# PX4FMUv2_3.net
KiCad netlist of a schematic drawn in EAGLE
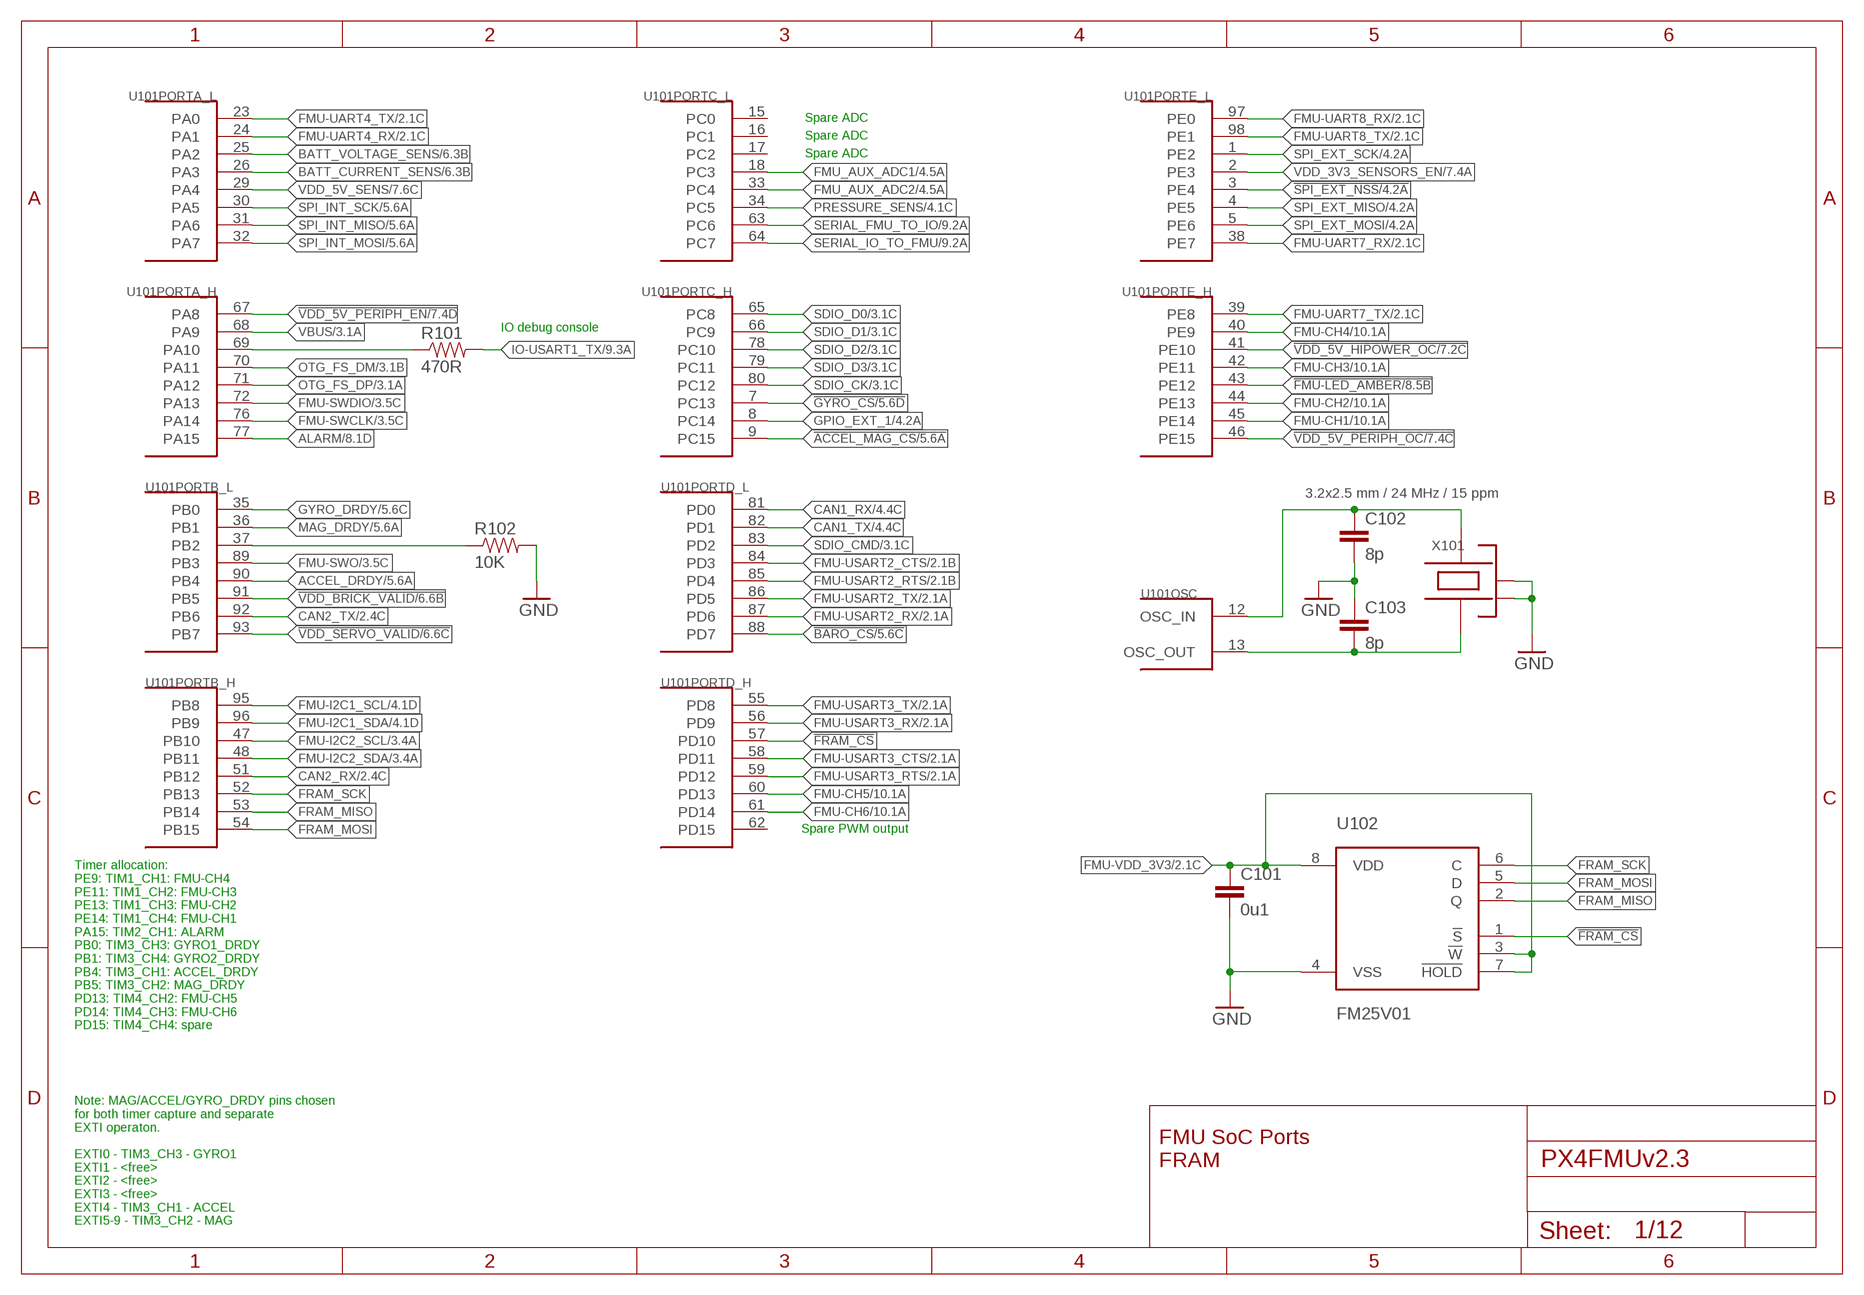
[diagram p0: schematic, sheet 1]
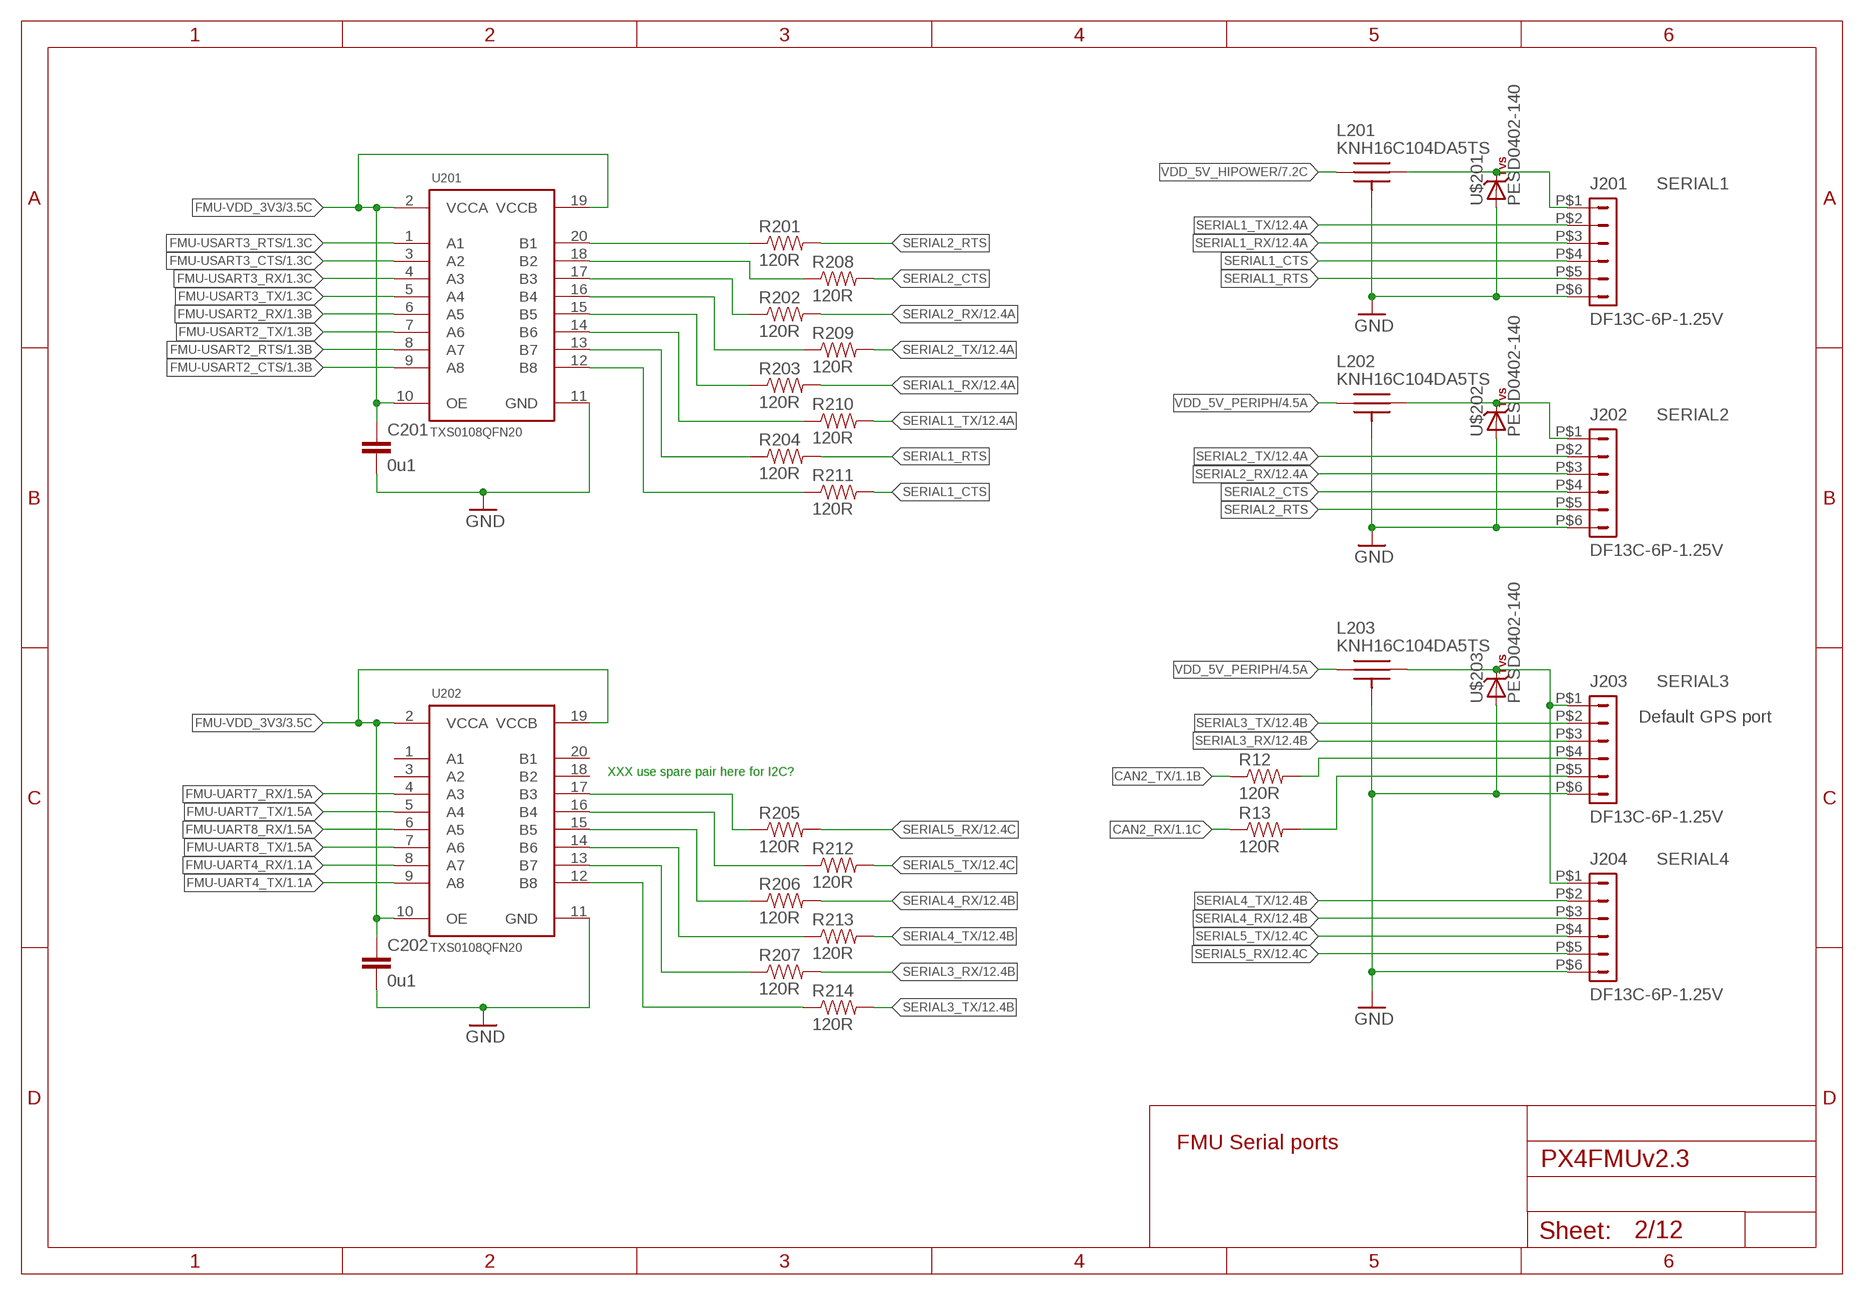
[diagram p1: schematic, sheet 2]
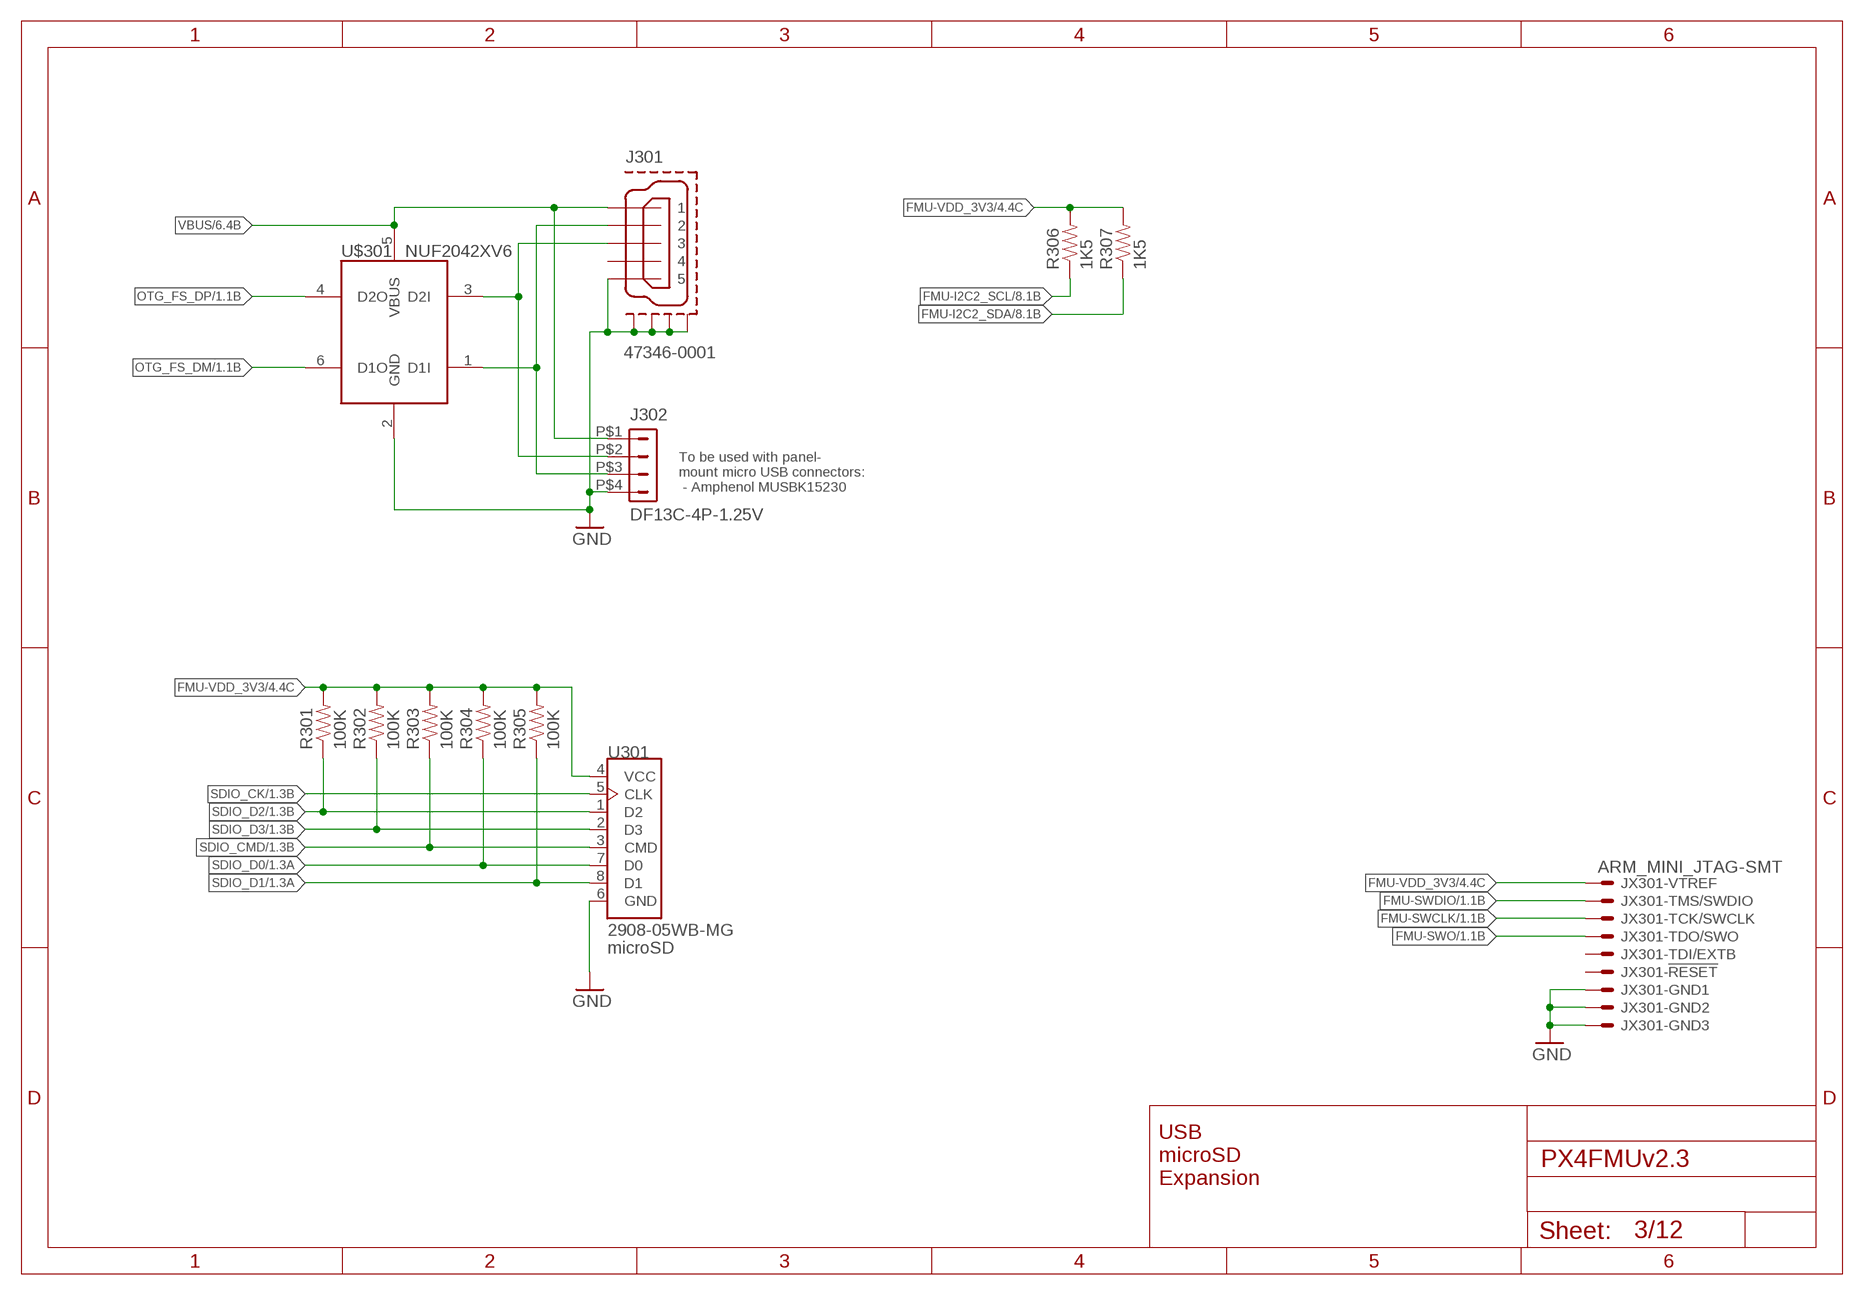
[diagram p2: schematic, sheet 3]
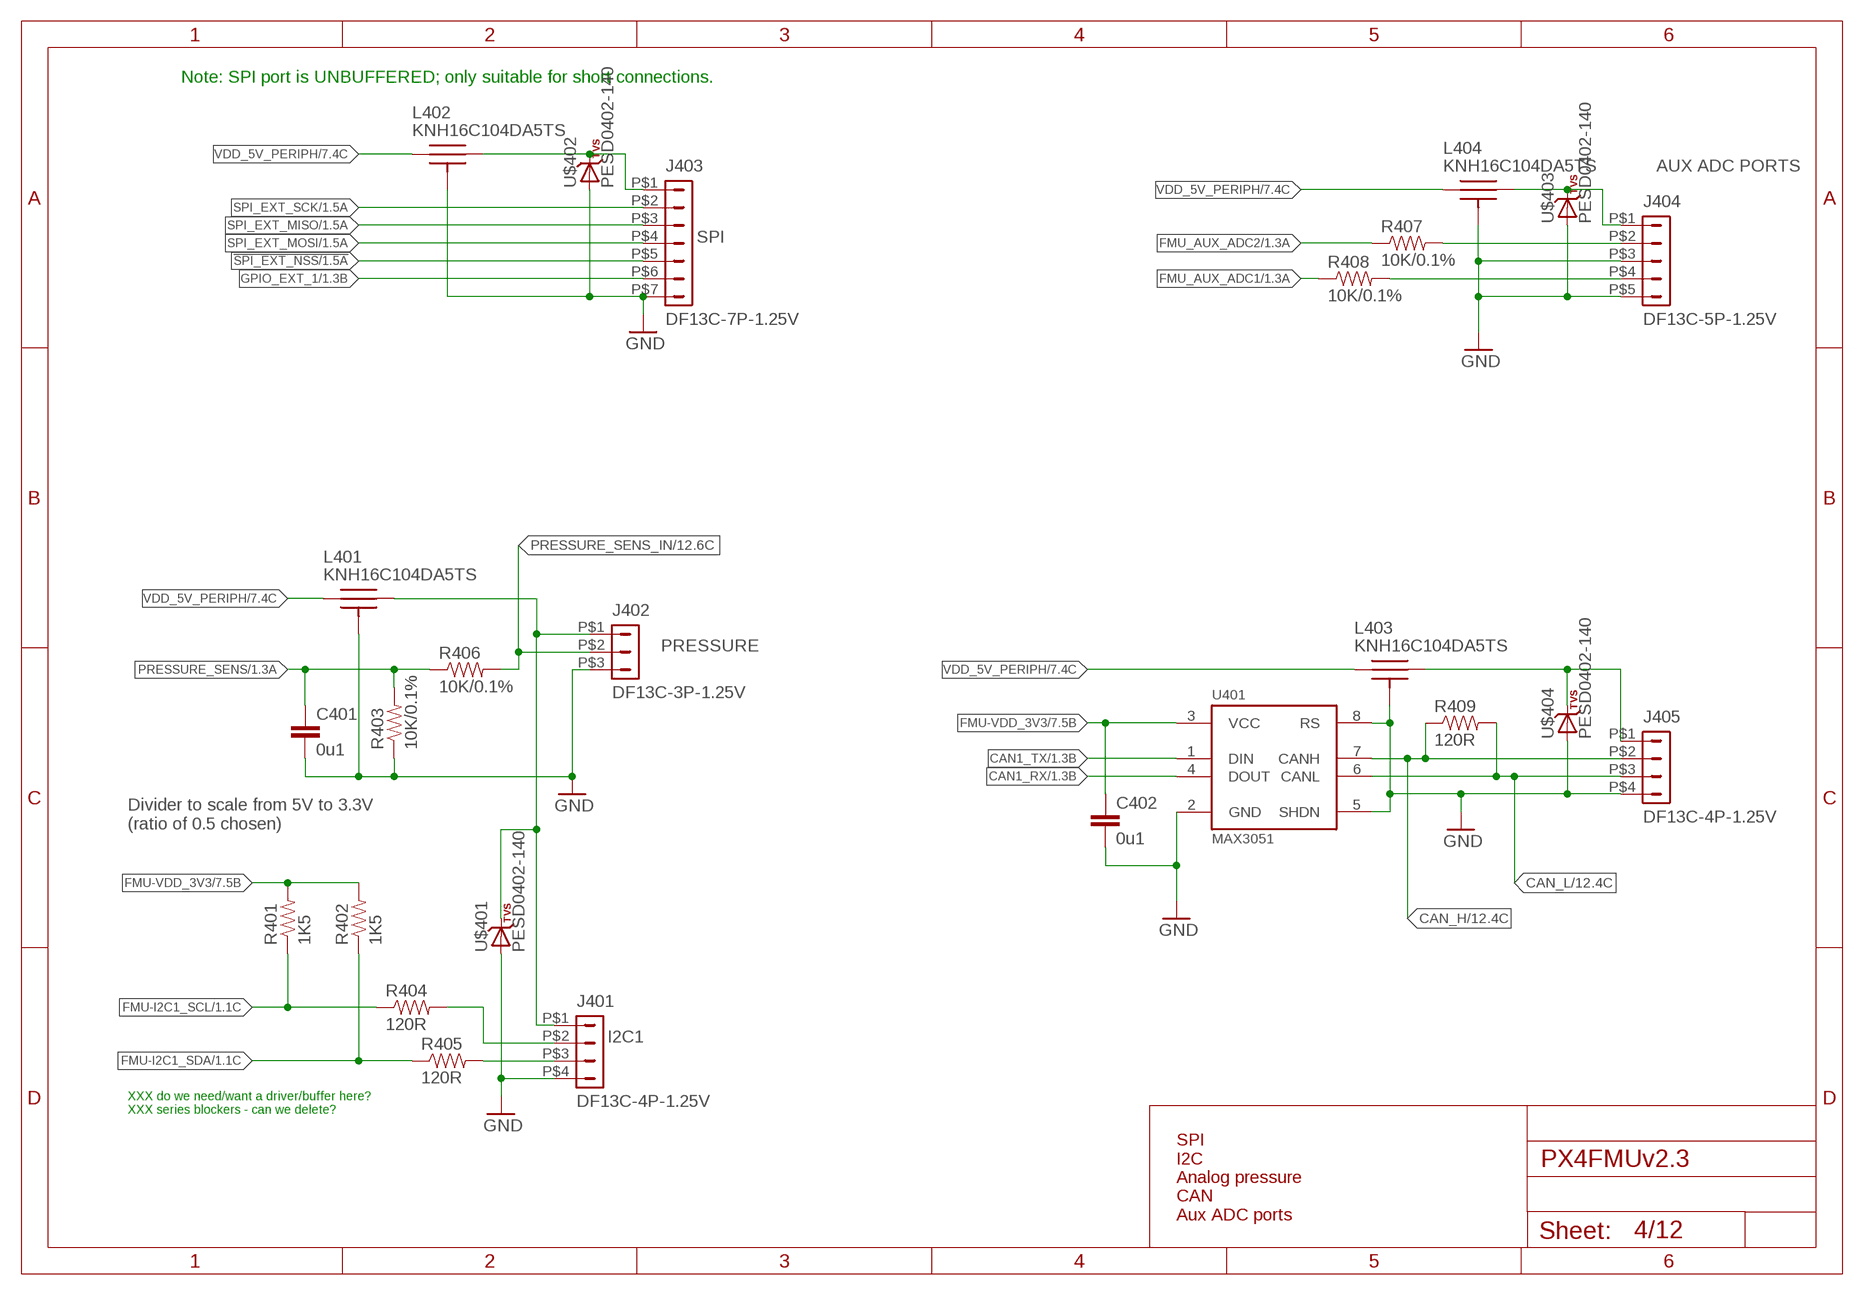
[diagram p3: schematic, sheet 4]
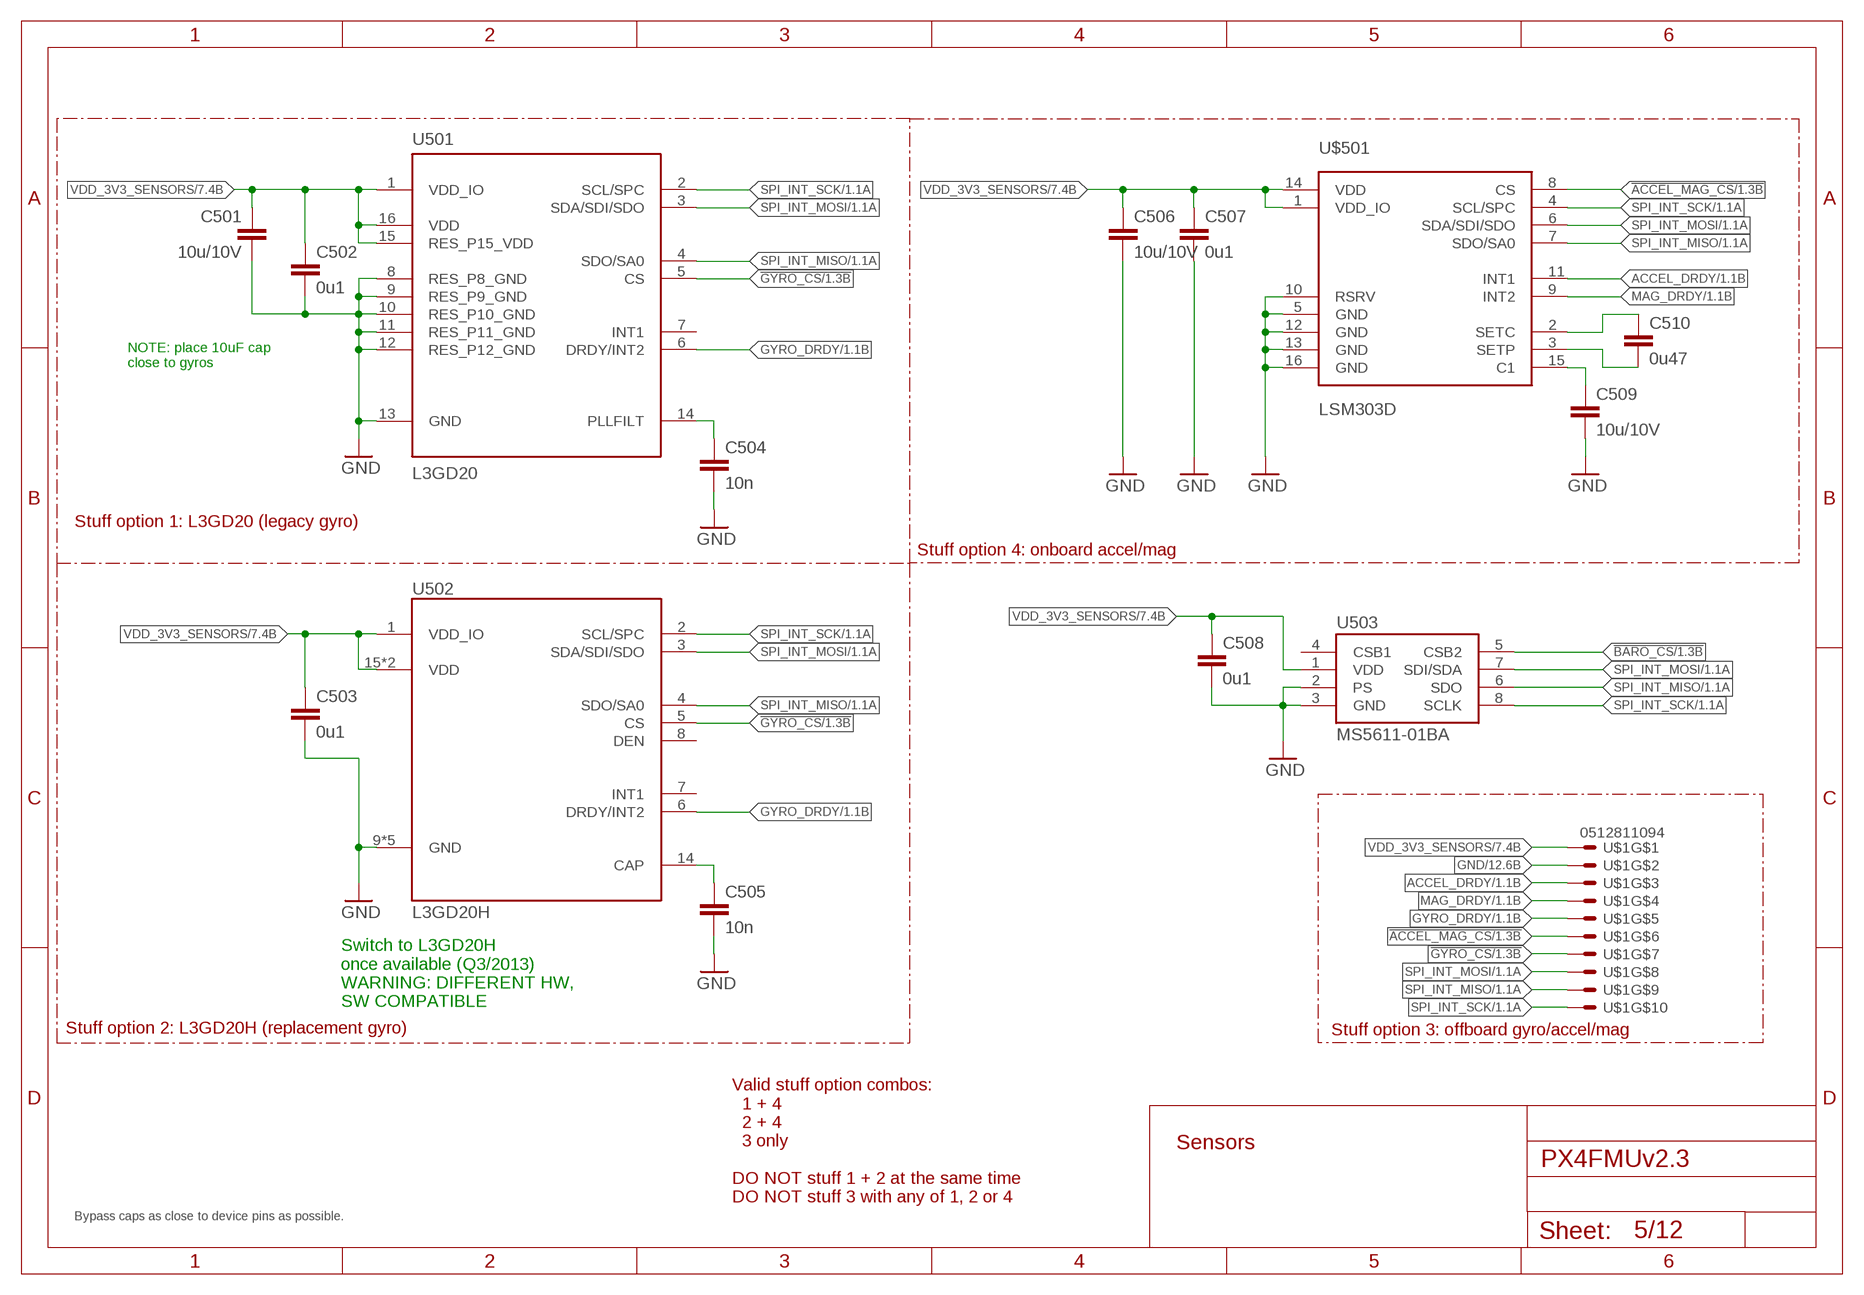
[diagram p4: schematic, sheet 5]
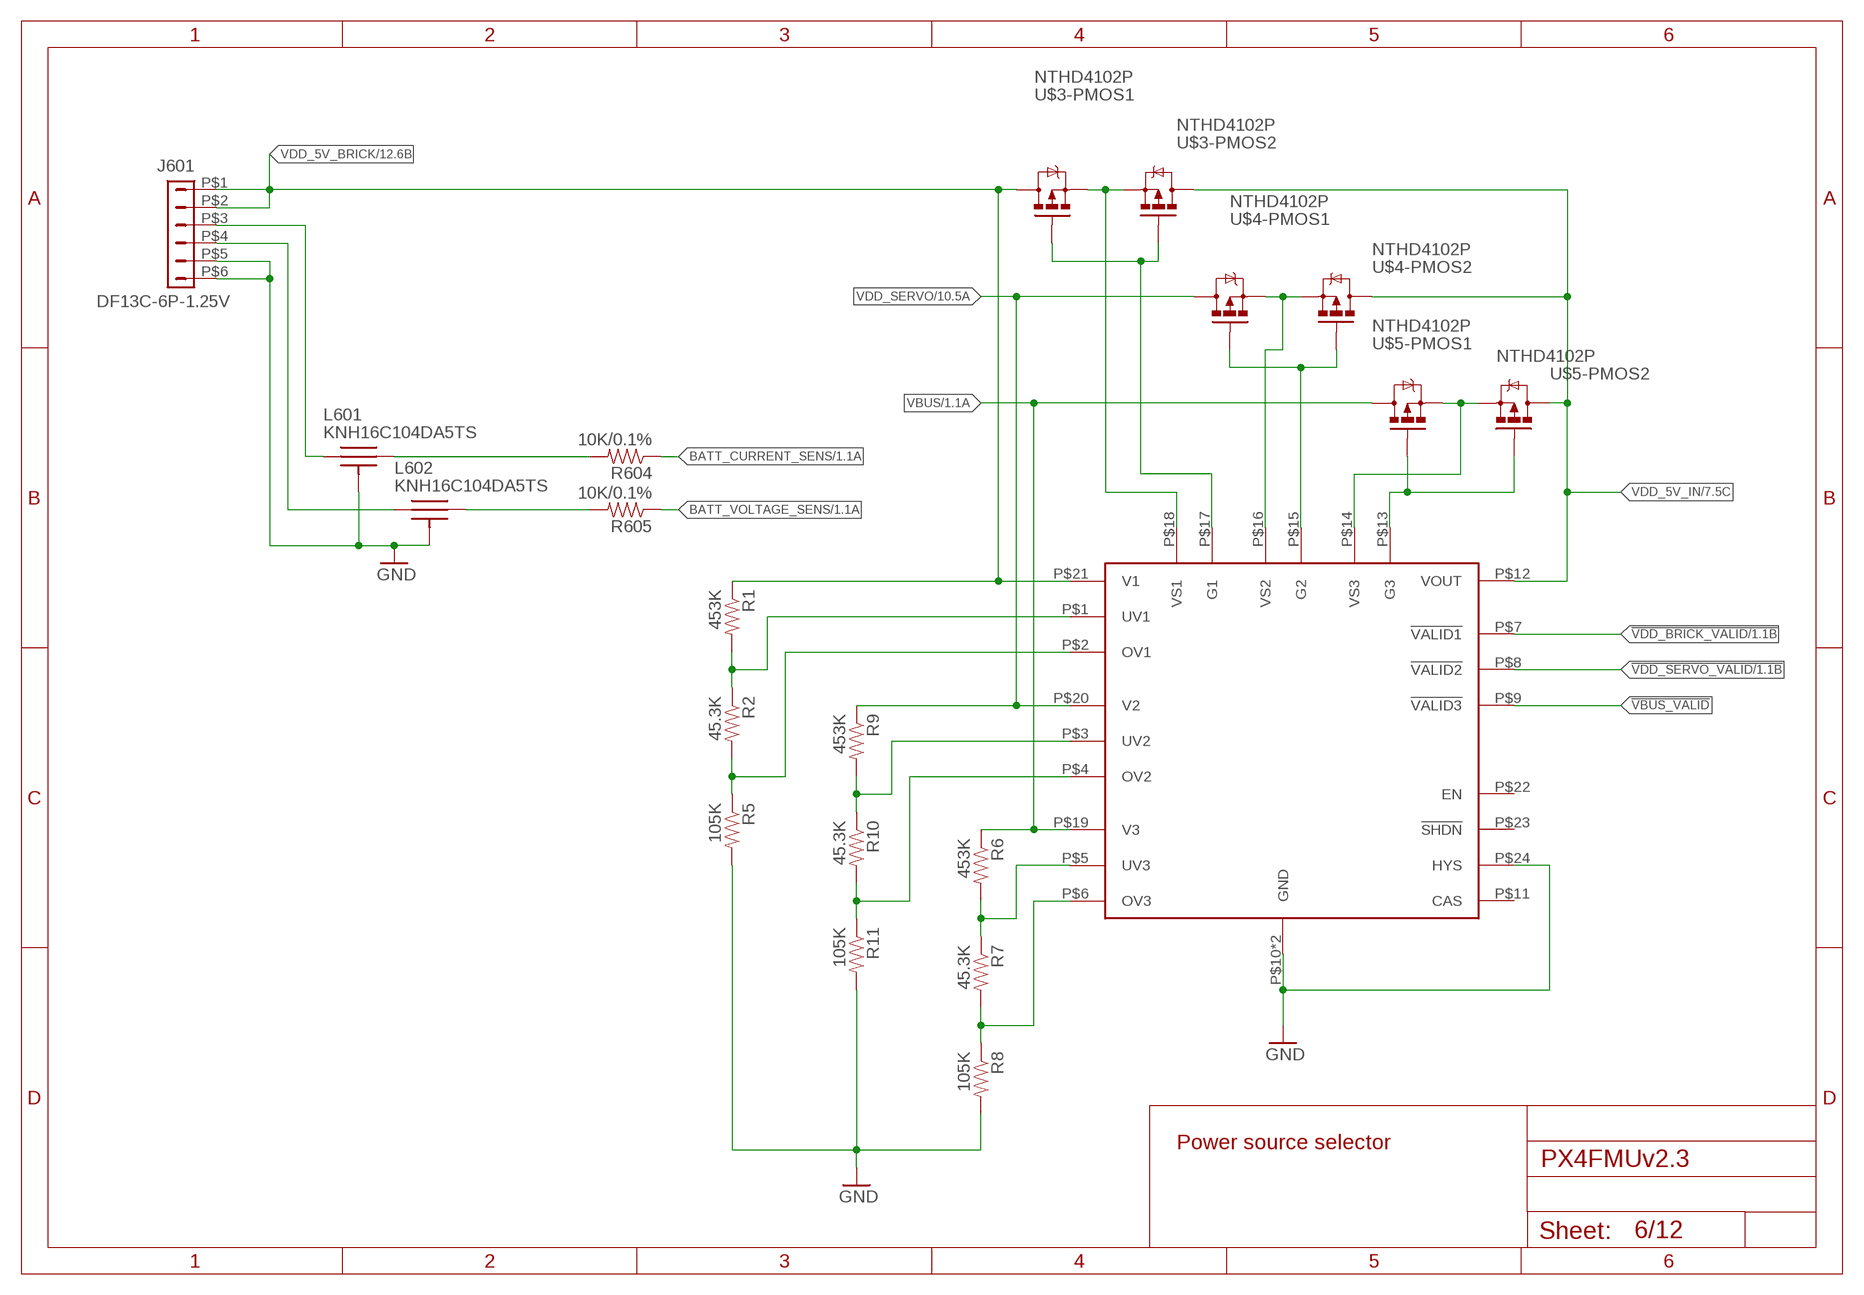
[diagram p5: schematic, sheet 6]
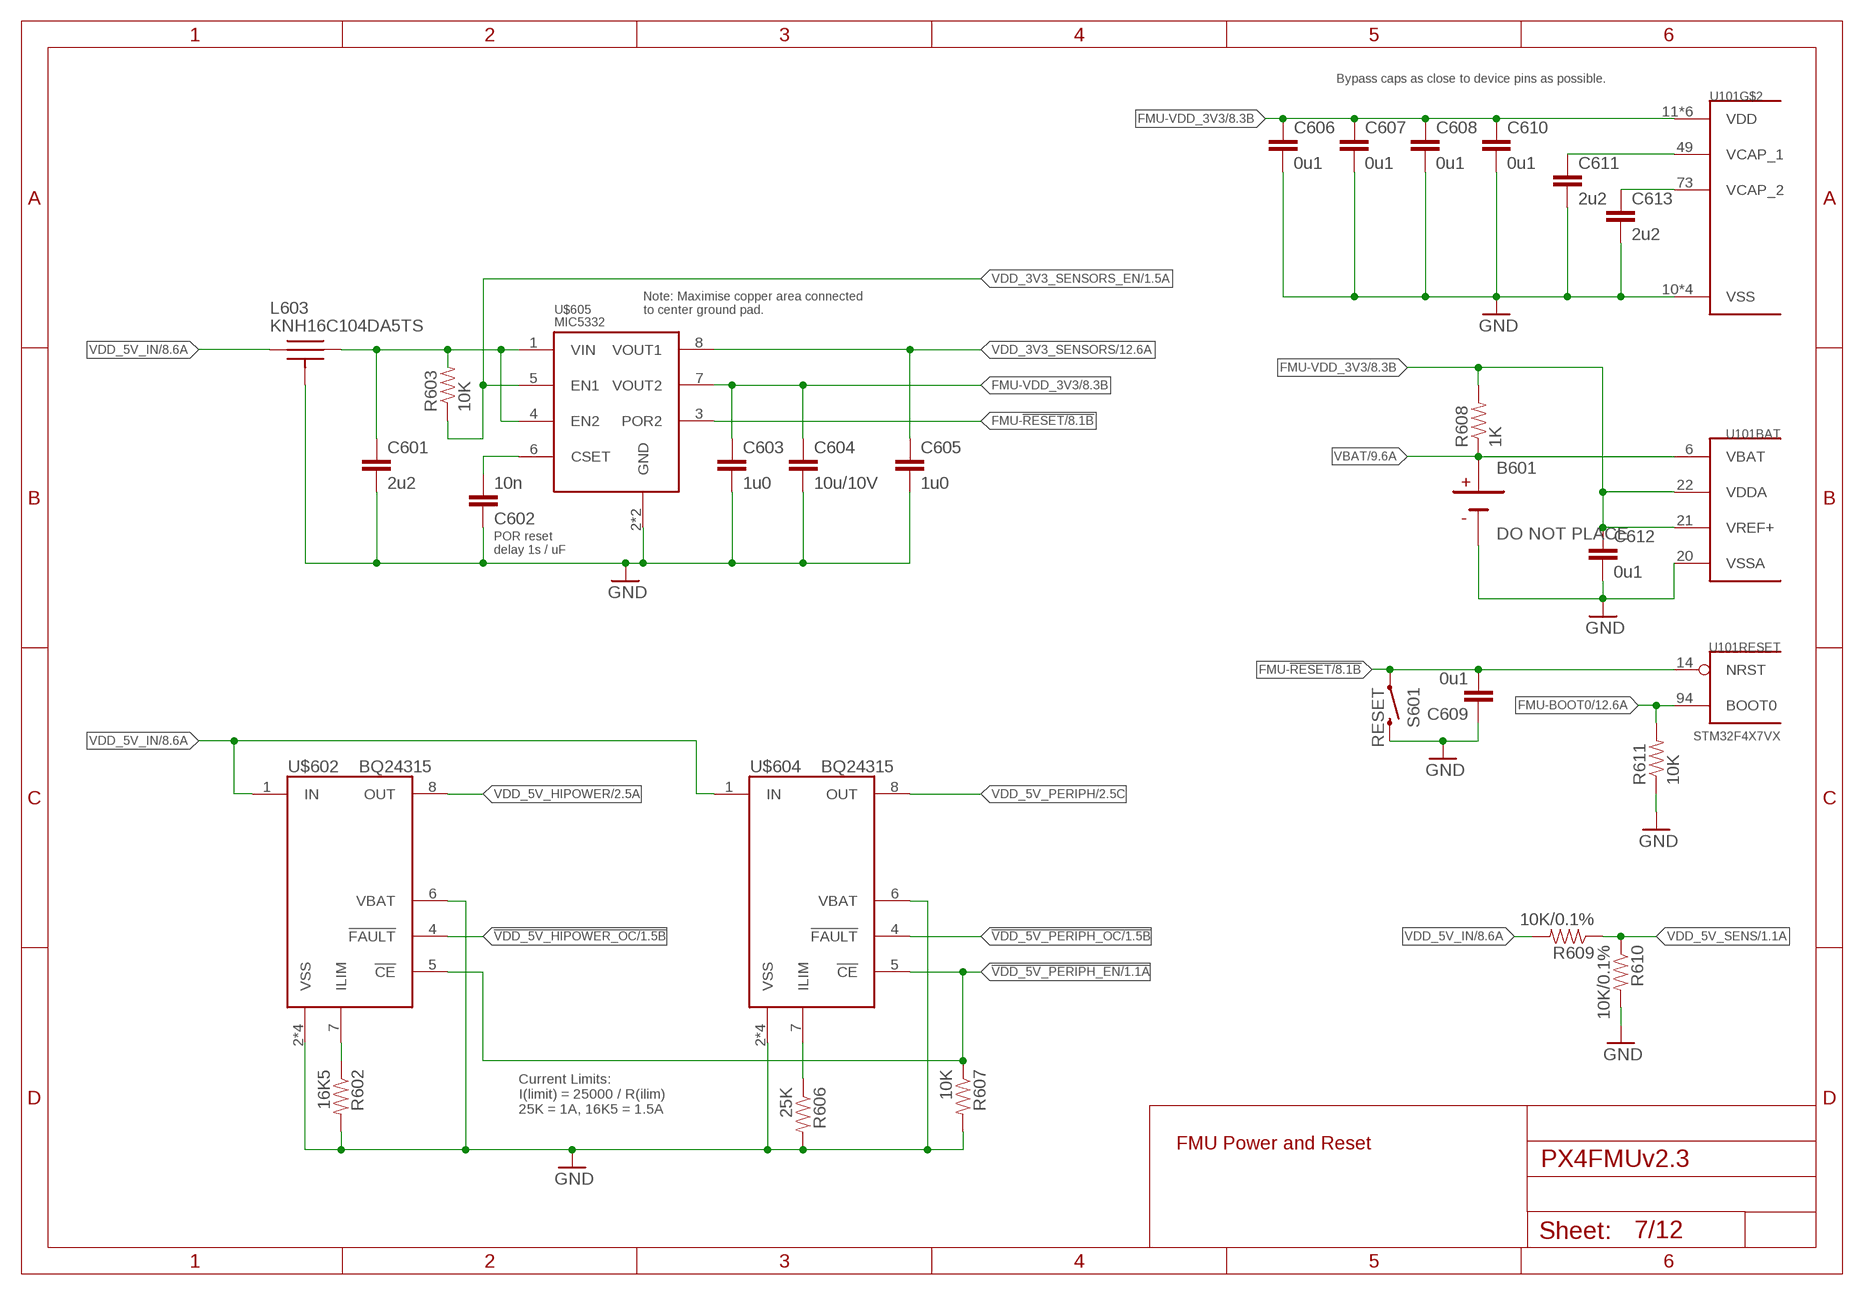
[diagram p6: schematic, sheet 7]
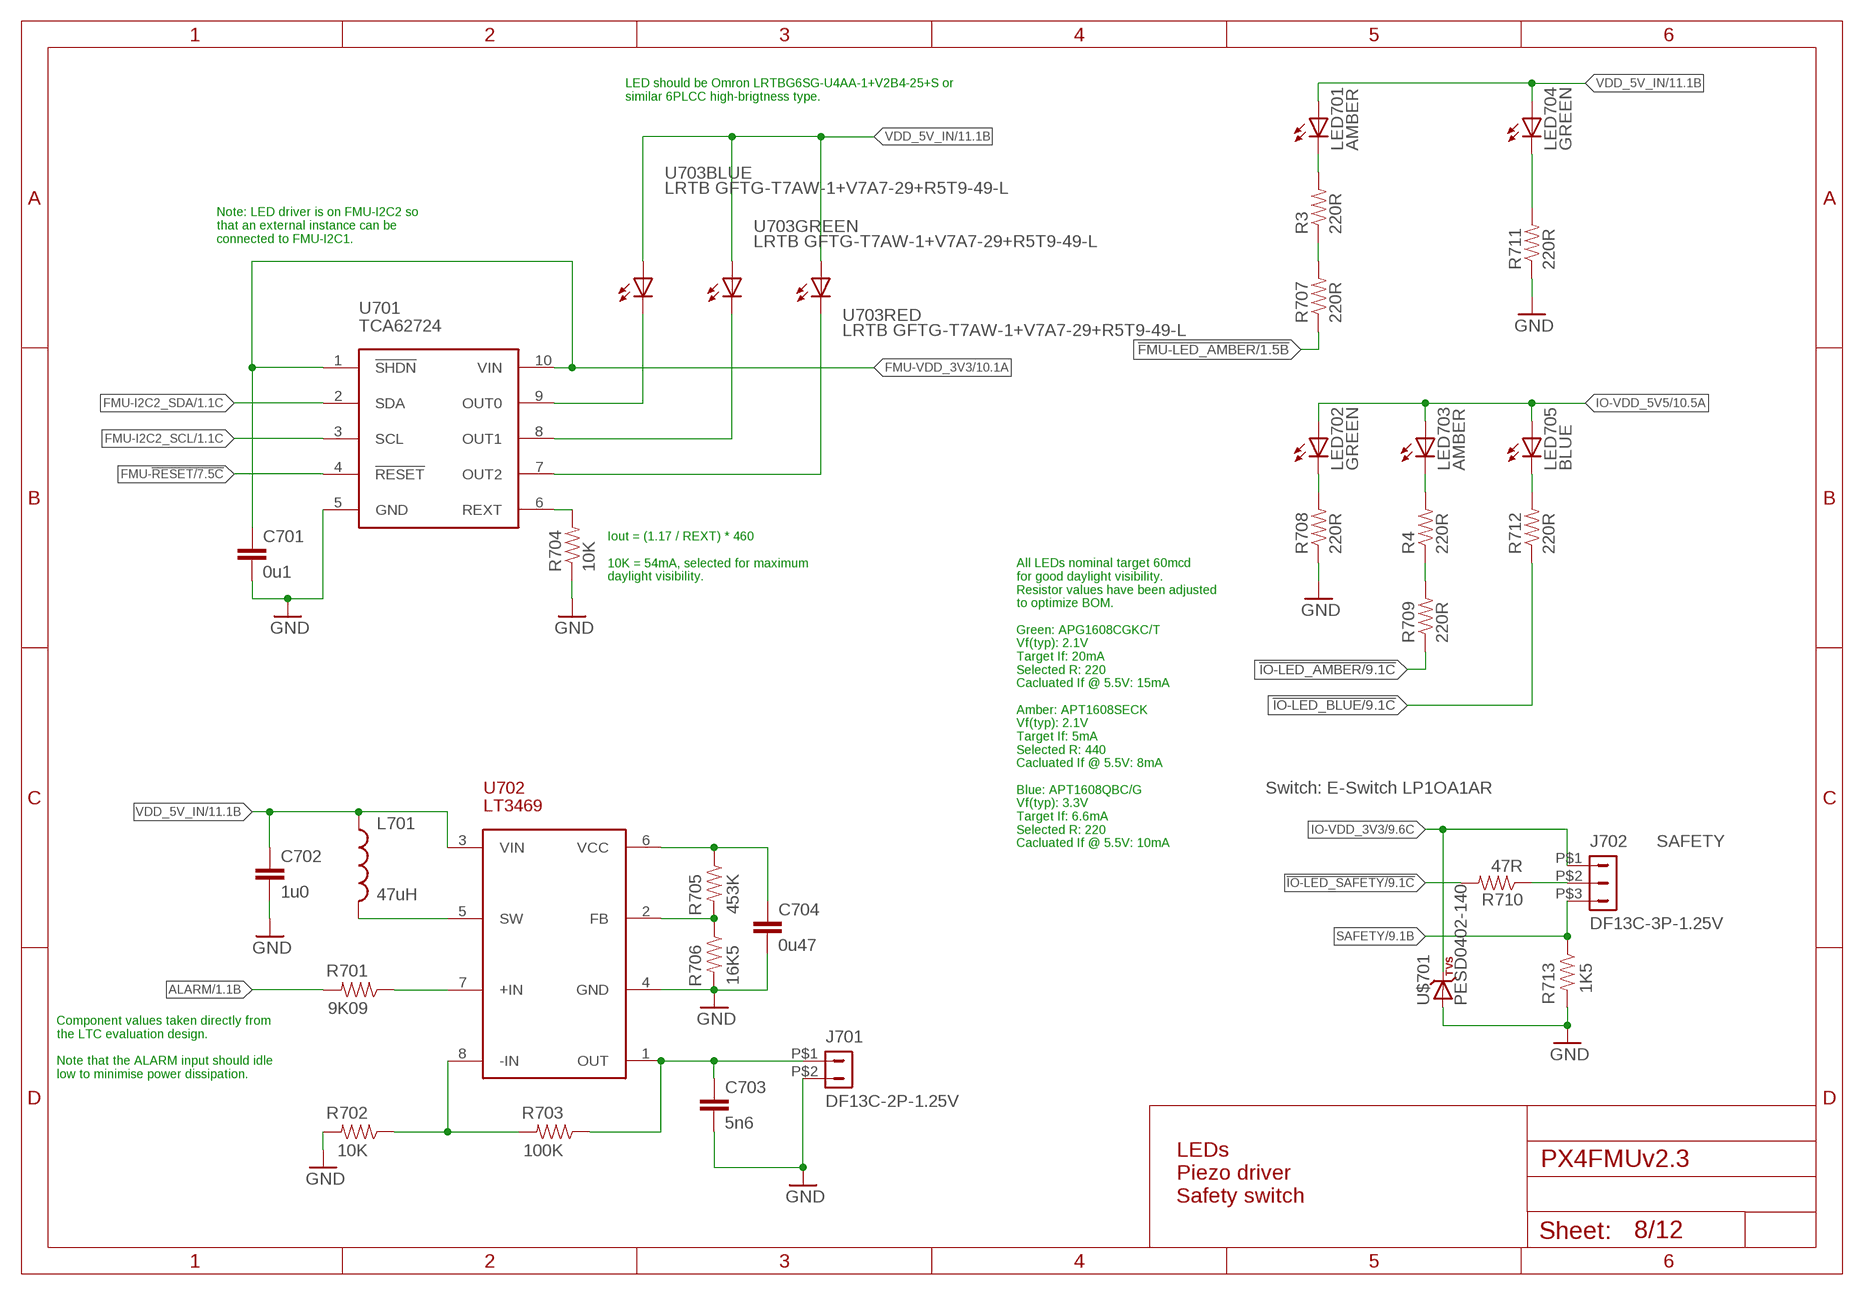
[diagram p7: schematic, sheet 8]
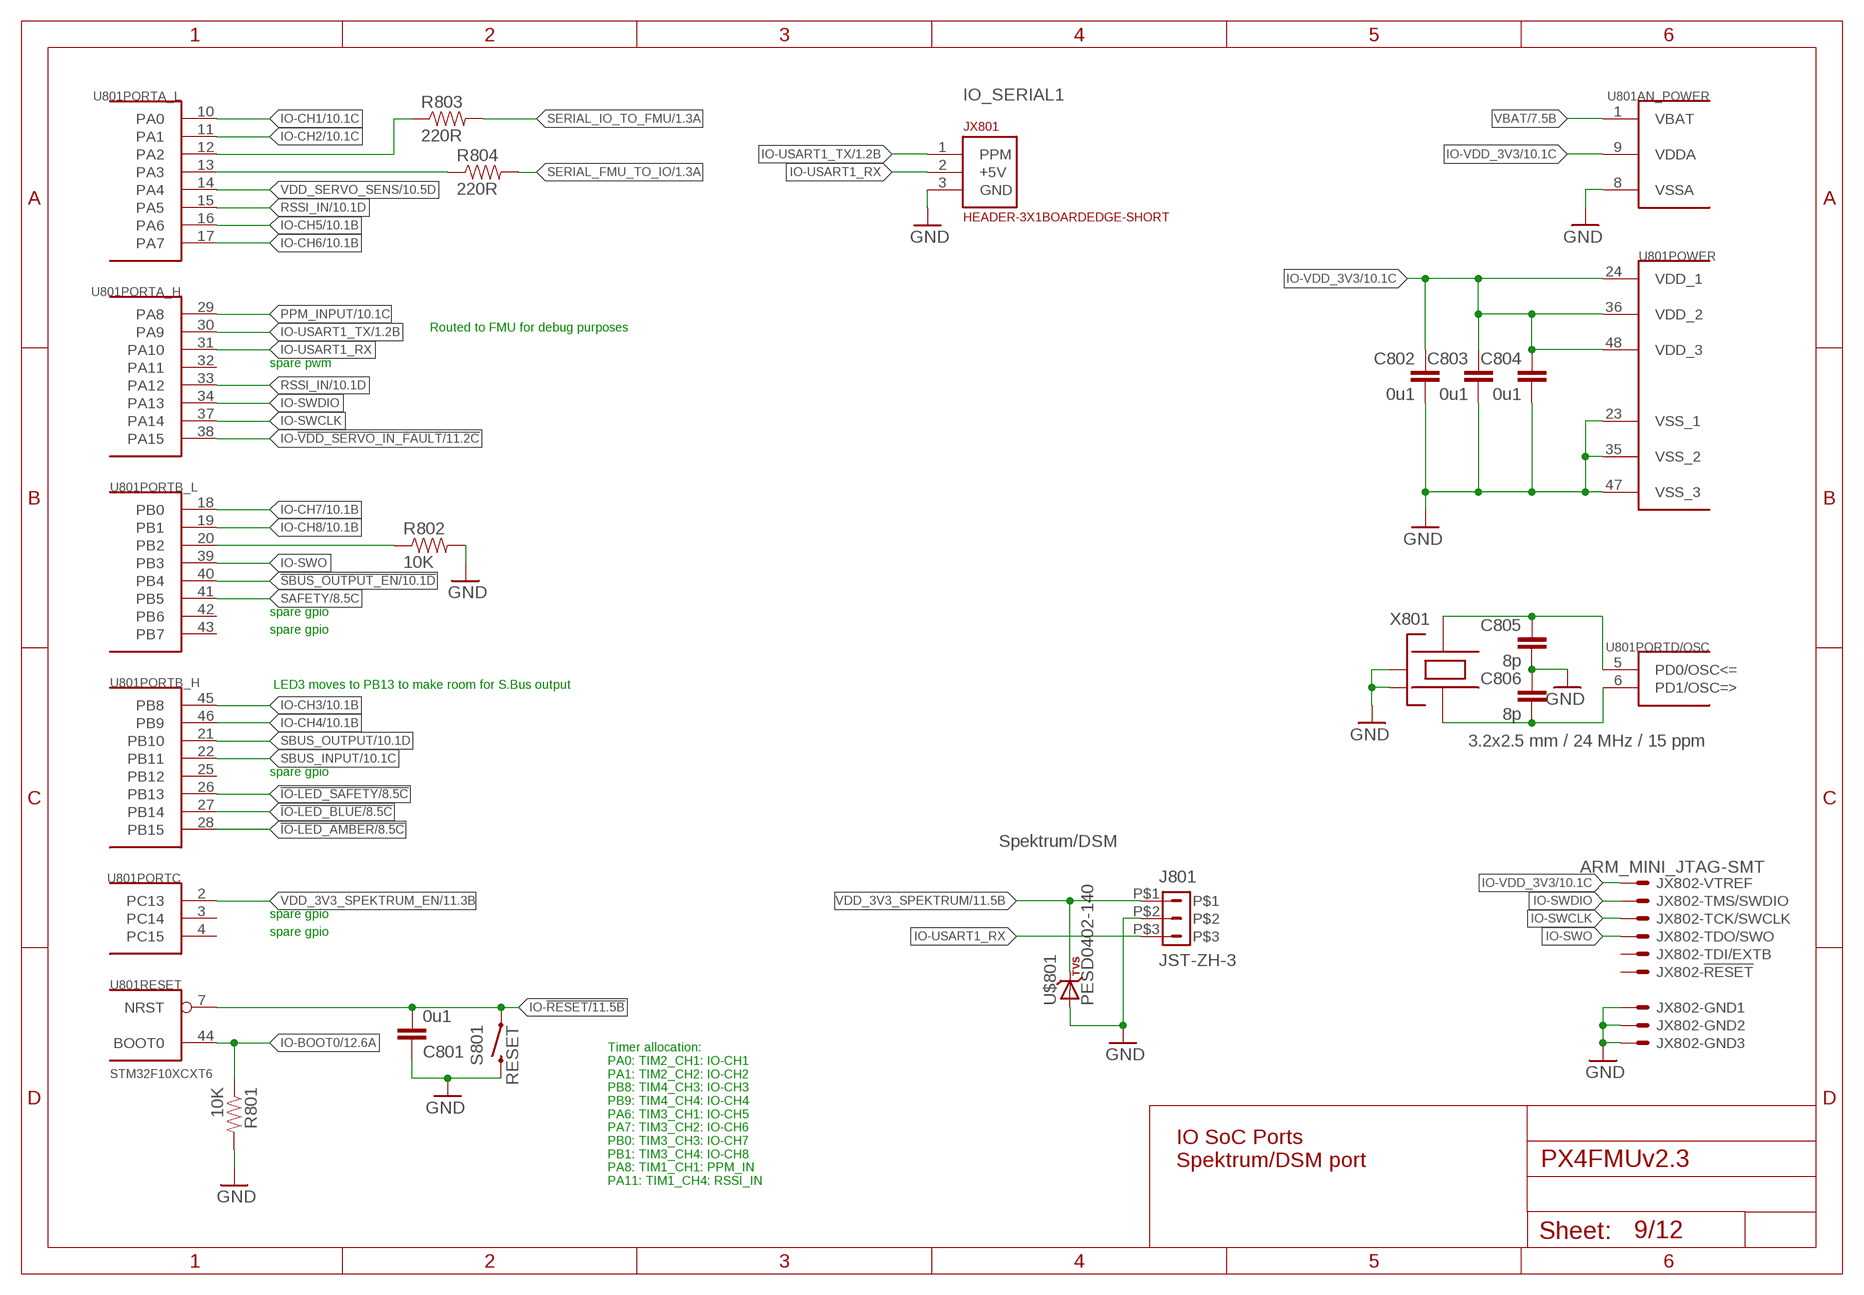
[diagram p8: schematic, sheet 9]
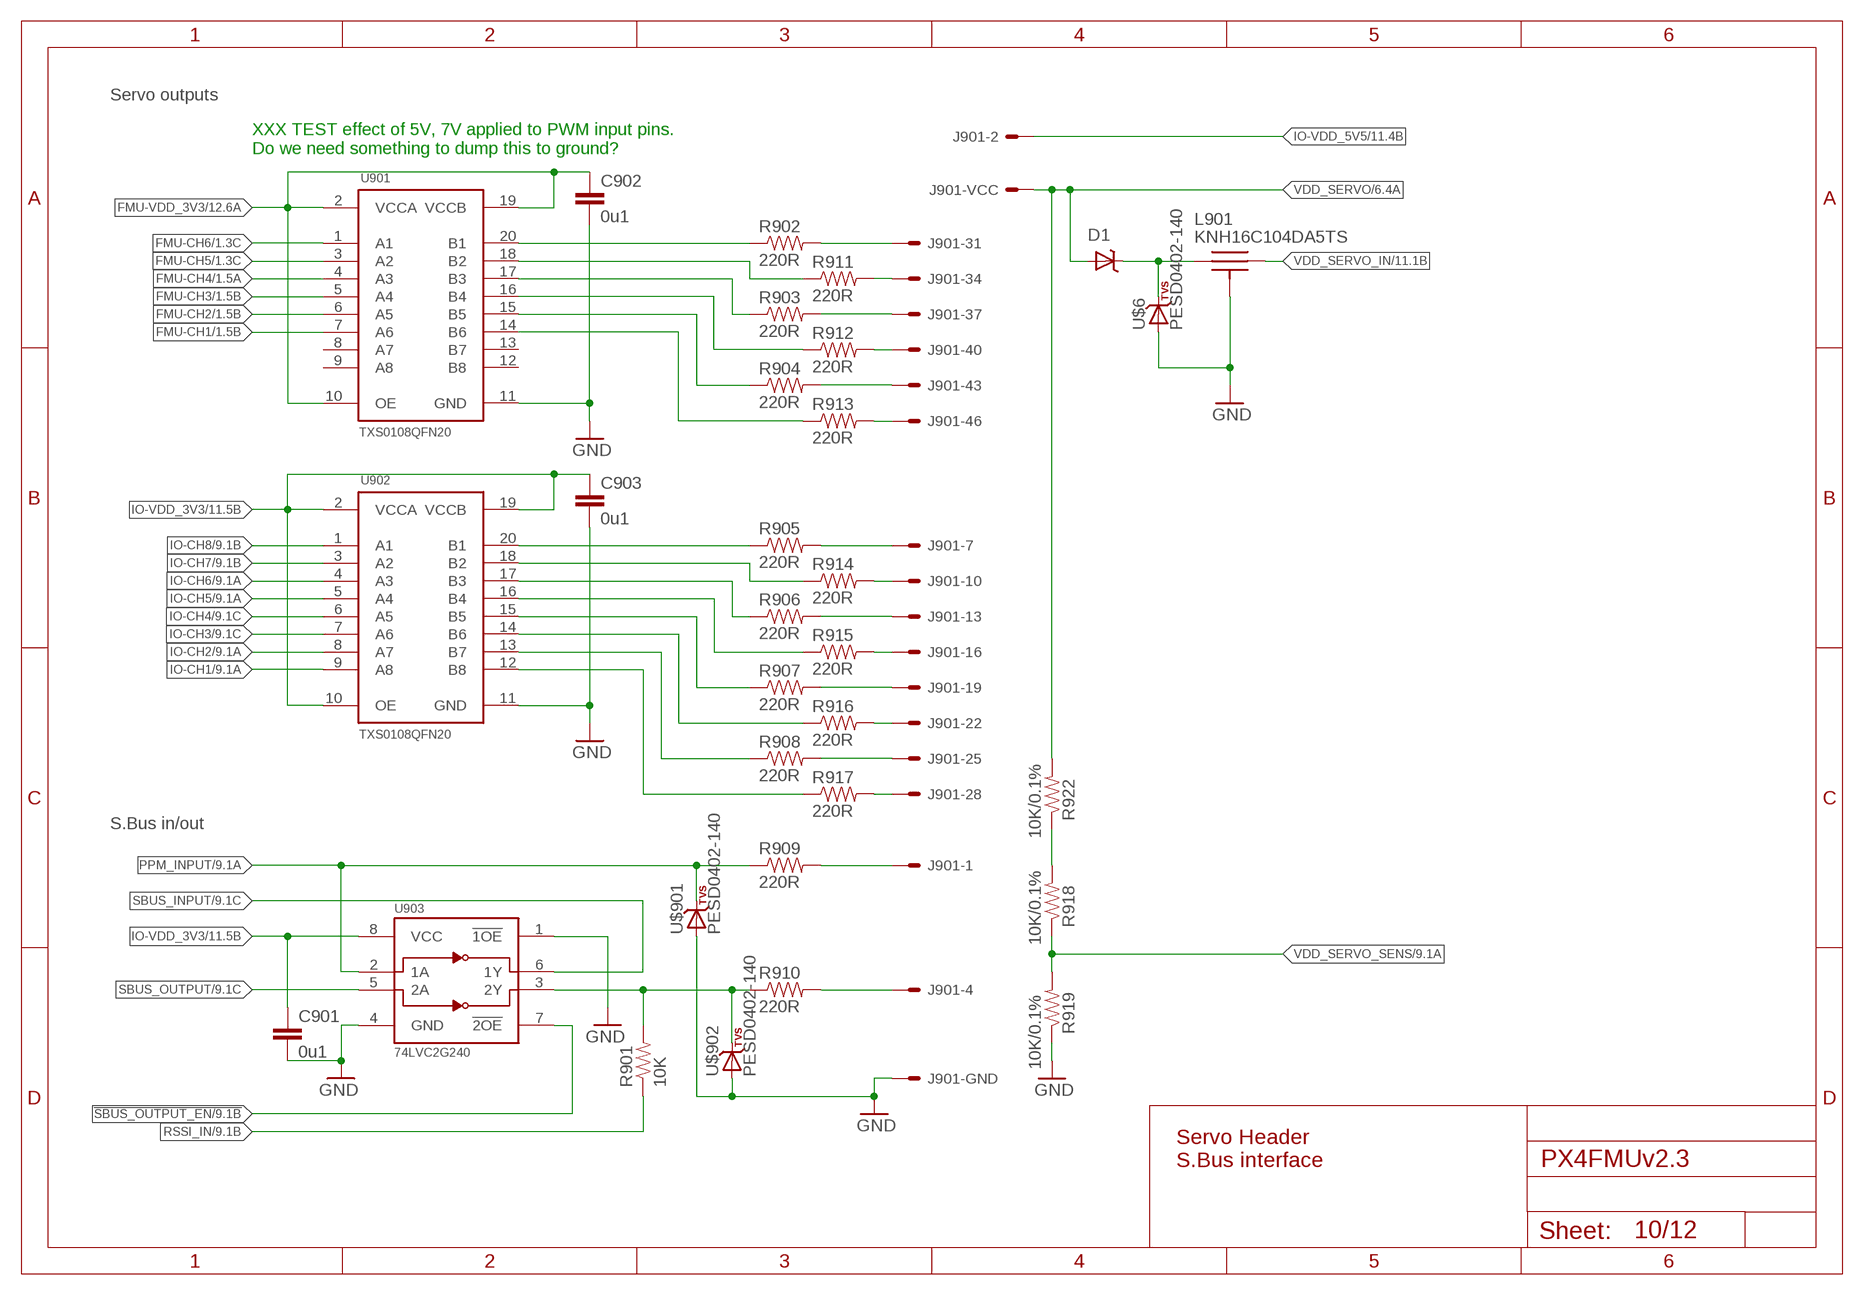
[diagram p9: schematic, sheet 10]
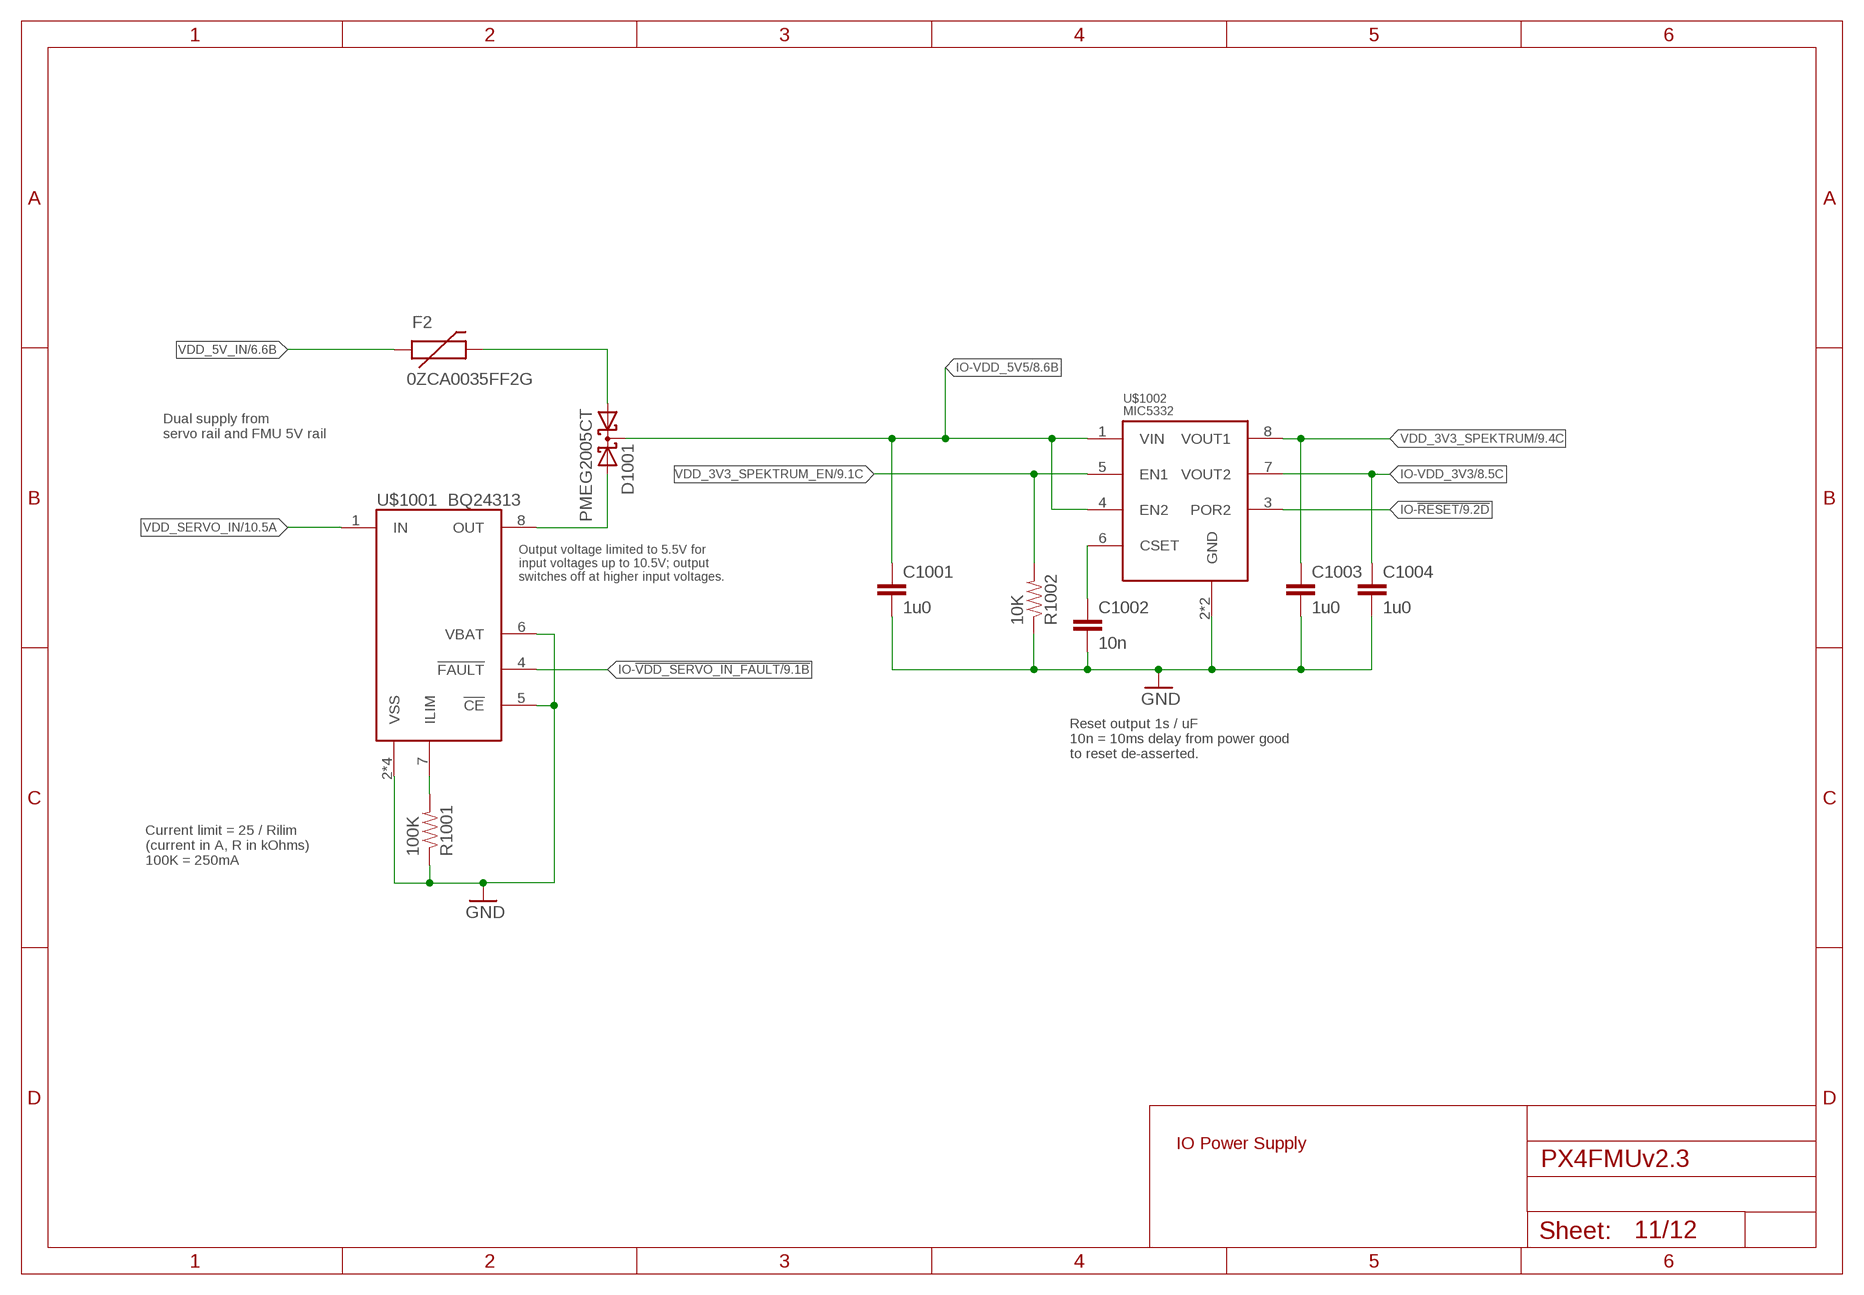
[diagram p10: schematic, sheet 11]
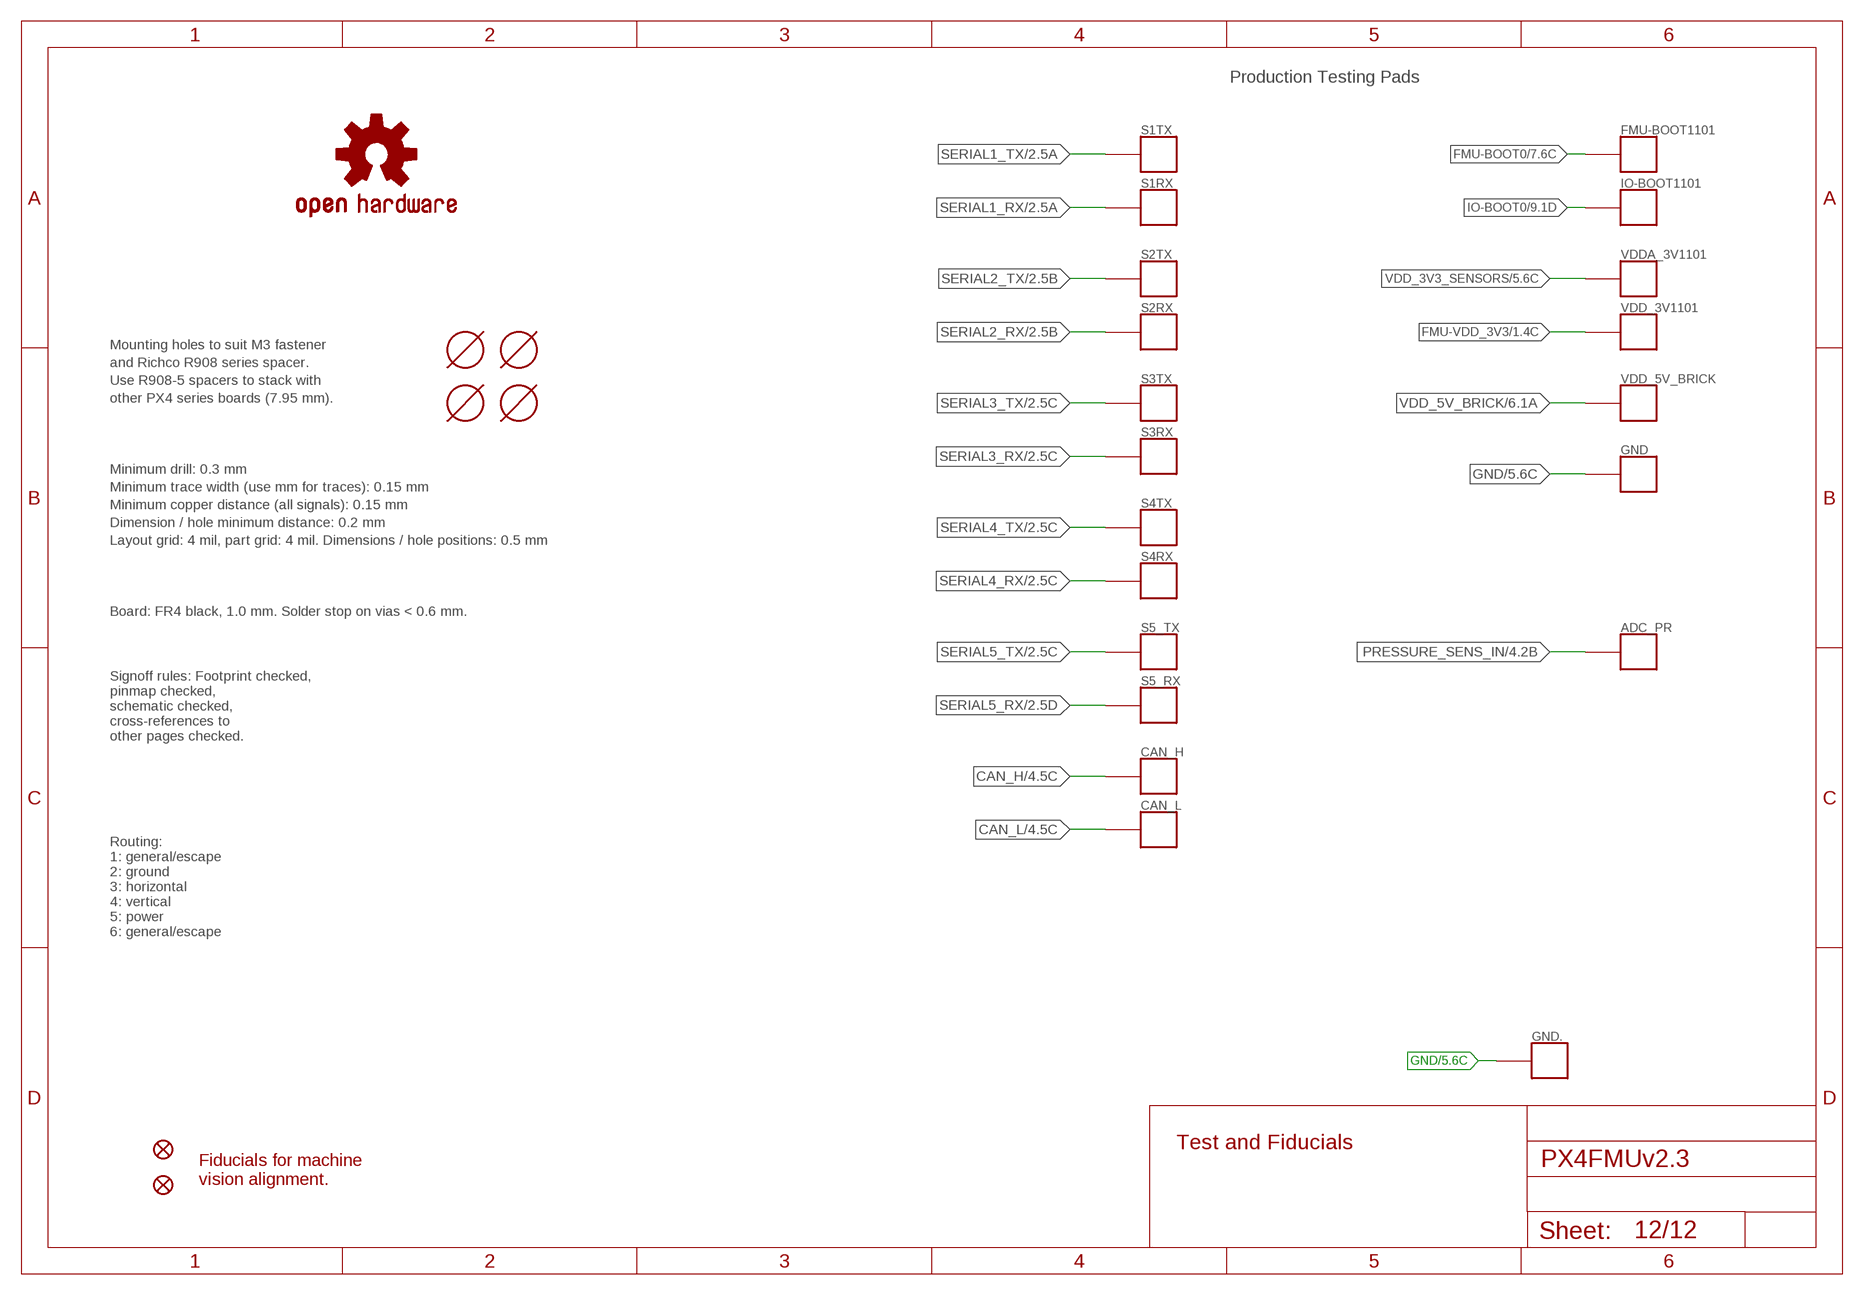
[diagram p11: schematic, sheet 12]

(export (version "E")
  (design (tool "Eeschema 10.0.6"))
  (components
    (comp (ref "C1001")
      (value "1u0")
      (footprint "eagle-import:0603-CAP")
      (fields (field (name "PARTNO") "CC0603ZRY5V7BB105"))
      (libsource (lib "eagle-import") (part "CAP0603"))
    )
    (comp (ref "C1002")
      (value "10n")
      (footprint "eagle-import:0402-CAP")
      (fields (field (name "PARTNO") "CC0402KRX7R7BB103"))
      (libsource (lib "eagle-import") (part "CAP0402"))
    )
    (comp (ref "C1003")
      (value "1u0")
      (footprint "eagle-import:0603-CAP")
      (fields (field (name "PARTNO") "CC0603ZRY5V7BB105"))
      (libsource (lib "eagle-import") (part "CAP0603"))
    )
    (comp (ref "C1004")
      (value "1u0")
      (footprint "eagle-import:0603-CAP")
      (fields (field (name "PARTNO") "CC0603ZRY5V7BB105"))
      (libsource (lib "eagle-import") (part "CAP0603"))
    )
    (comp (ref "D1001")
      (value "PMEG2005CT")
      (footprint "eagle-import:SOT23-3")
      (libsource (lib "eagle-import") (part "PMEG2005CT"))
    )
    (comp (ref "F2")
      (value "0ZCA0035FF2G")
      (footprint "eagle-import:PTC-1206")
      (libsource (lib "eagle-import") (part "PTCSMD"))
    )
    (comp (ref "R1001")
      (value "100K")
      (footprint "eagle-import:0402-RES")
      (fields (field (name "PARTNO") "RC0402FR-07100KL"))
      (libsource (lib "eagle-import") (part "RESISTOR0402-RES"))
    )
    (comp (ref "R1002")
      (value "10K")
      (footprint "eagle-import:0402-RES")
      (fields (field (name "PARTNO") "RC0402FR-0710KL"))
      (libsource (lib "eagle-import") (part "RESISTOR0402-RES"))
    )
    (comp (ref "U$1001")
      (value "BQ24313")
      (footprint "eagle-import:QFN8-DSG")
      (fields (field (name "PARTNO") "BQ24313DSGT"))
      (libsource (lib "eagle-import") (part "BQ24313"))
    )
    (comp (ref "U$1002")
      (value "MIC5332")
      (footprint "eagle-import:MLF-8-EPAD")
      (fields (field (name "PARTNO") "MIC5332-SSYMT"))
      (libsource (lib "eagle-import") (part "MIC5332"))
    )
    (comp (ref "C401")
      (value "0u1")
      (footprint "eagle-import:0402-CAP")
      (fields (field (name "PARTNO") "CC0402ZRY5V7BB104"))
      (libsource (lib "eagle-import") (part "CAP0402"))
    )
    (comp (ref "C402")
      (value "0u1")
      (footprint "eagle-import:0402-CAP")
      (fields (field (name "PARTNO") "CC0402ZRY5V7BB104"))
      (libsource (lib "eagle-import") (part "CAP0402"))
    )
    (comp (ref "J401")
      (value "DF13C-4P-1.25V")
      (footprint "eagle-import:DF13C-4P-1.25V")
      (fields (field (name "PARTNO") "DF13C-4P-1.25V(20)"))
      (libsource (lib "eagle-import") (part "DF13-4P-1.25V"))
    )
    (comp (ref "J402")
      (value "DF13C-3P-1.25V")
      (footprint "eagle-import:DF13C-3P-1.25V")
      (fields (field (name "PARTNO") "DF13C-3P-1.25V(20)"))
      (libsource (lib "eagle-import") (part "DF13-3P-1.25V"))
    )
    (comp (ref "J403")
      (value "DF13C-7P-1.25V")
      (footprint "eagle-import:DF13C-7P-1.25V")
      (fields (field (name "PARTNO") "DF13C-7P-1.25V(20)"))
      (libsource (lib "eagle-import") (part "DF13-7P-1.25V"))
    )
    (comp (ref "J404")
      (value "DF13C-5P-1.25V")
      (footprint "eagle-import:DF13C-5P-1.25V")
      (fields (field (name "PARTNO") "DF13C-5P-1.25V(20)"))
      (libsource (lib "eagle-import") (part "DF13-5P-1.25V"))
    )
    (comp (ref "J405")
      (value "DF13C-4P-1.25V")
      (footprint "eagle-import:DF13C-4P-1.25V")
      (fields (field (name "PARTNO") "DF13C-4P-1.25V(20)"))
      (libsource (lib "eagle-import") (part "DF13-4P-1.25V"))
    )
    (comp (ref "L401")
      (value "KNH16C104DA5TS")
      (footprint "eagle-import:KYOCERA-KNH16-DA")
      (libsource (lib "eagle-import") (part "KNH16C104DA5TS"))
    )
    (comp (ref "L402")
      (value "KNH16C104DA5TS")
      (footprint "eagle-import:KYOCERA-KNH16-DA")
      (libsource (lib "eagle-import") (part "KNH16C104DA5TS"))
    )
    (comp (ref "L403")
      (value "KNH16C104DA5TS")
      (footprint "eagle-import:KYOCERA-KNH16-DA")
      (libsource (lib "eagle-import") (part "KNH16C104DA5TS"))
    )
    (comp (ref "L404")
      (value "KNH16C104DA5TS")
      (footprint "eagle-import:KYOCERA-KNH16-DA")
      (libsource (lib "eagle-import") (part "KNH16C104DA5TS"))
    )
    (comp (ref "R401")
      (value "1K5")
      (footprint "eagle-import:0402-RES")
      (fields (field (name "PARTNO") "RC0402FR-071K5L"))
      (libsource (lib "eagle-import") (part "RESISTOR0402-RES"))
    )
    (comp (ref "R402")
      (value "1K5")
      (footprint "eagle-import:0402-RES")
      (fields (field (name "PARTNO") "RC0402FR-071K5L"))
      (libsource (lib "eagle-import") (part "RESISTOR0402-RES"))
    )
    (comp (ref "R403")
      (value "10K/0.1%")
      (footprint "eagle-import:0402-RES")
      (fields (field (name "PARTNO") "ERA-2AEB103X"))
      (libsource (lib "eagle-import") (part "RESISTOR0402-RES"))
    )
    (comp (ref "R404")
      (value "120R")
      (footprint "eagle-import:0402-RES")
      (fields (field (name "PARTNO") "RC0402FR-07120RL"))
      (libsource (lib "eagle-import") (part "RESISTOR0402-RES"))
    )
    (comp (ref "R405")
      (value "120R")
      (footprint "eagle-import:0402-RES")
      (fields (field (name "PARTNO") "RC0402FR-07120RL"))
      (libsource (lib "eagle-import") (part "RESISTOR0402-RES"))
    )
    (comp (ref "R406")
      (value "10K/0.1%")
      (footprint "eagle-import:0402-RES")
      (fields (field (name "PARTNO") "ERA-2AEB103X"))
      (libsource (lib "eagle-import") (part "RESISTOR0402-RES"))
    )
    (comp (ref "R407")
      (value "10K/0.1%")
      (footprint "eagle-import:0402-RES")
      (fields (field (name "PARTNO") "ERA-2AEB103X"))
      (libsource (lib "eagle-import") (part "RESISTOR0402-RES"))
    )
    (comp (ref "R408")
      (value "10K/0.1%")
      (footprint "eagle-import:0402-RES")
      (fields (field (name "PARTNO") "ERA-2AEB103X"))
      (libsource (lib "eagle-import") (part "RESISTOR0402-RES"))
    )
    (comp (ref "R409")
      (value "120R")
      (footprint "eagle-import:0402-RES")
      (fields (field (name "PARTNO") "RC0402FR-07120RL"))
      (libsource (lib "eagle-import") (part "RESISTOR0402-RES"))
    )
    (comp (ref "U$401")
      (value "PESD0402-140")
      (footprint "eagle-import:0402-TVS")
      (libsource (lib "eagle-import") (part "DIODE-TVS"))
    )
    (comp (ref "U$402")
      (value "PESD0402-140")
      (footprint "eagle-import:0402-TVS")
      (libsource (lib "eagle-import") (part "DIODE-TVS"))
    )
    (comp (ref "U$403")
      (value "PESD0402-140")
      (footprint "eagle-import:0402-TVS")
      (libsource (lib "eagle-import") (part "DIODE-TVS"))
    )
    (comp (ref "U$404")
      (value "PESD0402-140")
      (footprint "eagle-import:0402-TVS")
      (libsource (lib "eagle-import") (part "DIODE-TVS"))
    )
    (comp (ref "U401")
      (value "MAX3051")
      (footprint "eagle-import:SOT23-8")
      (fields (field (name "PARTNO") "MAX3051EKA"))
      (libsource (lib "eagle-import") (part "MAX3051MAX3051EKA"))
    )
    (comp (ref "C501")
      (value "10u/10V")
      (footprint "eagle-import:0805-CAP")
      (fields (field (name "PARTNO") "CC0805ZKY5V6BB106"))
      (libsource (lib "eagle-import") (part "CAP0805"))
    )
    (comp (ref "C502")
      (value "0u1")
      (footprint "eagle-import:0402-CAP")
      (fields (field (name "PARTNO") "CC0402ZRY5V7BB104"))
      (libsource (lib "eagle-import") (part "CAP0402"))
    )
    (comp (ref "C503")
      (value "0u1")
      (footprint "eagle-import:0402-CAP")
      (fields (field (name "PARTNO") "CC0402ZRY5V7BB104"))
      (libsource (lib "eagle-import") (part "CAP0402"))
    )
    (comp (ref "C504")
      (value "10n")
      (footprint "eagle-import:0402-CAP")
      (fields (field (name "PARTNO") "CC0402KRX7R7BB103"))
      (libsource (lib "eagle-import") (part "CAP0402"))
    )
    (comp (ref "C505")
      (value "10n")
      (footprint "eagle-import:0402-CAP")
      (fields (field (name "PARTNO") "CC0402KRX7R7BB103"))
      (libsource (lib "eagle-import") (part "CAP0402"))
    )
    (comp (ref "C506")
      (value "10u/10V")
      (footprint "eagle-import:0805-CAP")
      (fields (field (name "PARTNO") "CC0805ZKY5V6BB106"))
      (libsource (lib "eagle-import") (part "CAP0805"))
    )
    (comp (ref "C507")
      (value "0u1")
      (footprint "eagle-import:0402-CAP")
      (fields (field (name "PARTNO") "CC0402ZRY5V7BB104"))
      (libsource (lib "eagle-import") (part "CAP0402"))
    )
    (comp (ref "C508")
      (value "0u1")
      (footprint "eagle-import:0402-CAP")
      (fields (field (name "PARTNO") "CC0402ZRY5V7BB104"))
      (libsource (lib "eagle-import") (part "CAP0402"))
    )
    (comp (ref "C509")
      (value "10u/10V")
      (footprint "eagle-import:0805-CAP")
      (fields (field (name "PARTNO") "CC0805ZKY5V6BB106"))
      (libsource (lib "eagle-import") (part "CAP0805"))
    )
    (comp (ref "C510")
      (value "0u47")
      (footprint "eagle-import:0402-CAP")
      (fields (field (name "PARTNO") "C1005X5R1C474K050BC"))
      (libsource (lib "eagle-import") (part "CAP0402"))
    )
    (comp (ref "U$1")
      (value "0512811094")
      (footprint "eagle-import:51281-1094")
      (fields (field (name "PARTNO") "0781191109"))
      (libsource (lib "eagle-import") (part "CONN_FPC_10RA"))
    )
    (comp (ref "U$501")
      (value "LSM303D")
      (footprint "eagle-import:LGA-16L")
      (libsource (lib "eagle-import") (part "LSM303D"))
    )
    (comp (ref "U501")
      (value "L3GD20")
      (footprint "eagle-import:L3G4200DH-MAN")
      (libsource (lib "eagle-import") (part "L3G4200DH-LL"))
    )
    (comp (ref "U502")
      (value "L3GD20H")
      (footprint "eagle-import:LGA-16L")
      (libsource (lib "eagle-import") (part "L3GD20H"))
    )
    (comp (ref "U503")
      (value "MS5611-01BA")
      (footprint "eagle-import:MS5611-01BA")
      (libsource (lib "eagle-import") (part "MS5611-01BA"))
    )
    (comp (ref "ADC_PR")
      (value "PAD.04")
      (footprint "eagle-import:PAD.04X.04")
      (libsource (lib "eagle-import") (part "PAD.04"))
    )
    (comp (ref "CAN_H")
      (value "PAD.04")
      (footprint "eagle-import:PAD.04X.04")
      (libsource (lib "eagle-import") (part "PAD.04"))
    )
    (comp (ref "CAN_L")
      (value "PAD.04")
      (footprint "eagle-import:PAD.04X.04")
      (libsource (lib "eagle-import") (part "PAD.04"))
    )
    (comp (ref "FMU-BOOT1101")
      (value "PAD.04")
      (footprint "eagle-import:PAD.04X.04")
      (libsource (lib "eagle-import") (part "PAD.04"))
    )
    (comp (ref "GND")
      (value "PAD.04")
      (footprint "eagle-import:PAD.04X.04")
      (libsource (lib "eagle-import") (part "PAD.04"))
    )
    (comp (ref "GND.")
      (value "PAD.04")
      (footprint "eagle-import:PAD.04X.04")
      (libsource (lib "eagle-import") (part "PAD.04"))
    )
    (comp (ref "IO-BOOT1101")
      (value "PAD.04")
      (footprint "eagle-import:PAD.04X.04")
      (libsource (lib "eagle-import") (part "PAD.04"))
    )
    (comp (ref "JP1")
      (value "FIDUCIAL1.5X3")
      (footprint "eagle-import:FIDUCIAL-1.5X3")
      (libsource (lib "eagle-import") (part "FIDUCIAL1.5X3"))
    )
    (comp (ref "JP2")
      (value "FIDUCIAL1.5X3")
      (footprint "eagle-import:FIDUCIAL-1.5X3")
      (libsource (lib "eagle-import") (part "FIDUCIAL1.5X3"))
    )
    (comp (ref "M3_MOUNT1101")
      (value "MOUNT-HOLE3.1MM")
      (footprint "eagle-import:MOUNT-HOLE3.1")
      (libsource (lib "eagle-import") (part "MOUNT-HOLE3.1MM"))
    )
    (comp (ref "M3_MOUNT1102")
      (value "MOUNT-HOLE3.1MM")
      (footprint "eagle-import:MOUNT-HOLE3.1")
      (libsource (lib "eagle-import") (part "MOUNT-HOLE3.1MM"))
    )
    (comp (ref "M3_MOUNT1103")
      (value "MOUNT-HOLE3.1MM")
      (footprint "eagle-import:MOUNT-HOLE3.1")
      (libsource (lib "eagle-import") (part "MOUNT-HOLE3.1MM"))
    )
    (comp (ref "M3_MOUNT1104")
      (value "MOUNT-HOLE3.1MM")
      (footprint "eagle-import:MOUNT-HOLE3.1")
      (libsource (lib "eagle-import") (part "MOUNT-HOLE3.1MM"))
    )
    (comp (ref "OSHW_LOGO")
      (value "OSHW-LOGOS")
      (footprint "eagle-import:OSHW-LOGO-S")
      (libsource (lib "eagle-import") (part "OSHW-LOGOS"))
    )
    (comp (ref "S1RX")
      (value "PAD.04")
      (footprint "eagle-import:PAD.04X.04")
      (libsource (lib "eagle-import") (part "PAD.04"))
    )
    (comp (ref "S1TX")
      (value "PAD.04")
      (footprint "eagle-import:PAD.04X.04")
      (libsource (lib "eagle-import") (part "PAD.04"))
    )
    (comp (ref "S2RX")
      (value "PAD.04")
      (footprint "eagle-import:PAD.04X.04")
      (libsource (lib "eagle-import") (part "PAD.04"))
    )
    (comp (ref "S2TX")
      (value "PAD.04")
      (footprint "eagle-import:PAD.04X.04")
      (libsource (lib "eagle-import") (part "PAD.04"))
    )
    (comp (ref "S3RX")
      (value "PAD.04")
      (footprint "eagle-import:PAD.04X.04")
      (libsource (lib "eagle-import") (part "PAD.04"))
    )
    (comp (ref "S3TX")
      (value "PAD.04")
      (footprint "eagle-import:PAD.04X.04")
      (libsource (lib "eagle-import") (part "PAD.04"))
    )
    (comp (ref "S4RX")
      (value "PAD.04")
      (footprint "eagle-import:PAD.04X.04")
      (libsource (lib "eagle-import") (part "PAD.04"))
    )
    (comp (ref "S4TX")
      (value "PAD.04")
      (footprint "eagle-import:PAD.04X.04")
      (libsource (lib "eagle-import") (part "PAD.04"))
    )
    (comp (ref "S5_RX")
      (value "PAD.04")
      (footprint "eagle-import:PAD.04X.04")
      (libsource (lib "eagle-import") (part "PAD.04"))
    )
    (comp (ref "S5_TX")
      (value "PAD.04")
      (footprint "eagle-import:PAD.04X.04")
      (libsource (lib "eagle-import") (part "PAD.04"))
    )
    (comp (ref "VDDA_3V1101")
      (value "PAD.04")
      (footprint "eagle-import:PAD.04X.04")
      (libsource (lib "eagle-import") (part "PAD.04"))
    )
    (comp (ref "VDD_3V1101")
      (value "PAD.04")
      (footprint "eagle-import:PAD.04X.04")
      (libsource (lib "eagle-import") (part "PAD.04"))
    )
    (comp (ref "VDD_5V_BRICK")
      (value "PAD.04")
      (footprint "eagle-import:PAD.04X.04")
      (libsource (lib "eagle-import") (part "PAD.04"))
    )
    (comp (ref "C201")
      (value "0u1")
      (footprint "eagle-import:0402-CAP")
      (fields (field (name "PARTNO") "CC0402ZRY5V7BB104"))
      (libsource (lib "eagle-import") (part "CAP0402"))
    )
    (comp (ref "C202")
      (value "0u1")
      (footprint "eagle-import:0402-CAP")
      (fields (field (name "PARTNO") "CC0402ZRY5V7BB104"))
      (libsource (lib "eagle-import") (part "CAP0402"))
    )
    (comp (ref "J201")
      (value "DF13C-6P-1.25V")
      (footprint "eagle-import:DF13C-6P-1.25V")
      (fields (field (name "PARTNO") "DF13C-6P-1.25V(20)"))
      (libsource (lib "eagle-import") (part "DF13-6P-1.25V"))
    )
    (comp (ref "J202")
      (value "DF13C-6P-1.25V")
      (footprint "eagle-import:DF13C-6P-1.25V")
      (fields (field (name "PARTNO") "DF13C-6P-1.25V(20)"))
      (libsource (lib "eagle-import") (part "DF13-6P-1.25V"))
    )
    (comp (ref "J203")
      (value "DF13C-6P-1.25V")
      (footprint "eagle-import:DF13C-6P-1.25V")
      (fields (field (name "PARTNO") "DF13C-6P-1.25V(20)"))
      (libsource (lib "eagle-import") (part "DF13-6P-1.25V"))
    )
    (comp (ref "J204")
      (value "DF13C-6P-1.25V")
      (footprint "eagle-import:DF13C-6P-1.25V")
      (fields (field (name "PARTNO") "DF13C-6P-1.25V(20)"))
      (libsource (lib "eagle-import") (part "DF13-6P-1.25V"))
    )
    (comp (ref "L201")
      (value "KNH16C104DA5TS")
      (footprint "eagle-import:KYOCERA-KNH16-DA")
      (libsource (lib "eagle-import") (part "KNH16C104DA5TS"))
    )
    (comp (ref "L202")
      (value "KNH16C104DA5TS")
      (footprint "eagle-import:KYOCERA-KNH16-DA")
      (libsource (lib "eagle-import") (part "KNH16C104DA5TS"))
    )
    (comp (ref "L203")
      (value "KNH16C104DA5TS")
      (footprint "eagle-import:KYOCERA-KNH16-DA")
      (libsource (lib "eagle-import") (part "KNH16C104DA5TS"))
    )
    (comp (ref "R12")
      (value "120R")
      (footprint "eagle-import:0402-RES")
      (fields (field (name "PARTNO") "RC0402FR-07120RL"))
      (libsource (lib "eagle-import") (part "RESISTOR0402-RES"))
    )
    (comp (ref "R13")
      (value "120R")
      (footprint "eagle-import:0402-RES")
      (fields (field (name "PARTNO") "RC0402FR-07120RL"))
      (libsource (lib "eagle-import") (part "RESISTOR0402-RES"))
    )
    (comp (ref "R201")
      (value "120R")
      (footprint "eagle-import:0402-RES")
      (fields (field (name "PARTNO") "RC0402FR-07120RL"))
      (libsource (lib "eagle-import") (part "RESISTOR0402-RES"))
    )
    (comp (ref "R202")
      (value "120R")
      (footprint "eagle-import:0402-RES")
      (fields (field (name "PARTNO") "RC0402FR-07120RL"))
      (libsource (lib "eagle-import") (part "RESISTOR0402-RES"))
    )
    (comp (ref "R203")
      (value "120R")
      (footprint "eagle-import:0402-RES")
      (fields (field (name "PARTNO") "RC0402FR-07120RL"))
      (libsource (lib "eagle-import") (part "RESISTOR0402-RES"))
    )
    (comp (ref "R204")
      (value "120R")
      (footprint "eagle-import:0402-RES")
      (fields (field (name "PARTNO") "RC0402FR-07120RL"))
      (libsource (lib "eagle-import") (part "RESISTOR0402-RES"))
    )
    (comp (ref "R205")
      (value "120R")
      (footprint "eagle-import:0402-RES")
      (fields (field (name "PARTNO") "RC0402FR-07120RL"))
      (libsource (lib "eagle-import") (part "RESISTOR0402-RES"))
    )
    (comp (ref "R206")
      (value "120R")
      (footprint "eagle-import:0402-RES")
      (fields (field (name "PARTNO") "RC0402FR-07120RL"))
      (libsource (lib "eagle-import") (part "RESISTOR0402-RES"))
    )
    (comp (ref "R207")
      (value "120R")
      (footprint "eagle-import:0402-RES")
      (fields (field (name "PARTNO") "RC0402FR-07120RL"))
      (libsource (lib "eagle-import") (part "RESISTOR0402-RES"))
    )
    (comp (ref "R208")
      (value "120R")
      (footprint "eagle-import:0402-RES")
      (fields (field (name "PARTNO") "RC0402FR-07120RL"))
      (libsource (lib "eagle-import") (part "RESISTOR0402-RES"))
    )
    (comp (ref "R209")
      (value "120R")
      (footprint "eagle-import:0402-RES")
      (fields (field (name "PARTNO") "RC0402FR-07120RL"))
      (libsource (lib "eagle-import") (part "RESISTOR0402-RES"))
    )
    (comp (ref "R210")
      (value "120R")
      (footprint "eagle-import:0402-RES")
      (fields (field (name "PARTNO") "RC0402FR-07120RL"))
      (libsource (lib "eagle-import") (part "RESISTOR0402-RES"))
    )
    (comp (ref "R211")
      (value "120R")
      (footprint "eagle-import:0402-RES")
      (fields (field (name "PARTNO") "RC0402FR-07120RL"))
      (libsource (lib "eagle-import") (part "RESISTOR0402-RES"))
    )
    (comp (ref "R212")
      (value "120R")
      (footprint "eagle-import:0402-RES")
      (fields (field (name "PARTNO") "RC0402FR-07120RL"))
      (libsource (lib "eagle-import") (part "RESISTOR0402-RES"))
    )
    (comp (ref "R213")
      (value "120R")
      (footprint "eagle-import:0402-RES")
      (fields (field (name "PARTNO") "RC0402FR-07120RL"))
      (libsource (lib "eagle-import") (part "RESISTOR0402-RES"))
    )
    (comp (ref "R214")
      (value "120R")
      (footprint "eagle-import:0402-RES")
      (fields (field (name "PARTNO") "RC0402FR-07120RL"))
      (libsource (lib "eagle-import") (part "RESISTOR0402-RES"))
    )
    (comp (ref "U$201")
      (value "PESD0402-140")
      (footprint "eagle-import:0402-TVS")
      (libsource (lib "eagle-import") (part "DIODE-TVS"))
    )
    (comp (ref "U$202")
      (value "PESD0402-140")
      (footprint "eagle-import:0402-TVS")
      (libsource (lib "eagle-import") (part "DIODE-TVS"))
    )
    (comp (ref "U$203")
      (value "PESD0402-140")
      (footprint "eagle-import:0402-TVS")
      (libsource (lib "eagle-import") (part "DIODE-TVS"))
    )
    (comp (ref "U201")
      (value "TXS0108QFN20")
      (footprint "eagle-import:QFN20-RGY")
      (fields (field (name "PARTNO") "TXS0108ERGYR"))
      (libsource (lib "eagle-import") (part "TXS0108QFN20"))
    )
    (comp (ref "U202")
      (value "TXS0108QFN20")
      (footprint "eagle-import:QFN20-RGY")
      (fields (field (name "PARTNO") "TXS0108ERGYR"))
      (libsource (lib "eagle-import") (part "TXS0108QFN20"))
    )
    (comp (ref "J601")
      (value "DF13C-6P-1.25V")
      (footprint "eagle-import:DF13C-6P-1.25V")
      (fields (field (name "PARTNO") "DF13C-6P-1.25V(20)"))
      (libsource (lib "eagle-import") (part "DF13-6P-1.25V"))
    )
    (comp (ref "L601")
      (value "KNH16C104DA5TS")
      (footprint "eagle-import:KYOCERA-KNH16-DA")
      (libsource (lib "eagle-import") (part "KNH16C104DA5TS"))
    )
    (comp (ref "L602")
      (value "KNH16C104DA5TS")
      (footprint "eagle-import:KYOCERA-KNH16-DA")
      (libsource (lib "eagle-import") (part "KNH16C104DA5TS"))
    )
    (comp (ref "R1")
      (value "453K")
      (footprint "eagle-import:0402-RES")
      (fields (field (name "PARTNO") "RMCF0402FT453K"))
      (libsource (lib "eagle-import") (part "RESISTOR0402-RES"))
    )
    (comp (ref "R2")
      (value "45.3K")
      (footprint "eagle-import:0402-RES")
      (libsource (lib "eagle-import") (part "RESISTOR0402-RES"))
    )
    (comp (ref "R5")
      (value "105K")
      (footprint "eagle-import:0402-RES")
      (libsource (lib "eagle-import") (part "RESISTOR0402-RES"))
    )
    (comp (ref "R6")
      (value "453K")
      (footprint "eagle-import:0402-RES")
      (fields (field (name "PARTNO") "RMCF0402FT453K"))
      (libsource (lib "eagle-import") (part "RESISTOR0402-RES"))
    )
    (comp (ref "R7")
      (value "45.3K")
      (footprint "eagle-import:0402-RES")
      (libsource (lib "eagle-import") (part "RESISTOR0402-RES"))
    )
    (comp (ref "R8")
      (value "105K")
      (footprint "eagle-import:0402-RES")
      (libsource (lib "eagle-import") (part "RESISTOR0402-RES"))
    )
    (comp (ref "R9")
      (value "453K")
      (footprint "eagle-import:0402-RES")
      (fields (field (name "PARTNO") "RMCF0402FT453K"))
      (libsource (lib "eagle-import") (part "RESISTOR0402-RES"))
    )
    (comp (ref "R10")
      (value "45.3K")
      (footprint "eagle-import:0402-RES")
      (libsource (lib "eagle-import") (part "RESISTOR0402-RES"))
    )
    (comp (ref "R11")
      (value "105K")
      (footprint "eagle-import:0402-RES")
      (libsource (lib "eagle-import") (part "RESISTOR0402-RES"))
    )
    (comp (ref "R604")
      (value "10K/0.1%")
      (footprint "eagle-import:0402-RES")
      (fields (field (name "PARTNO") "ERA-2AEB103X"))
      (libsource (lib "eagle-import") (part "RESISTOR0402-RES"))
    )
    (comp (ref "R605")
      (value "10K/0.1%")
      (footprint "eagle-import:0402-RES")
      (fields (field (name "PARTNO") "ERA-2AEB103X"))
      (libsource (lib "eagle-import") (part "RESISTOR0402-RES"))
    )
    (comp (ref "U$2")
      (value "LTC4417")
      (footprint "eagle-import:MO-220")
      (libsource (lib "eagle-import") (part "LTC4117"))
    )
    (comp (ref "U$3")
      (value "NTHD4102P")
      (footprint "eagle-import:1206-8")
      (fields (field (name "PARTNO") "*"))
      (libsource (lib "eagle-import") (part "MOSFET-DUAL-PCHANNEL-CHIPFET"))
    )
    (comp (ref "U$4")
      (value "NTHD4102P")
      (footprint "eagle-import:1206-8")
      (fields (field (name "PARTNO") "*"))
      (libsource (lib "eagle-import") (part "MOSFET-DUAL-PCHANNEL-CHIPFET"))
    )
    (comp (ref "U$5")
      (value "NTHD4102P")
      (footprint "eagle-import:1206-8")
      (fields (field (name "PARTNO") "*"))
      (libsource (lib "eagle-import") (part "MOSFET-DUAL-PCHANNEL-CHIPFET"))
    )
    (comp (ref "B601")
      (value "DO NOT PLACE")
      (footprint "eagle-import:MS621FE")
      (fields (field (name "PARTNO") "MS621FE-FL11E"))
      (libsource (lib "eagle-import") (part "MS621FE"))
    )
    (comp (ref "C601")
      (value "2u2")
      (footprint "eagle-import:0603-CAP")
      (fields (field (name "PARTNO") "C1608Y5V1C225Z"))
      (libsource (lib "eagle-import") (part "CAP0603"))
    )
    (comp (ref "C602")
      (value "10n")
      (footprint "eagle-import:0402-CAP")
      (fields (field (name "PARTNO") "CC0402KRX7R7BB103"))
      (libsource (lib "eagle-import") (part "CAP0402"))
    )
    (comp (ref "C603")
      (value "1u0")
      (footprint "eagle-import:0603-CAP")
      (fields (field (name "PARTNO") "CC0603ZRY5V7BB105"))
      (libsource (lib "eagle-import") (part "CAP0603"))
    )
    (comp (ref "C604")
      (value "10u/10V")
      (footprint "eagle-import:0805-CAP")
      (fields (field (name "PARTNO") "CC0805ZKY5V6BB106"))
      (libsource (lib "eagle-import") (part "CAP0805"))
    )
    (comp (ref "C605")
      (value "1u0")
      (footprint "eagle-import:0603-CAP")
      (fields (field (name "PARTNO") "CC0603ZRY5V7BB105"))
      (libsource (lib "eagle-import") (part "CAP0603"))
    )
    (comp (ref "C606")
      (value "0u1")
      (footprint "eagle-import:0402-CAP")
      (fields (field (name "PARTNO") "CC0402ZRY5V7BB104"))
      (libsource (lib "eagle-import") (part "CAP0402"))
    )
    (comp (ref "C607")
      (value "0u1")
      (footprint "eagle-import:0402-CAP")
      (fields (field (name "PARTNO") "CC0402ZRY5V7BB104"))
      (libsource (lib "eagle-import") (part "CAP0402"))
    )
    (comp (ref "C608")
      (value "0u1")
      (footprint "eagle-import:0402-CAP")
      (fields (field (name "PARTNO") "CC0402ZRY5V7BB104"))
      (libsource (lib "eagle-import") (part "CAP0402"))
    )
    (comp (ref "C609")
      (value "0u1")
      (footprint "eagle-import:0402-CAP")
      (fields (field (name "PARTNO") "CC0402ZRY5V7BB104"))
      (libsource (lib "eagle-import") (part "CAP0402"))
    )
    (comp (ref "C610")
      (value "0u1")
      (footprint "eagle-import:0402-CAP")
      (fields (field (name "PARTNO") "CC0402ZRY5V7BB104"))
      (libsource (lib "eagle-import") (part "CAP0402"))
    )
    (comp (ref "C611")
      (value "2u2")
      (footprint "eagle-import:0603-CAP")
      (fields (field (name "PARTNO") "C1608Y5V1C225Z"))
      (libsource (lib "eagle-import") (part "CAP0603"))
    )
    (comp (ref "C612")
      (value "0u1")
      (footprint "eagle-import:0402-CAP")
      (fields (field (name "PARTNO") "CC0402ZRY5V7BB104"))
      (libsource (lib "eagle-import") (part "CAP0402"))
    )
    (comp (ref "C613")
      (value "2u2")
      (footprint "eagle-import:0603-CAP")
      (fields (field (name "PARTNO") "C1608Y5V1C225Z"))
      (libsource (lib "eagle-import") (part "CAP0603"))
    )
    (comp (ref "L603")
      (value "KNH16C104DA5TS")
      (footprint "eagle-import:KYOCERA-KNH16-DA")
      (libsource (lib "eagle-import") (part "KNH16C104DA5TS"))
    )
    (comp (ref "R602")
      (value "16K5")
      (footprint "eagle-import:0402-RES")
      (fields (field (name "PARTNO") "RMCF0402FT16K5"))
      (libsource (lib "eagle-import") (part "RESISTOR0402-RES"))
    )
    (comp (ref "R603")
      (value "10K")
      (footprint "eagle-import:0402-RES")
      (fields (field (name "PARTNO") "RC0402FR-0710KL"))
      (libsource (lib "eagle-import") (part "RESISTOR0402-RES"))
    )
    (comp (ref "R606")
      (value "25K")
      (footprint "eagle-import:0402-RES")
      (fields (field (name "PARTNO") "RMCF0402FT25K5"))
      (libsource (lib "eagle-import") (part "RESISTOR0402-RES"))
    )
    (comp (ref "R607")
      (value "10K")
      (footprint "eagle-import:0402-RES")
      (fields (field (name "PARTNO") "RC0402FR-0710KL"))
      (libsource (lib "eagle-import") (part "RESISTOR0402-RES"))
    )
    (comp (ref "R608")
      (value "1K")
      (footprint "eagle-import:0402-RES")
      (fields (field (name "PARTNO") "RC0402FR-071KL"))
      (libsource (lib "eagle-import") (part "RESISTOR0402-RES"))
    )
    (comp (ref "R609")
      (value "10K/0.1%")
      (footprint "eagle-import:0402-RES")
      (fields (field (name "PARTNO") "ERA-2AEB103X"))
      (libsource (lib "eagle-import") (part "RESISTOR0402-RES"))
    )
    (comp (ref "R610")
      (value "10K/0.1%")
      (footprint "eagle-import:0402-RES")
      (fields (field (name "PARTNO") "ERA-2AEB103X"))
      (libsource (lib "eagle-import") (part "RESISTOR0402-RES"))
    )
    (comp (ref "R611")
      (value "10K")
      (footprint "eagle-import:0402-RES")
      (fields (field (name "PARTNO") "RC0402FR-0710KL"))
      (libsource (lib "eagle-import") (part "RESISTOR0402-RES"))
    )
    (comp (ref "S601")
      (value "RESET")
      (footprint "eagle-import:EVQP7J01K")
      (fields (field (name "PARTNO") "EVQP7J01K"))
      (libsource (lib "eagle-import") (part "SWITCH-MOMENTARY-2"))
    )
    (comp (ref "U$602")
      (value "BQ24315")
      (footprint "eagle-import:QFN8-DSG")
      (fields (field (name "PARTNO") "BQ24315DSGR"))
      (libsource (lib "eagle-import") (part "BQ24315"))
    )
    (comp (ref "U$604")
      (value "BQ24315")
      (footprint "eagle-import:QFN8-DSG")
      (fields (field (name "PARTNO") "BQ24315DSGR"))
      (libsource (lib "eagle-import") (part "BQ24315"))
    )
    (comp (ref "U$605")
      (value "MIC5332")
      (footprint "eagle-import:MLF-8-EPAD")
      (fields (field (name "PARTNO") "MIC5332-SSYMT"))
      (libsource (lib "eagle-import") (part "MIC5332"))
    )
    (comp (ref "U101")
      (value "STM32F4X7VX")
      (footprint "eagle-import:TQFP100")
      (fields (field (name "PARTNO") "STM32F427VI"))
      (libsource (lib "eagle-import") (part "STM32F4X7VX"))
    )
    (comp (ref "C801")
      (value "0u1")
      (footprint "eagle-import:0402-CAP")
      (fields (field (name "PARTNO") "CC0402ZRY5V7BB104"))
      (libsource (lib "eagle-import") (part "CAP0402"))
    )
    (comp (ref "C802")
      (value "0u1")
      (footprint "eagle-import:0402-CAP")
      (fields (field (name "PARTNO") "CC0402ZRY5V7BB104"))
      (libsource (lib "eagle-import") (part "CAP0402"))
    )
    (comp (ref "C803")
      (value "0u1")
      (footprint "eagle-import:0402-CAP")
      (fields (field (name "PARTNO") "CC0402ZRY5V7BB104"))
      (libsource (lib "eagle-import") (part "CAP0402"))
    )
    (comp (ref "C804")
      (value "0u1")
      (footprint "eagle-import:0402-CAP")
      (fields (field (name "PARTNO") "CC0402ZRY5V7BB104"))
      (libsource (lib "eagle-import") (part "CAP0402"))
    )
    (comp (ref "C805")
      (value "8p")
      (footprint "eagle-import:0402-CAP")
      (fields (field (name "PARTNO") "C1005C0G1H080C"))
      (libsource (lib "eagle-import") (part "CAP0402"))
    )
    (comp (ref "C806")
      (value "8p")
      (footprint "eagle-import:0402-CAP")
      (fields (field (name "PARTNO") "C1005C0G1H080C"))
      (libsource (lib "eagle-import") (part "CAP0402"))
    )
    (comp (ref "J801")
      (value "JST-ZH-3")
      (footprint "eagle-import:JST-ZH-SMT-VERTICAL")
      (fields (field (name "PARTNO") "B3B-ZR-SM4-TF (LF)(SN)(P)"))
      (libsource (lib "eagle-import") (part "JST-ZH-3"))
    )
    (comp (ref "JX801")
      (value "HEADER-3X1BOARDEDGE-SHORT")
      (footprint "eagle-import:HEADER_3X01_SMD_H_BOARD_EDGE_SHORT")
      (libsource (lib "eagle-import") (part "HEADER-3X1BOARDEDGE-SHORT"))
    )
    (comp (ref "JX802")
      (value "ARM_MINI_JTAG-SMT")
      (footprint "eagle-import:FTSH-105-01-XXX-DV-K")
      (fields (field (name "BOM") "EXCLUDE") (field (name "PARTNO") "M50-3900542"))
      (libsource (lib "eagle-import") (part "ARM_MINI_JTAG-SMT"))
    )
    (comp (ref "R801")
      (value "10K")
      (footprint "eagle-import:0402-RES")
      (fields (field (name "PARTNO") "RC0402FR-0710KL"))
      (libsource (lib "eagle-import") (part "RESISTOR0402-RES"))
    )
    (comp (ref "R802")
      (value "10K")
      (footprint "eagle-import:0402-RES")
      (fields (field (name "PARTNO") "RC0402FR-0710KL"))
      (libsource (lib "eagle-import") (part "RESISTOR0402-RES"))
    )
    (comp (ref "R803")
      (value "220R")
      (footprint "eagle-import:0402-RES")
      (fields (field (name "PARTNO") "RC0402FR-07220RL"))
      (libsource (lib "eagle-import") (part "RESISTOR0402-RES"))
    )
    (comp (ref "R804")
      (value "220R")
      (footprint "eagle-import:0402-RES")
      (fields (field (name "PARTNO") "RC0402FR-07220RL"))
      (libsource (lib "eagle-import") (part "RESISTOR0402-RES"))
    )
    (comp (ref "S801")
      (value "RESET")
      (footprint "eagle-import:EVQP7J01K")
      (fields (field (name "PARTNO") "EVQP7J01K"))
      (libsource (lib "eagle-import") (part "SWITCH-MOMENTARY-2"))
    )
    (comp (ref "U$801")
      (value "PESD0402-140")
      (footprint "eagle-import:0402-TVS")
      (libsource (lib "eagle-import") (part "DIODE-TVS"))
    )
    (comp (ref "U801")
      (value "STM32F10XCXT6")
      (footprint "eagle-import:TQFP48")
      (fields (field (name "PARTNO") "STM32F100C8T6B"))
      (libsource (lib "eagle-import") (part "STM32F10XCXT6"))
    )
    (comp (ref "X801")
      (value "3.2x2.5 mm / 24 MHz / 15 ppm")
      (footprint "eagle-import:OSCILLATOR-3.2X2.5")
      (fields (field (name "PARTNO") "NX3225SA-24.000000MHZ"))
      (libsource (lib "eagle-import") (part "OSCILLATOR-3.2X2.5"))
    )
    (comp (ref "C101")
      (value "0u1")
      (footprint "eagle-import:0402-CAP")
      (fields (field (name "PARTNO") "CC0402ZRY5V7BB104"))
      (libsource (lib "eagle-import") (part "CAP0402"))
    )
    (comp (ref "C102")
      (value "8p")
      (footprint "eagle-import:0402-CAP")
      (fields (field (name "PARTNO") "C1005C0G1H080C"))
      (libsource (lib "eagle-import") (part "CAP0402"))
    )
    (comp (ref "C103")
      (value "8p")
      (footprint "eagle-import:0402-CAP")
      (fields (field (name "PARTNO") "C1005C0G1H080C"))
      (libsource (lib "eagle-import") (part "CAP0402"))
    )
    (comp (ref "R101")
      (value "470R")
      (footprint "eagle-import:0402-RES")
      (fields (field (name "PARTNO") "RC0402FR-07470RL"))
      (libsource (lib "eagle-import") (part "RESISTOR0402-RES"))
    )
    (comp (ref "R102")
      (value "10K")
      (footprint "eagle-import:0402-RES")
      (fields (field (name "PARTNO") "RC0402FR-0710KL"))
      (libsource (lib "eagle-import") (part "RESISTOR0402-RES"))
    )
    (comp (ref "U102")
      (value "FM25V01")
      (footprint "eagle-import:SO08")
      (fields (field (name "PARTNO") "FM25V01-G"))
      (libsource (lib "eagle-import") (part "FM25V01"))
    )
    (comp (ref "X101")
      (value "3.2x2.5 mm / 24 MHz / 15 ppm")
      (footprint "eagle-import:OSCILLATOR-3.2X2.5")
      (fields (field (name "PARTNO") "NX3225SA-24.000000MHZ"))
      (libsource (lib "eagle-import") (part "OSCILLATOR-3.2X2.5"))
    )
    (comp (ref "C901")
      (value "0u1")
      (footprint "eagle-import:0402-CAP")
      (fields (field (name "PARTNO") "CC0402ZRY5V7BB104"))
      (libsource (lib "eagle-import") (part "CAP0402"))
    )
    (comp (ref "C902")
      (value "0u1")
      (footprint "eagle-import:0402-CAP")
      (fields (field (name "PARTNO") "CC0402ZRY5V7BB104"))
      (libsource (lib "eagle-import") (part "CAP0402"))
    )
    (comp (ref "C903")
      (value "0u1")
      (footprint "eagle-import:0402-CAP")
      (fields (field (name "PARTNO") "CC0402ZRY5V7BB104"))
      (libsource (lib "eagle-import") (part "CAP0402"))
    )
    (comp (ref "D1")
      (value "MSS1P4-M3")
      (footprint "eagle-import:MICROSMP")
      (fields (field (name "PARTNO") "MSS1P4-M3/89A"))
      (libsource (lib "eagle-import") (part "DIODE-SCHOTTKY_MSMP"))
    )
    (comp (ref "J901")
      (value "HEADER-3X163X16RA")
      (footprint "eagle-import:3X16RA")
      (fields (field (name "BOM") "EXCLUDE"))
      (libsource (lib "eagle-import") (part "HEADER-3X163X16RA"))
    )
    (comp (ref "L901")
      (value "KNH16C104DA5TS")
      (footprint "eagle-import:KYOCERA-KNH16-DA")
      (libsource (lib "eagle-import") (part "KNH16C104DA5TS"))
    )
    (comp (ref "R901")
      (value "10K")
      (footprint "eagle-import:0402-RES")
      (fields (field (name "PARTNO") "RC0402FR-0710KL"))
      (libsource (lib "eagle-import") (part "RESISTOR0402-RES"))
    )
    (comp (ref "R902")
      (value "220R")
      (footprint "eagle-import:0402-RES")
      (fields (field (name "PARTNO") "RC0402FR-07220RL"))
      (libsource (lib "eagle-import") (part "RESISTOR0402-RES"))
    )
    (comp (ref "R903")
      (value "220R")
      (footprint "eagle-import:0402-RES")
      (fields (field (name "PARTNO") "RC0402FR-07220RL"))
      (libsource (lib "eagle-import") (part "RESISTOR0402-RES"))
    )
    (comp (ref "R904")
      (value "220R")
      (footprint "eagle-import:0402-RES")
      (fields (field (name "PARTNO") "RC0402FR-07220RL"))
      (libsource (lib "eagle-import") (part "RESISTOR0402-RES"))
    )
    (comp (ref "R905")
      (value "220R")
      (footprint "eagle-import:0402-RES")
      (fields (field (name "PARTNO") "RC0402FR-07220RL"))
      (libsource (lib "eagle-import") (part "RESISTOR0402-RES"))
    )
    (comp (ref "R906")
      (value "220R")
      (footprint "eagle-import:0402-RES")
      (fields (field (name "PARTNO") "RC0402FR-07220RL"))
      (libsource (lib "eagle-import") (part "RESISTOR0402-RES"))
    )
    (comp (ref "R907")
      (value "220R")
      (footprint "eagle-import:0402-RES")
      (fields (field (name "PARTNO") "RC0402FR-07220RL"))
      (libsource (lib "eagle-import") (part "RESISTOR0402-RES"))
    )
    (comp (ref "R908")
      (value "220R")
      (footprint "eagle-import:0402-RES")
      (fields (field (name "PARTNO") "RC0402FR-07220RL"))
      (libsource (lib "eagle-import") (part "RESISTOR0402-RES"))
    )
    (comp (ref "R909")
      (value "220R")
      (footprint "eagle-import:0402-RES")
      (fields (field (name "PARTNO") "RC0402FR-07220RL"))
      (libsource (lib "eagle-import") (part "RESISTOR0402-RES"))
    )
    (comp (ref "R910")
      (value "220R")
      (footprint "eagle-import:0402-RES")
      (fields (field (name "PARTNO") "RC0402FR-07220RL"))
      (libsource (lib "eagle-import") (part "RESISTOR0402-RES"))
    )
    (comp (ref "R911")
      (value "220R")
      (footprint "eagle-import:0402-RES")
      (fields (field (name "PARTNO") "RC0402FR-07220RL"))
      (libsource (lib "eagle-import") (part "RESISTOR0402-RES"))
    )
    (comp (ref "R912")
      (value "220R")
      (footprint "eagle-import:0402-RES")
      (fields (field (name "PARTNO") "RC0402FR-07220RL"))
      (libsource (lib "eagle-import") (part "RESISTOR0402-RES"))
    )
    (comp (ref "R913")
      (value "220R")
      (footprint "eagle-import:0402-RES")
      (fields (field (name "PARTNO") "RC0402FR-07220RL"))
      (libsource (lib "eagle-import") (part "RESISTOR0402-RES"))
    )
    (comp (ref "R914")
      (value "220R")
      (footprint "eagle-import:0402-RES")
      (fields (field (name "PARTNO") "RC0402FR-07220RL"))
      (libsource (lib "eagle-import") (part "RESISTOR0402-RES"))
    )
    (comp (ref "R915")
      (value "220R")
      (footprint "eagle-import:0402-RES")
      (fields (field (name "PARTNO") "RC0402FR-07220RL"))
      (libsource (lib "eagle-import") (part "RESISTOR0402-RES"))
    )
    (comp (ref "R916")
      (value "220R")
      (footprint "eagle-import:0402-RES")
      (fields (field (name "PARTNO") "RC0402FR-07220RL"))
      (libsource (lib "eagle-import") (part "RESISTOR0402-RES"))
    )
    (comp (ref "R917")
      (value "220R")
      (footprint "eagle-import:0402-RES")
      (fields (field (name "PARTNO") "RC0402FR-07220RL"))
      (libsource (lib "eagle-import") (part "RESISTOR0402-RES"))
    )
    (comp (ref "R918")
      (value "10K/0.1%")
      (footprint "eagle-import:0402-RES")
      (fields (field (name "PARTNO") "ERA-2AEB103X"))
      (libsource (lib "eagle-import") (part "RESISTOR0402-RES"))
    )
    (comp (ref "R919")
      (value "10K/0.1%")
      (footprint "eagle-import:0402-RES")
      (fields (field (name "PARTNO") "ERA-2AEB103X"))
      (libsource (lib "eagle-import") (part "RESISTOR0402-RES"))
    )
    (comp (ref "R922")
      (value "10K/0.1%")
      (footprint "eagle-import:0402-RES")
      (fields (field (name "PARTNO") "ERA-2AEB103X"))
      (libsource (lib "eagle-import") (part "RESISTOR0402-RES"))
    )
    (comp (ref "U$6")
      (value "PESD0402-140")
      (footprint "eagle-import:0402-TVS")
      (libsource (lib "eagle-import") (part "DIODE-TVS"))
    )
    (comp (ref "U$901")
      (value "PESD0402-140")
      (footprint "eagle-import:0402-TVS")
      (libsource (lib "eagle-import") (part "DIODE-TVS"))
    )
    (comp (ref "U$902")
      (value "PESD0402-140")
      (footprint "eagle-import:0402-TVS")
      (libsource (lib "eagle-import") (part "DIODE-TVS"))
    )
    (comp (ref "U901")
      (value "TXS0108QFN20")
      (footprint "eagle-import:QFN20-RGY")
      (fields (field (name "PARTNO") "TXS0108ERGYR"))
      (libsource (lib "eagle-import") (part "TXS0108QFN20"))
    )
    (comp (ref "U902")
      (value "TXS0108QFN20")
      (footprint "eagle-import:QFN20-RGY")
      (fields (field (name "PARTNO") "TXS0108ERGYR"))
      (libsource (lib "eagle-import") (part "TXS0108QFN20"))
    )
    (comp (ref "U903")
      (value "74LVC2G240")
      (footprint "eagle-import:TSSOP8_SOT505-2")
      (fields (field (name "PARTNO") "74LVC2G240DP,125"))
      (libsource (lib "eagle-import") (part "74LVC2G240-TSSOP-8"))
    )
    (comp (ref "J301")
      (value "47346-0001")
      (footprint "eagle-import:MOLEX-47346-0001")
      (libsource (lib "eagle-import") (part "MOLEX-47346-0001"))
    )
    (comp (ref "J302")
      (value "DF13C-4P-1.25V")
      (footprint "eagle-import:DF13C-4P-1.25V")
      (fields (field (name "PARTNO") "DF13C-4P-1.25V(20)"))
      (libsource (lib "eagle-import") (part "DF13-4P-1.25V"))
    )
    (comp (ref "JX301")
      (value "ARM_MINI_JTAG-SMT")
      (footprint "eagle-import:FTSH-105-01-XXX-DV-K")
      (fields (field (name "BOM") "EXCLUDE") (field (name "PARTNO") "M50-3900542"))
      (libsource (lib "eagle-import") (part "ARM_MINI_JTAG-SMT"))
    )
    (comp (ref "R301")
      (value "100K")
      (footprint "eagle-import:0402-RES")
      (fields (field (name "PARTNO") "RC0402FR-07100KL"))
      (libsource (lib "eagle-import") (part "RESISTOR0402-RES"))
    )
    (comp (ref "R302")
      (value "100K")
      (footprint "eagle-import:0402-RES")
      (fields (field (name "PARTNO") "RC0402FR-07100KL"))
      (libsource (lib "eagle-import") (part "RESISTOR0402-RES"))
    )
    (comp (ref "R303")
      (value "100K")
      (footprint "eagle-import:0402-RES")
      (fields (field (name "PARTNO") "RC0402FR-07100KL"))
      (libsource (lib "eagle-import") (part "RESISTOR0402-RES"))
    )
    (comp (ref "R304")
      (value "100K")
      (footprint "eagle-import:0402-RES")
      (fields (field (name "PARTNO") "RC0402FR-07100KL"))
      (libsource (lib "eagle-import") (part "RESISTOR0402-RES"))
    )
    (comp (ref "R305")
      (value "100K")
      (footprint "eagle-import:0402-RES")
      (fields (field (name "PARTNO") "RC0402FR-07100KL"))
      (libsource (lib "eagle-import") (part "RESISTOR0402-RES"))
    )
    (comp (ref "R306")
      (value "1K5")
      (footprint "eagle-import:0402-RES")
      (fields (field (name "PARTNO") "RC0402FR-071K5L"))
      (libsource (lib "eagle-import") (part "RESISTOR0402-RES"))
    )
    (comp (ref "R307")
      (value "1K5")
      (footprint "eagle-import:0402-RES")
      (fields (field (name "PARTNO") "RC0402FR-071K5L"))
      (libsource (lib "eagle-import") (part "RESISTOR0402-RES"))
    )
    (comp (ref "U$301")
      (value "NUF2042XV6")
      (footprint "eagle-import:SOT563-6")
      (fields (field (name "PARTNO") "NUF2042XV6T1G"))
      (libsource (lib "eagle-import") (part "NUF2042XV6"))
    )
    (comp (ref "U301")
      (value "2908-05WB-MG")
      (footprint "eagle-import:MICROSD")
      (libsource (lib "eagle-import") (part "MICROSDSDI"))
    )
    (comp (ref "C701")
      (value "0u1")
      (footprint "eagle-import:0402-CAP")
      (fields (field (name "PARTNO") "CC0402ZRY5V7BB104"))
      (libsource (lib "eagle-import") (part "CAP0402"))
    )
    (comp (ref "C702")
      (value "1u0")
      (footprint "eagle-import:0603-CAP")
      (fields (field (name "PARTNO") "CC0603ZRY5V7BB105"))
      (libsource (lib "eagle-import") (part "CAP0603"))
    )
    (comp (ref "C703")
      (value "5n6")
      (footprint "eagle-import:0402-CAP")
      (fields (field (name "PARTNO") "CC0402KRX7R7BB562"))
      (libsource (lib "eagle-import") (part "CAP0402"))
    )
    (comp (ref "C704")
      (value "0u47")
      (footprint "eagle-import:0402-CAP")
      (fields (field (name "PARTNO") "C1005X5R1C474K050BC"))
      (libsource (lib "eagle-import") (part "CAP0402"))
    )
    (comp (ref "J701")
      (value "DF13C-2P-1.25V")
      (footprint "eagle-import:DF13C-2P-1.25V")
      (fields (field (name "PARTNO") "DF13C-2P-1.25V(20)"))
      (libsource (lib "eagle-import") (part "DF13-2P-1.25V"))
    )
    (comp (ref "J702")
      (value "DF13C-3P-1.25V")
      (footprint "eagle-import:DF13C-3P-1.25V")
      (fields (field (name "PARTNO") "DF13C-3P-1.25V(20)"))
      (libsource (lib "eagle-import") (part "DF13-3P-1.25V"))
    )
    (comp (ref "L701")
      (value "47uH")
      (footprint "eagle-import:0805-IND")
      (fields (field (name "PARTNO") "MLZ2012M470W"))
      (libsource (lib "eagle-import") (part "INDUCTOR0805"))
    )
    (comp (ref "LED701")
      (value "AMBER")
      (footprint "eagle-import:0603-LED")
      (fields (field (name "PARTNO") "APTD1608SECK"))
      (libsource (lib "eagle-import") (part "LED0603"))
    )
    (comp (ref "LED702")
      (value "GREEN")
      (footprint "eagle-import:0603-LED")
      (fields (field (name "PARTNO") "APTD1608CGCK"))
      (libsource (lib "eagle-import") (part "LED0603"))
    )
    (comp (ref "LED703")
      (value "AMBER")
      (footprint "eagle-import:0603-LED")
      (fields (field (name "PARTNO") "APTD1608SECK"))
      (libsource (lib "eagle-import") (part "LED0603"))
    )
    (comp (ref "LED704")
      (value "GREEN")
      (footprint "eagle-import:0603-LED")
      (fields (field (name "PARTNO") "APTD1608CGCK"))
      (libsource (lib "eagle-import") (part "LED0603"))
    )
    (comp (ref "LED705")
      (value "BLUE")
      (footprint "eagle-import:0603-LED")
      (fields (field (name "PARTNO") "APTD1608QBC/D"))
      (libsource (lib "eagle-import") (part "LED0603"))
    )
    (comp (ref "R3")
      (value "220R")
      (footprint "eagle-import:0402-RES")
      (fields (field (name "PARTNO") "RC0402FR-07220RL"))
      (libsource (lib "eagle-import") (part "RESISTOR0402-RES"))
    )
    (comp (ref "R4")
      (value "220R")
      (footprint "eagle-import:0402-RES")
      (fields (field (name "PARTNO") "RC0402FR-07220RL"))
      (libsource (lib "eagle-import") (part "RESISTOR0402-RES"))
    )
    (comp (ref "R701")
      (value "9K09")
      (footprint "eagle-import:0402-RES")
      (fields (field (name "PARTNO") "RMCF0402FT9K09"))
      (libsource (lib "eagle-import") (part "RESISTOR0402-RES"))
    )
    (comp (ref "R702")
      (value "10K")
      (footprint "eagle-import:0402-RES")
      (fields (field (name "PARTNO") "RC0402FR-0710KL"))
      (libsource (lib "eagle-import") (part "RESISTOR0402-RES"))
    )
    (comp (ref "R703")
      (value "100K")
      (footprint "eagle-import:0402-RES")
      (fields (field (name "PARTNO") "RC0402FR-07100KL"))
      (libsource (lib "eagle-import") (part "RESISTOR0402-RES"))
    )
    (comp (ref "R704")
      (value "10K")
      (footprint "eagle-import:0402-RES")
      (fields (field (name "PARTNO") "RC0402FR-0710KL"))
      (libsource (lib "eagle-import") (part "RESISTOR0402-RES"))
    )
    (comp (ref "R705")
      (value "453K")
      (footprint "eagle-import:0402-RES")
      (fields (field (name "PARTNO") "RMCF0402FT453K"))
      (libsource (lib "eagle-import") (part "RESISTOR0402-RES"))
    )
    (comp (ref "R706")
      (value "16K5")
      (footprint "eagle-import:0402-RES")
      (fields (field (name "PARTNO") "RMCF0402FT16K5"))
      (libsource (lib "eagle-import") (part "RESISTOR0402-RES"))
    )
    (comp (ref "R707")
      (value "220R")
      (footprint "eagle-import:0402-RES")
      (fields (field (name "PARTNO") "RC0402FR-07220RL"))
      (libsource (lib "eagle-import") (part "RESISTOR0402-RES"))
    )
    (comp (ref "R708")
      (value "220R")
      (footprint "eagle-import:0402-RES")
      (fields (field (name "PARTNO") "RC0402FR-07220RL"))
      (libsource (lib "eagle-import") (part "RESISTOR0402-RES"))
    )
    (comp (ref "R709")
      (value "220R")
      (footprint "eagle-import:0402-RES")
      (fields (field (name "PARTNO") "RC0402FR-07220RL"))
      (libsource (lib "eagle-import") (part "RESISTOR0402-RES"))
    )
    (comp (ref "R710")
      (value "47R")
      (footprint "eagle-import:0402-RES")
      (fields (field (name "PARTNO") "RC0402JR-0747RL"))
      (libsource (lib "eagle-import") (part "RESISTOR0402-RES"))
    )
    (comp (ref "R711")
      (value "220R")
      (footprint "eagle-import:0402-RES")
      (fields (field (name "PARTNO") "RC0402FR-07220RL"))
      (libsource (lib "eagle-import") (part "RESISTOR0402-RES"))
    )
    (comp (ref "R712")
      (value "220R")
      (footprint "eagle-import:0402-RES")
      (fields (field (name "PARTNO") "RC0402FR-07220RL"))
      (libsource (lib "eagle-import") (part "RESISTOR0402-RES"))
    )
    (comp (ref "R713")
      (value "1K5")
      (footprint "eagle-import:0402-RES")
      (fields (field (name "PARTNO") "RC0402FR-071K5L"))
      (libsource (lib "eagle-import") (part "RESISTOR0402-RES"))
    )
    (comp (ref "U$701")
      (value "PESD0402-140")
      (footprint "eagle-import:0402-TVS")
      (libsource (lib "eagle-import") (part "DIODE-TVS"))
    )
    (comp (ref "U701")
      (value "TCA62724FMG")
      (footprint "eagle-import:SON10")
      (libsource (lib "eagle-import") (part "TCA62724FMG"))
    )
    (comp (ref "U702")
      (value "LT3469")
      (footprint "eagle-import:SOT23-8")
      (fields (field (name "PARTNO") "LT3469ETS8"))
      (libsource (lib "eagle-import") (part "LT3469"))
    )
    (comp (ref "U703")
      (value "LRTB GFTG-T7AW-1+V7A7-29+R5T9-49-L")
      (footprint "eagle-import:6-PLCC")
      (fields (field (name "PARTNO") "LRTB GFTG-T7AW-1+V7A7-29+R5T9-49-L"))
      (libsource (lib "eagle-import") (part "RGB-LED6-PLCC"))
    )
  )
  (nets
    (net (code "1") (name "ACCEL_DRDY") (class "Default")
      (node (ref "U$1") (pin "3") (pinfunction "S_3") (pintype "passive"))
      (node (ref "U$501") (pin "11") (pinfunction "INT1_11") (pintype "bidirectional"))
      (node (ref "U101") (pin "90") (pinfunction "PB4_90") (pintype "bidirectional"))
    )
    (net (code "2") (name "ALARM") (class "Default")
      (node (ref "R701") (pin "P$2") (pinfunction "2_P$2") (pintype "passive"))
      (node (ref "U101") (pin "77") (pinfunction "PA15_77") (pintype "bidirectional"))
    )
    (net (code "3") (name "BATT_CURRENT_SENS") (class "Default")
      (node (ref "R604") (pin "P$1") (pinfunction "1_P$1") (pintype "passive"))
      (node (ref "U101") (pin "26") (pinfunction "PA3_26") (pintype "bidirectional"))
    )
    (net (code "4") (name "BATT_VOLTAGE_SENS") (class "Default")
      (node (ref "R605") (pin "P$1") (pinfunction "1_P$1") (pintype "passive"))
      (node (ref "U101") (pin "25") (pinfunction "PA2_25") (pintype "bidirectional"))
    )
    (net (code "5") (name "CAN1_RX") (class "Default")
      (node (ref "U101") (pin "81") (pinfunction "PD0_81") (pintype "bidirectional"))
      (node (ref "U401") (pin "4") (pinfunction "DOUT_4") (pintype "output"))
    )
    (net (code "6") (name "CAN1_TX") (class "Default")
      (node (ref "U101") (pin "82") (pinfunction "PD1_82") (pintype "bidirectional"))
      (node (ref "U401") (pin "1") (pinfunction "DIN_1") (pintype "input"))
    )
    (net (code "7") (name "CAN2_RX") (class "Default")
      (node (ref "R13") (pin "P$1") (pinfunction "1_P$1") (pintype "passive"))
      (node (ref "U101") (pin "51") (pinfunction "PB12_51") (pintype "bidirectional"))
    )
    (net (code "8") (name "CAN2_TX") (class "Default")
      (node (ref "R12") (pin "P$1") (pinfunction "1_P$1") (pintype "passive"))
      (node (ref "U101") (pin "92") (pinfunction "PB6_92") (pintype "bidirectional"))
    )
    (net (code "9") (name "CAN_H") (class "Default")
      (node (ref "CAN_H") (pin "P$1") (pinfunction "P$1_P$1") (pintype "passive"))
      (node (ref "J405") (pin "P$2") (pinfunction "2_P$2") (pintype "passive"))
      (node (ref "R409") (pin "P$1") (pinfunction "1_P$1") (pintype "passive"))
      (node (ref "U401") (pin "7") (pinfunction "CANH_7") (pintype "bidirectional"))
    )
    (net (code "10") (name "CAN_L") (class "Default")
      (node (ref "CAN_L") (pin "P$1") (pinfunction "P$1_P$1") (pintype "passive"))
      (node (ref "J405") (pin "P$3") (pinfunction "3_P$3") (pintype "passive"))
      (node (ref "R409") (pin "P$2") (pinfunction "2_P$2") (pintype "passive"))
      (node (ref "U401") (pin "6") (pinfunction "CANL_6") (pintype "bidirectional"))
    )
    (net (code "11") (name "FMU-BOOT0") (class "Default")
      (node (ref "FMU-BOOT1101") (pin "P$1") (pinfunction "P$1_P$1") (pintype "passive"))
      (node (ref "R611") (pin "P$2") (pinfunction "2_P$2") (pintype "passive"))
      (node (ref "U101") (pin "94") (pinfunction "BOOT0_94") (pintype "input"))
    )
    (net (code "12") (name "FMU-CH1") (class "Default")
      (node (ref "U101") (pin "45") (pinfunction "PE14_45") (pintype "bidirectional"))
      (node (ref "U901") (pin "7") (pinfunction "A6_7") (pintype "bidirectional"))
    )
    (net (code "13") (name "FMU-CH2") (class "Default")
      (node (ref "U101") (pin "44") (pinfunction "PE13_44") (pintype "bidirectional"))
      (node (ref "U901") (pin "6") (pinfunction "A5_6") (pintype "bidirectional"))
    )
    (net (code "14") (name "FMU-CH3") (class "Default")
      (node (ref "U101") (pin "42") (pinfunction "PE11_42") (pintype "bidirectional"))
      (node (ref "U901") (pin "5") (pinfunction "A4_5") (pintype "bidirectional"))
    )
    (net (code "15") (name "FMU-CH4") (class "Default")
      (node (ref "U101") (pin "40") (pinfunction "PE9_40") (pintype "bidirectional"))
      (node (ref "U901") (pin "4") (pinfunction "A3_4") (pintype "bidirectional"))
    )
    (net (code "16") (name "FMU-CH5") (class "Default")
      (node (ref "U101") (pin "60") (pinfunction "PD13_60") (pintype "bidirectional"))
      (node (ref "U901") (pin "3") (pinfunction "A2_3") (pintype "bidirectional"))
    )
    (net (code "17") (name "FMU-CH6") (class "Default")
      (node (ref "U101") (pin "61") (pinfunction "PD14_61") (pintype "bidirectional"))
      (node (ref "U901") (pin "1") (pinfunction "A1_1") (pintype "bidirectional"))
    )
    (net (code "18") (name "FMU-I2C1_SCL") (class "Default")
      (node (ref "R401") (pin "P$1") (pinfunction "1_P$1") (pintype "passive"))
      (node (ref "R404") (pin "P$1") (pinfunction "1_P$1") (pintype "passive"))
      (node (ref "U101") (pin "95") (pinfunction "PB8_95") (pintype "bidirectional"))
    )
    (net (code "19") (name "FMU-I2C1_SDA") (class "Default")
      (node (ref "R402") (pin "P$1") (pinfunction "1_P$1") (pintype "passive"))
      (node (ref "R405") (pin "P$1") (pinfunction "1_P$1") (pintype "passive"))
      (node (ref "U101") (pin "96") (pinfunction "PB9_96") (pintype "bidirectional"))
    )
    (net (code "20") (name "FMU-I2C2_SCL") (class "Default")
      (node (ref "R306") (pin "P$1") (pinfunction "1_P$1") (pintype "passive"))
      (node (ref "U101") (pin "47") (pinfunction "PB10_47") (pintype "bidirectional"))
      (node (ref "U701") (pin "3") (pinfunction "SCL_3") (pintype "bidirectional"))
    )
    (net (code "21") (name "FMU-I2C2_SDA") (class "Default")
      (node (ref "R307") (pin "P$1") (pinfunction "1_P$1") (pintype "passive"))
      (node (ref "U101") (pin "48") (pinfunction "PB11_48") (pintype "bidirectional"))
      (node (ref "U701") (pin "2") (pinfunction "SDA_2") (pintype "bidirectional"))
    )
    (net (code "22") (name "FMU-SWCLK") (class "Default")
      (node (ref "JX301") (pin "4") (pinfunction "S_4") (pintype "passive"))
      (node (ref "U101") (pin "76") (pinfunction "PA14_76") (pintype "bidirectional"))
    )
    (net (code "23") (name "FMU-SWDIO") (class "Default")
      (node (ref "JX301") (pin "2") (pinfunction "S_2") (pintype "passive"))
      (node (ref "U101") (pin "72") (pinfunction "PA13_72") (pintype "bidirectional"))
    )
    (net (code "24") (name "FMU-SWO") (class "Default")
      (node (ref "JX301") (pin "6") (pinfunction "S_6") (pintype "passive"))
      (node (ref "U101") (pin "89") (pinfunction "PB3_89") (pintype "bidirectional"))
    )
    (net (code "25") (name "FMU-UART4_RX") (class "Default")
      (node (ref "U101") (pin "24") (pinfunction "PA1_24") (pintype "bidirectional"))
      (node (ref "U202") (pin "8") (pinfunction "A7_8") (pintype "bidirectional"))
    )
    (net (code "26") (name "FMU-UART4_TX") (class "Default")
      (node (ref "U101") (pin "23") (pinfunction "PA0_23") (pintype "bidirectional"))
      (node (ref "U202") (pin "9") (pinfunction "A8_9") (pintype "bidirectional"))
    )
    (net (code "27") (name "FMU-UART7_RX") (class "Default")
      (node (ref "U101") (pin "38") (pinfunction "PE7_38") (pintype "bidirectional"))
      (node (ref "U202") (pin "4") (pinfunction "A3_4") (pintype "bidirectional"))
    )
    (net (code "28") (name "FMU-UART7_TX") (class "Default")
      (node (ref "U101") (pin "39") (pinfunction "PE8_39") (pintype "bidirectional"))
      (node (ref "U202") (pin "5") (pinfunction "A4_5") (pintype "bidirectional"))
    )
    (net (code "29") (name "FMU-UART8_RX") (class "Default")
      (node (ref "U101") (pin "97") (pinfunction "PE0_97") (pintype "bidirectional"))
      (node (ref "U202") (pin "6") (pinfunction "A5_6") (pintype "bidirectional"))
    )
    (net (code "30") (name "FMU-UART8_TX") (class "Default")
      (node (ref "U101") (pin "98") (pinfunction "PE1_98") (pintype "bidirectional"))
      (node (ref "U202") (pin "7") (pinfunction "A6_7") (pintype "bidirectional"))
    )
    (net (code "31") (name "FMU-USART2_CTS") (class "Default")
      (node (ref "U101") (pin "84") (pinfunction "PD3_84") (pintype "bidirectional"))
      (node (ref "U201") (pin "9") (pinfunction "A8_9") (pintype "bidirectional"))
    )
    (net (code "32") (name "FMU-USART2_RTS") (class "Default")
      (node (ref "U101") (pin "85") (pinfunction "PD4_85") (pintype "bidirectional"))
      (node (ref "U201") (pin "8") (pinfunction "A7_8") (pintype "bidirectional"))
    )
    (net (code "33") (name "FMU-USART2_RX") (class "Default")
      (node (ref "U101") (pin "87") (pinfunction "PD6_87") (pintype "bidirectional"))
      (node (ref "U201") (pin "6") (pinfunction "A5_6") (pintype "bidirectional"))
    )
    (net (code "34") (name "FMU-USART2_TX") (class "Default")
      (node (ref "U101") (pin "86") (pinfunction "PD5_86") (pintype "bidirectional"))
      (node (ref "U201") (pin "7") (pinfunction "A6_7") (pintype "bidirectional"))
    )
    (net (code "35") (name "FMU-USART3_CTS") (class "Default")
      (node (ref "U101") (pin "58") (pinfunction "PD11_58") (pintype "bidirectional"))
      (node (ref "U201") (pin "3") (pinfunction "A2_3") (pintype "bidirectional"))
    )
    (net (code "36") (name "FMU-USART3_RTS") (class "Default")
      (node (ref "U101") (pin "59") (pinfunction "PD12_59") (pintype "bidirectional"))
      (node (ref "U201") (pin "1") (pinfunction "A1_1") (pintype "bidirectional"))
    )
    (net (code "37") (name "FMU-USART3_RX") (class "Default")
      (node (ref "U101") (pin "56") (pinfunction "PD9_56") (pintype "bidirectional"))
      (node (ref "U201") (pin "4") (pinfunction "A3_4") (pintype "bidirectional"))
    )
    (net (code "38") (name "FMU-USART3_TX") (class "Default")
      (node (ref "U101") (pin "55") (pinfunction "PD8_55") (pintype "bidirectional"))
      (node (ref "U201") (pin "5") (pinfunction "A4_5") (pintype "bidirectional"))
    )
    (net (code "39") (name "FMU-VDD_3V3") (class "Default")
      (node (ref "C101") (pin "P$1") (pinfunction "1_P$1") (pintype "passive"))
      (node (ref "C201") (pin "P$1") (pinfunction "1_P$1") (pintype "passive"))
      (node (ref "C202") (pin "P$1") (pinfunction "1_P$1") (pintype "passive"))
      (node (ref "C402") (pin "P$1") (pinfunction "1_P$1") (pintype "passive"))
      (node (ref "C603") (pin "P$1") (pinfunction "1_P$1") (pintype "passive"))
      (node (ref "C604") (pin "P$1") (pinfunction "1_P$1") (pintype "passive"))
      (node (ref "C606") (pin "P$1") (pinfunction "1_P$1") (pintype "passive"))
      (node (ref "C607") (pin "P$1") (pinfunction "1_P$1") (pintype "passive"))
      (node (ref "C608") (pin "P$1") (pinfunction "1_P$1") (pintype "passive"))
      (node (ref "C610") (pin "P$1") (pinfunction "1_P$1") (pintype "passive"))
      (node (ref "C612") (pin "P$1") (pinfunction "1_P$1") (pintype "passive"))
      (node (ref "C701") (pin "P$1") (pinfunction "1_P$1") (pintype "passive"))
      (node (ref "C902") (pin "P$1") (pinfunction "1_P$1") (pintype "passive"))
      (node (ref "JX301") (pin "1") (pinfunction "S_1") (pintype "passive"))
      (node (ref "R301") (pin "P$2") (pinfunction "2_P$2") (pintype "passive"))
      (node (ref "R302") (pin "P$2") (pinfunction "2_P$2") (pintype "passive"))
      (node (ref "R303") (pin "P$2") (pinfunction "2_P$2") (pintype "passive"))
      (node (ref "R304") (pin "P$2") (pinfunction "2_P$2") (pintype "passive"))
      (node (ref "R305") (pin "P$2") (pinfunction "2_P$2") (pintype "passive"))
      (node (ref "R306") (pin "P$2") (pinfunction "2_P$2") (pintype "passive"))
      (node (ref "R307") (pin "P$2") (pinfunction "2_P$2") (pintype "passive"))
      (node (ref "R401") (pin "P$2") (pinfunction "2_P$2") (pintype "passive"))
      (node (ref "R402") (pin "P$2") (pinfunction "2_P$2") (pintype "passive"))
      (node (ref "R608") (pin "P$2") (pinfunction "2_P$2") (pintype "passive"))
      (node (ref "U$605") (pin "7") (pinfunction "VOUT2_7") (pintype "bidirectional"))
      (node (ref "U101") (pin "100") (pinfunction "VDD_100") (pintype "power_in"))
      (node (ref "U101") (pin "11") (pinfunction "VDD_11") (pintype "power_in"))
      (node (ref "U101") (pin "19") (pinfunction "VDD_19") (pintype "power_in"))
      (node (ref "U101") (pin "21") (pinfunction "VREF+_21") (pintype "input"))
      (node (ref "U101") (pin "22") (pinfunction "VDDA_22") (pintype "power_in"))
      (node (ref "U101") (pin "28") (pinfunction "VDD_28") (pintype "power_in"))
      (node (ref "U101") (pin "50") (pinfunction "VDD_50") (pintype "power_in"))
      (node (ref "U101") (pin "75") (pinfunction "VDD_75") (pintype "power_in"))
      (node (ref "U102") (pin "3") (pinfunction "~{W}_3") (pintype "bidirectional"))
      (node (ref "U102") (pin "7") (pinfunction "~{HOLD}_7") (pintype "bidirectional"))
      (node (ref "U102") (pin "8") (pinfunction "VDD_8") (pintype "bidirectional"))
      (node (ref "U201") (pin "10") (pinfunction "OE_10") (pintype "input"))
      (node (ref "U201") (pin "19") (pinfunction "VCCB_19") (pintype "input"))
      (node (ref "U201") (pin "2") (pinfunction "VCCA_2") (pintype "input"))
      (node (ref "U202") (pin "10") (pinfunction "OE_10") (pintype "input"))
      (node (ref "U202") (pin "19") (pinfunction "VCCB_19") (pintype "input"))
      (node (ref "U202") (pin "2") (pinfunction "VCCA_2") (pintype "input"))
      (node (ref "U301") (pin "4") (pinfunction "VCC_4") (pintype "passive"))
      (node (ref "U401") (pin "3") (pinfunction "VCC_3") (pintype "input"))
      (node (ref "U701") (pin "1") (pinfunction "~{SHDN}_1") (pintype "input"))
      (node (ref "U701") (pin "10") (pinfunction "VIN_10") (pintype "power_in"))
      (node (ref "U901") (pin "10") (pinfunction "OE_10") (pintype "input"))
      (node (ref "U901") (pin "19") (pinfunction "VCCB_19") (pintype "input"))
      (node (ref "U901") (pin "2") (pinfunction "VCCA_2") (pintype "input"))
      (node (ref "VDD_3V1101") (pin "P$1") (pinfunction "P$1_P$1") (pintype "passive"))
    )
    (net (code "40") (name "FMU-~{RESET}") (class "Default")
      (node (ref "C609") (pin "P$2") (pinfunction "2_P$2") (pintype "passive"))
      (node (ref "S601") (pin "A1") (pinfunction "1_A1") (pintype "passive"))
      (node (ref "U$605") (pin "3") (pinfunction "POR2_3") (pintype "bidirectional"))
      (node (ref "U101") (pin "14") (pinfunction "NRST_14") (pintype "input"))
      (node (ref "U701") (pin "4") (pinfunction "~{RESET}_4") (pintype "input"))
    )
    (net (code "41") (name "FMU_AUX_ADC1") (class "Default")
      (node (ref "R408") (pin "P$1") (pinfunction "1_P$1") (pintype "passive"))
      (node (ref "U101") (pin "18") (pinfunction "PC3_18") (pintype "bidirectional"))
    )
    (net (code "42") (name "FMU_AUX_ADC2") (class "Default")
      (node (ref "R407") (pin "P$1") (pinfunction "1_P$1") (pintype "passive"))
      (node (ref "U101") (pin "33") (pinfunction "PC4_33") (pintype "bidirectional"))
    )
    (net (code "43") (name "FRAM_MISO") (class "Default")
      (node (ref "U101") (pin "53") (pinfunction "PB14_53") (pintype "bidirectional"))
      (node (ref "U102") (pin "2") (pinfunction "Q_2") (pintype "bidirectional"))
    )
    (net (code "44") (name "FRAM_MOSI") (class "Default")
      (node (ref "U101") (pin "54") (pinfunction "PB15_54") (pintype "bidirectional"))
      (node (ref "U102") (pin "5") (pinfunction "D_5") (pintype "bidirectional"))
    )
    (net (code "45") (name "FRAM_SCK") (class "Default")
      (node (ref "U101") (pin "52") (pinfunction "PB13_52") (pintype "bidirectional"))
      (node (ref "U102") (pin "6") (pinfunction "C_6") (pintype "bidirectional"))
    )
    (net (code "46") (name "GND") (class "Default")
      (node (ref "B601") (pin "2") (pinfunction "NEG_2") (pintype "bidirectional"))
      (node (ref "C1001") (pin "P$2") (pinfunction "2_P$2") (pintype "passive"))
      (node (ref "C1002") (pin "P$2") (pinfunction "2_P$2") (pintype "passive"))
      (node (ref "C1003") (pin "P$2") (pinfunction "2_P$2") (pintype "passive"))
      (node (ref "C1004") (pin "P$2") (pinfunction "2_P$2") (pintype "passive"))
      (node (ref "C101") (pin "P$2") (pinfunction "2_P$2") (pintype "passive"))
      (node (ref "C102") (pin "P$2") (pinfunction "2_P$2") (pintype "passive"))
      (node (ref "C103") (pin "P$1") (pinfunction "1_P$1") (pintype "passive"))
      (node (ref "C201") (pin "P$2") (pinfunction "2_P$2") (pintype "passive"))
      (node (ref "C202") (pin "P$2") (pinfunction "2_P$2") (pintype "passive"))
      (node (ref "C401") (pin "P$2") (pinfunction "2_P$2") (pintype "passive"))
      (node (ref "C402") (pin "P$2") (pinfunction "2_P$2") (pintype "passive"))
      (node (ref "C501") (pin "P$2") (pinfunction "2_P$2") (pintype "passive"))
      (node (ref "C502") (pin "P$2") (pinfunction "2_P$2") (pintype "passive"))
      (node (ref "C503") (pin "P$2") (pinfunction "2_P$2") (pintype "passive"))
      (node (ref "C504") (pin "P$2") (pinfunction "2_P$2") (pintype "passive"))
      (node (ref "C505") (pin "P$2") (pinfunction "2_P$2") (pintype "passive"))
      (node (ref "C506") (pin "P$2") (pinfunction "2_P$2") (pintype "passive"))
      (node (ref "C507") (pin "P$2") (pinfunction "2_P$2") (pintype "passive"))
      (node (ref "C508") (pin "P$2") (pinfunction "2_P$2") (pintype "passive"))
      (node (ref "C509") (pin "P$2") (pinfunction "2_P$2") (pintype "passive"))
      (node (ref "C601") (pin "P$2") (pinfunction "2_P$2") (pintype "passive"))
      (node (ref "C602") (pin "P$1") (pinfunction "1_P$1") (pintype "passive"))
      (node (ref "C603") (pin "P$2") (pinfunction "2_P$2") (pintype "passive"))
      (node (ref "C604") (pin "P$2") (pinfunction "2_P$2") (pintype "passive"))
      (node (ref "C605") (pin "P$2") (pinfunction "2_P$2") (pintype "passive"))
      (node (ref "C606") (pin "P$2") (pinfunction "2_P$2") (pintype "passive"))
      (node (ref "C607") (pin "P$2") (pinfunction "2_P$2") (pintype "passive"))
      (node (ref "C608") (pin "P$2") (pinfunction "2_P$2") (pintype "passive"))
      (node (ref "C609") (pin "P$1") (pinfunction "1_P$1") (pintype "passive"))
      (node (ref "C610") (pin "P$2") (pinfunction "2_P$2") (pintype "passive"))
      (node (ref "C611") (pin "P$2") (pinfunction "2_P$2") (pintype "passive"))
      (node (ref "C612") (pin "P$2") (pinfunction "2_P$2") (pintype "passive"))
      (node (ref "C613") (pin "P$2") (pinfunction "2_P$2") (pintype "passive"))
      (node (ref "C701") (pin "P$2") (pinfunction "2_P$2") (pintype "passive"))
      (node (ref "C702") (pin "P$2") (pinfunction "2_P$2") (pintype "passive"))
      (node (ref "C703") (pin "P$2") (pinfunction "2_P$2") (pintype "passive"))
      (node (ref "C704") (pin "P$2") (pinfunction "2_P$2") (pintype "passive"))
      (node (ref "C801") (pin "P$1") (pinfunction "1_P$1") (pintype "passive"))
      (node (ref "C802") (pin "P$2") (pinfunction "2_P$2") (pintype "passive"))
      (node (ref "C803") (pin "P$2") (pinfunction "2_P$2") (pintype "passive"))
      (node (ref "C804") (pin "P$2") (pinfunction "2_P$2") (pintype "passive"))
      (node (ref "C805") (pin "P$2") (pinfunction "2_P$2") (pintype "passive"))
      (node (ref "C806") (pin "P$1") (pinfunction "1_P$1") (pintype "passive"))
      (node (ref "C901") (pin "P$2") (pinfunction "2_P$2") (pintype "passive"))
      (node (ref "C902") (pin "P$2") (pinfunction "2_P$2") (pintype "passive"))
      (node (ref "C903") (pin "P$2") (pinfunction "2_P$2") (pintype "passive"))
      (node (ref "GND") (pin "P$1") (pinfunction "P$1_P$1") (pintype "passive"))
      (node (ref "GND.") (pin "P$1") (pinfunction "P$1_P$1") (pintype "passive"))
      (node (ref "J201") (pin "P$6") (pinfunction "6_P$6") (pintype "passive"))
      (node (ref "J202") (pin "P$6") (pinfunction "6_P$6") (pintype "passive"))
      (node (ref "J203") (pin "P$6") (pinfunction "6_P$6") (pintype "passive"))
      (node (ref "J204") (pin "P$6") (pinfunction "6_P$6") (pintype "passive"))
      (node (ref "J301") (pin "GND") (pinfunction "5_GND") (pintype "power_in"))
      (node (ref "J301") (pin "GND1") (pinfunction "GND1_GND1") (pintype "bidirectional"))
      (node (ref "J301") (pin "GND2") (pinfunction "GND2_GND2") (pintype "bidirectional"))
      (node (ref "J301") (pin "GND3") (pinfunction "GND3_GND3") (pintype "bidirectional"))
      (node (ref "J301") (pin "GND4") (pinfunction "GND4_GND4") (pintype "bidirectional"))
      (node (ref "J302") (pin "P$4") (pinfunction "4_P$4") (pintype "passive"))
      (node (ref "J401") (pin "P$4") (pinfunction "4_P$4") (pintype "passive"))
      (node (ref "J402") (pin "P$3") (pinfunction "3_P$3") (pintype "passive"))
      (node (ref "J403") (pin "P$7") (pinfunction "7_P$7") (pintype "passive"))
      (node (ref "J404") (pin "P$3") (pinfunction "3_P$3") (pintype "passive"))
      (node (ref "J404") (pin "P$5") (pinfunction "5_P$5") (pintype "passive"))
      (node (ref "J405") (pin "P$4") (pinfunction "4_P$4") (pintype "passive"))
      (node (ref "J601") (pin "P$5") (pinfunction "5_P$5") (pintype "passive"))
      (node (ref "J601") (pin "P$6") (pinfunction "6_P$6") (pintype "passive"))
      (node (ref "J701") (pin "P$2") (pinfunction "2_P$2") (pintype "passive"))
      (node (ref "J801") (pin "P$2") (pinfunction "P$2_P$2") (pintype "bidirectional"))
      (node (ref "J901") (pin "12") (pinfunction "S_12") (pintype "passive"))
      (node (ref "J901") (pin "15") (pinfunction "S_15") (pintype "passive"))
      (node (ref "J901") (pin "18") (pinfunction "S_18") (pintype "passive"))
      (node (ref "J901") (pin "21") (pinfunction "S_21") (pintype "passive"))
      (node (ref "J901") (pin "24") (pinfunction "S_24") (pintype "passive"))
      (node (ref "J901") (pin "27") (pinfunction "S_27") (pintype "passive"))
      (node (ref "J901") (pin "3") (pinfunction "S_3") (pintype "passive"))
      (node (ref "J901") (pin "30") (pinfunction "S_30") (pintype "passive"))
      (node (ref "J901") (pin "33") (pinfunction "S_33") (pintype "passive"))
      (node (ref "J901") (pin "36") (pinfunction "S_36") (pintype "passive"))
      (node (ref "J901") (pin "39") (pinfunction "S_39") (pintype "passive"))
      (node (ref "J901") (pin "42") (pinfunction "S_42") (pintype "passive"))
      (node (ref "J901") (pin "45") (pinfunction "S_45") (pintype "passive"))
      (node (ref "J901") (pin "48") (pinfunction "S_48") (pintype "passive"))
      (node (ref "J901") (pin "6") (pinfunction "S_6") (pintype "passive"))
      (node (ref "J901") (pin "9") (pinfunction "S_9") (pintype "passive"))
      (node (ref "JX301") (pin "3") (pinfunction "S_3") (pintype "passive"))
      (node (ref "JX301") (pin "5") (pinfunction "S_5") (pintype "passive"))
      (node (ref "JX301") (pin "9") (pinfunction "S_9") (pintype "passive"))
      (node (ref "JX801") (pin "3") (pinfunction "GND_3") (pintype "bidirectional"))
      (node (ref "JX802") (pin "3") (pinfunction "S_3") (pintype "passive"))
      (node (ref "JX802") (pin "5") (pinfunction "S_5") (pintype "passive"))
      (node (ref "JX802") (pin "9") (pinfunction "S_9") (pintype "passive"))
      (node (ref "L201") (pin "P$3") (pinfunction "P$3_P$3") (pintype "bidirectional"))
      (node (ref "L201") (pin "P$4") (pinfunction "P$3_P$4") (pintype "bidirectional"))
      (node (ref "L201") (pin "P$5") (pinfunction "P$3_P$5") (pintype "bidirectional"))
      (node (ref "L202") (pin "P$3") (pinfunction "P$3_P$3") (pintype "bidirectional"))
      (node (ref "L202") (pin "P$4") (pinfunction "P$3_P$4") (pintype "bidirectional"))
      (node (ref "L202") (pin "P$5") (pinfunction "P$3_P$5") (pintype "bidirectional"))
      (node (ref "L203") (pin "P$3") (pinfunction "P$3_P$3") (pintype "bidirectional"))
      (node (ref "L203") (pin "P$4") (pinfunction "P$3_P$4") (pintype "bidirectional"))
      (node (ref "L203") (pin "P$5") (pinfunction "P$3_P$5") (pintype "bidirectional"))
      (node (ref "L401") (pin "P$3") (pinfunction "P$3_P$3") (pintype "bidirectional"))
      (node (ref "L401") (pin "P$4") (pinfunction "P$3_P$4") (pintype "bidirectional"))
      (node (ref "L401") (pin "P$5") (pinfunction "P$3_P$5") (pintype "bidirectional"))
      (node (ref "L402") (pin "P$3") (pinfunction "P$3_P$3") (pintype "bidirectional"))
      (node (ref "L402") (pin "P$4") (pinfunction "P$3_P$4") (pintype "bidirectional"))
      (node (ref "L402") (pin "P$5") (pinfunction "P$3_P$5") (pintype "bidirectional"))
      (node (ref "L403") (pin "P$3") (pinfunction "P$3_P$3") (pintype "bidirectional"))
      (node (ref "L403") (pin "P$4") (pinfunction "P$3_P$4") (pintype "bidirectional"))
      (node (ref "L403") (pin "P$5") (pinfunction "P$3_P$5") (pintype "bidirectional"))
      (node (ref "L404") (pin "P$3") (pinfunction "P$3_P$3") (pintype "bidirectional"))
      (node (ref "L404") (pin "P$4") (pinfunction "P$3_P$4") (pintype "bidirectional"))
      (node (ref "L404") (pin "P$5") (pinfunction "P$3_P$5") (pintype "bidirectional"))
      (node (ref "L601") (pin "P$3") (pinfunction "P$3_P$3") (pintype "bidirectional"))
      (node (ref "L601") (pin "P$4") (pinfunction "P$3_P$4") (pintype "bidirectional"))
      (node (ref "L601") (pin "P$5") (pinfunction "P$3_P$5") (pintype "bidirectional"))
      (node (ref "L602") (pin "P$3") (pinfunction "P$3_P$3") (pintype "bidirectional"))
      (node (ref "L602") (pin "P$4") (pinfunction "P$3_P$4") (pintype "bidirectional"))
      (node (ref "L602") (pin "P$5") (pinfunction "P$3_P$5") (pintype "bidirectional"))
      (node (ref "L603") (pin "P$3") (pinfunction "P$3_P$3") (pintype "bidirectional"))
      (node (ref "L603") (pin "P$4") (pinfunction "P$3_P$4") (pintype "bidirectional"))
      (node (ref "L603") (pin "P$5") (pinfunction "P$3_P$5") (pintype "bidirectional"))
      (node (ref "L901") (pin "P$3") (pinfunction "P$3_P$3") (pintype "bidirectional"))
      (node (ref "L901") (pin "P$4") (pinfunction "P$3_P$4") (pintype "bidirectional"))
      (node (ref "L901") (pin "P$5") (pinfunction "P$3_P$5") (pintype "bidirectional"))
      (node (ref "R1001") (pin "P$1") (pinfunction "1_P$1") (pintype "passive"))
      (node (ref "R1002") (pin "P$1") (pinfunction "1_P$1") (pintype "passive"))
      (node (ref "R102") (pin "P$2") (pinfunction "2_P$2") (pintype "passive"))
      (node (ref "R11") (pin "P$2") (pinfunction "2_P$2") (pintype "passive"))
      (node (ref "R403") (pin "P$1") (pinfunction "1_P$1") (pintype "passive"))
      (node (ref "R5") (pin "P$2") (pinfunction "2_P$2") (pintype "passive"))
      (node (ref "R602") (pin "P$2") (pinfunction "2_P$2") (pintype "passive"))
      (node (ref "R606") (pin "P$2") (pinfunction "2_P$2") (pintype "passive"))
      (node (ref "R607") (pin "P$2") (pinfunction "2_P$2") (pintype "passive"))
      (node (ref "R610") (pin "P$2") (pinfunction "2_P$2") (pintype "passive"))
      (node (ref "R611") (pin "P$1") (pinfunction "1_P$1") (pintype "passive"))
      (node (ref "R702") (pin "P$2") (pinfunction "2_P$2") (pintype "passive"))
      (node (ref "R704") (pin "P$1") (pinfunction "1_P$1") (pintype "passive"))
      (node (ref "R706") (pin "P$2") (pinfunction "2_P$2") (pintype "passive"))
      (node (ref "R708") (pin "P$1") (pinfunction "1_P$1") (pintype "passive"))
      (node (ref "R711") (pin "P$1") (pinfunction "1_P$1") (pintype "passive"))
      (node (ref "R713") (pin "P$2") (pinfunction "2_P$2") (pintype "passive"))
      (node (ref "R8") (pin "P$2") (pinfunction "2_P$2") (pintype "passive"))
      (node (ref "R801") (pin "P$2") (pinfunction "2_P$2") (pintype "passive"))
      (node (ref "R802") (pin "P$2") (pinfunction "2_P$2") (pintype "passive"))
      (node (ref "R919") (pin "P$1") (pinfunction "1_P$1") (pintype "passive"))
      (node (ref "S601") (pin "B3") (pinfunction "2_B3") (pintype "passive"))
      (node (ref "S801") (pin "B3") (pinfunction "2_B3") (pintype "passive"))
      (node (ref "U$1") (pin "2") (pinfunction "S_2") (pintype "passive"))
      (node (ref "U$1001") (pin "2") (pinfunction "VSS_2") (pintype "bidirectional"))
      (node (ref "U$1001") (pin "5") (pinfunction "~{CE}_5") (pintype "bidirectional"))
      (node (ref "U$1001") (pin "6") (pinfunction "VBAT_6") (pintype "bidirectional"))
      (node (ref "U$1001") (pin "GND") (pinfunction "VSS_GND") (pintype "bidirectional"))
      (node (ref "U$1001") (pin "P$2") (pinfunction "VSS_P$2") (pintype "bidirectional"))
      (node (ref "U$1001") (pin "P$3") (pinfunction "VSS_P$3") (pintype "bidirectional"))
      (node (ref "U$1002") (pin "2") (pinfunction "GND_2") (pintype "bidirectional"))
      (node (ref "U$1002") (pin "GND") (pinfunction "GND_GND") (pintype "bidirectional"))
      (node (ref "U$2") (pin "P$10") (pinfunction "GND_P$10") (pintype "bidirectional"))
      (node (ref "U$2") (pin "P$24") (pinfunction "HYS_P$24") (pintype "bidirectional"))
      (node (ref "U$2") (pin "P$25") (pinfunction "GND_P$25") (pintype "bidirectional"))
      (node (ref "U$201") (pin "A") (pinfunction "A_A") (pintype "passive"))
      (node (ref "U$202") (pin "A") (pinfunction "A_A") (pintype "passive"))
      (node (ref "U$203") (pin "A") (pinfunction "A_A") (pintype "passive"))
      (node (ref "U$301") (pin "2") (pinfunction "GND_2") (pintype "bidirectional"))
      (node (ref "U$401") (pin "A") (pinfunction "A_A") (pintype "passive"))
      (node (ref "U$402") (pin "A") (pinfunction "A_A") (pintype "passive"))
      (node (ref "U$403") (pin "A") (pinfunction "A_A") (pintype "passive"))
      (node (ref "U$404") (pin "A") (pinfunction "A_A") (pintype "passive"))
      (node (ref "U$501") (pin "10") (pinfunction "RSRV_10") (pintype "bidirectional"))
      (node (ref "U$501") (pin "12") (pinfunction "GND_12") (pintype "bidirectional"))
      (node (ref "U$501") (pin "13") (pinfunction "GND_13") (pintype "bidirectional"))
      (node (ref "U$501") (pin "16") (pinfunction "GND_16") (pintype "bidirectional"))
      (node (ref "U$501") (pin "5") (pinfunction "GND_5") (pintype "bidirectional"))
      (node (ref "U$6") (pin "A") (pinfunction "A_A") (pintype "passive"))
      (node (ref "U$602") (pin "2") (pinfunction "VSS_2") (pintype "bidirectional"))
      (node (ref "U$602") (pin "6") (pinfunction "VBAT_6") (pintype "bidirectional"))
      (node (ref "U$602") (pin "GND") (pinfunction "VSS_GND") (pintype "bidirectional"))
      (node (ref "U$602") (pin "P$2") (pinfunction "VSS_P$2") (pintype "bidirectional"))
      (node (ref "U$602") (pin "P$3") (pinfunction "VSS_P$3") (pintype "bidirectional"))
      (node (ref "U$604") (pin "2") (pinfunction "VSS_2") (pintype "bidirectional"))
      (node (ref "U$604") (pin "6") (pinfunction "VBAT_6") (pintype "bidirectional"))
      (node (ref "U$604") (pin "GND") (pinfunction "VSS_GND") (pintype "bidirectional"))
      (node (ref "U$604") (pin "P$2") (pinfunction "VSS_P$2") (pintype "bidirectional"))
      (node (ref "U$604") (pin "P$3") (pinfunction "VSS_P$3") (pintype "bidirectional"))
      (node (ref "U$605") (pin "2") (pinfunction "GND_2") (pintype "bidirectional"))
      (node (ref "U$605") (pin "GND") (pinfunction "GND_GND") (pintype "bidirectional"))
      (node (ref "U$701") (pin "A") (pinfunction "A_A") (pintype "passive"))
      (node (ref "U$801") (pin "A") (pinfunction "A_A") (pintype "passive"))
      (node (ref "U$901") (pin "A") (pinfunction "A_A") (pintype "passive"))
      (node (ref "U$902") (pin "A") (pinfunction "A_A") (pintype "passive"))
      (node (ref "U101") (pin "10") (pinfunction "VSS_10") (pintype "power_in"))
      (node (ref "U101") (pin "20") (pinfunction "VSSA_20") (pintype "power_in"))
      (node (ref "U101") (pin "27") (pinfunction "VSS_27") (pintype "power_in"))
      (node (ref "U101") (pin "74") (pinfunction "VSS_74") (pintype "power_in"))
      (node (ref "U101") (pin "99") (pinfunction "VSS_99") (pintype "power_in"))
      (node (ref "U102") (pin "4") (pinfunction "VSS_4") (pintype "bidirectional"))
      (node (ref "U201") (pin "11") (pinfunction "GND_11") (pintype "power_in"))
      (node (ref "U202") (pin "11") (pinfunction "GND_11") (pintype "power_in"))
      (node (ref "U301") (pin "6") (pinfunction "GND_6") (pintype "power_in"))
      (node (ref "U401") (pin "2") (pinfunction "GND_2") (pintype "power_in"))
      (node (ref "U401") (pin "5") (pinfunction "SHDN_5") (pintype "input"))
      (node (ref "U401") (pin "8") (pinfunction "RS_8") (pintype "input"))
      (node (ref "U501") (pin "10") (pinfunction "RES_P10_GND_10") (pintype "bidirectional"))
      (node (ref "U501") (pin "11") (pinfunction "RES_P11_GND_11") (pintype "bidirectional"))
      (node (ref "U501") (pin "12") (pinfunction "RES_P12_GND_12") (pintype "bidirectional"))
      (node (ref "U501") (pin "13") (pinfunction "GND_13") (pintype "bidirectional"))
      (node (ref "U501") (pin "8") (pinfunction "RES_P8_GND_8") (pintype "bidirectional"))
      (node (ref "U501") (pin "9") (pinfunction "RES_P9_GND_9") (pintype "bidirectional"))
      (node (ref "U502") (pin "10") (pinfunction "GND_10") (pintype "bidirectional"))
      (node (ref "U502") (pin "11") (pinfunction "GND_11") (pintype "bidirectional"))
      (node (ref "U502") (pin "12") (pinfunction "GND_12") (pintype "bidirectional"))
      (node (ref "U502") (pin "13") (pinfunction "GND_13") (pintype "bidirectional"))
      (node (ref "U502") (pin "9") (pinfunction "GND_9") (pintype "bidirectional"))
      (node (ref "U503") (pin "2") (pinfunction "PS_2") (pintype "bidirectional"))
      (node (ref "U503") (pin "3") (pinfunction "GND_3") (pintype "bidirectional"))
      (node (ref "U701") (pin "5") (pinfunction "GND_5") (pintype "power_in"))
      (node (ref "U702") (pin "4") (pinfunction "GND_4") (pintype "power_in"))
      (node (ref "U801") (pin "23") (pinfunction "VSS_1_23") (pintype "power_in"))
      (node (ref "U801") (pin "35") (pinfunction "VSS_2_35") (pintype "power_in"))
      (node (ref "U801") (pin "47") (pinfunction "VSS_3_47") (pintype "power_in"))
      (node (ref "U801") (pin "8") (pinfunction "VSSA_8") (pintype "power_in"))
      (node (ref "U901") (pin "11") (pinfunction "GND_11") (pintype "power_in"))
      (node (ref "U902") (pin "11") (pinfunction "GND_11") (pintype "power_in"))
      (node (ref "U903") (pin "1") (pinfunction "~{1OE}_1") (pintype "input"))
      (node (ref "U903") (pin "4") (pinfunction "GND_4") (pintype "power_in"))
      (node (ref "X101") (pin "2") (pinfunction "NC_2_2") (pintype "power_in"))
      (node (ref "X101") (pin "4") (pinfunction "NC_4_4") (pintype "power_in"))
      (node (ref "X801") (pin "2") (pinfunction "NC_2_2") (pintype "power_in"))
      (node (ref "X801") (pin "4") (pinfunction "NC_4_4") (pintype "power_in"))
    )
    (net (code "47") (name "GPIO_EXT_1") (class "Default")
      (node (ref "J403") (pin "P$6") (pinfunction "6_P$6") (pintype "passive"))
      (node (ref "U101") (pin "8") (pinfunction "PC14_8") (pintype "bidirectional"))
    )
    (net (code "48") (name "GYRO_DRDY") (class "Default")
      (node (ref "U$1") (pin "5") (pinfunction "S_5") (pintype "passive"))
      (node (ref "U101") (pin "35") (pinfunction "PB0_35") (pintype "bidirectional"))
      (node (ref "U501") (pin "6") (pinfunction "DRDY/INT2_6") (pintype "output"))
      (node (ref "U502") (pin "6") (pinfunction "DRDY/INT2_6") (pintype "bidirectional"))
    )
    (net (code "49") (name "IO-BOOT0") (class "Default")
      (node (ref "IO-BOOT1101") (pin "P$1") (pinfunction "P$1_P$1") (pintype "passive"))
      (node (ref "R801") (pin "P$1") (pinfunction "1_P$1") (pintype "passive"))
      (node (ref "U801") (pin "44") (pinfunction "BOOT0_44") (pintype "input"))
    )
    (net (code "50") (name "IO-CH1") (class "Default")
      (node (ref "U801") (pin "10") (pinfunction "PA0_10") (pintype "bidirectional"))
      (node (ref "U902") (pin "9") (pinfunction "A8_9") (pintype "bidirectional"))
    )
    (net (code "51") (name "IO-CH2") (class "Default")
      (node (ref "U801") (pin "11") (pinfunction "PA1_11") (pintype "bidirectional"))
      (node (ref "U902") (pin "8") (pinfunction "A7_8") (pintype "bidirectional"))
    )
    (net (code "52") (name "IO-CH3") (class "Default")
      (node (ref "U801") (pin "45") (pinfunction "PB8_45") (pintype "bidirectional"))
      (node (ref "U902") (pin "7") (pinfunction "A6_7") (pintype "bidirectional"))
    )
    (net (code "53") (name "IO-CH4") (class "Default")
      (node (ref "U801") (pin "46") (pinfunction "PB9_46") (pintype "bidirectional"))
      (node (ref "U902") (pin "6") (pinfunction "A5_6") (pintype "bidirectional"))
    )
    (net (code "54") (name "IO-CH5") (class "Default")
      (node (ref "U801") (pin "16") (pinfunction "PA6_16") (pintype "bidirectional"))
      (node (ref "U902") (pin "5") (pinfunction "A4_5") (pintype "bidirectional"))
    )
    (net (code "55") (name "IO-CH6") (class "Default")
      (node (ref "U801") (pin "17") (pinfunction "PA7_17") (pintype "bidirectional"))
      (node (ref "U902") (pin "4") (pinfunction "A3_4") (pintype "bidirectional"))
    )
    (net (code "56") (name "IO-CH7") (class "Default")
      (node (ref "U801") (pin "18") (pinfunction "PB0_18") (pintype "bidirectional"))
      (node (ref "U902") (pin "3") (pinfunction "A2_3") (pintype "bidirectional"))
    )
    (net (code "57") (name "IO-CH8") (class "Default")
      (node (ref "U801") (pin "19") (pinfunction "PB1_19") (pintype "bidirectional"))
      (node (ref "U902") (pin "1") (pinfunction "A1_1") (pintype "bidirectional"))
    )
    (net (code "58") (name "IO-SWCLK") (class "Default")
      (node (ref "JX802") (pin "4") (pinfunction "S_4") (pintype "passive"))
      (node (ref "U801") (pin "37") (pinfunction "PA14_37") (pintype "bidirectional"))
    )
    (net (code "59") (name "IO-SWDIO") (class "Default")
      (node (ref "JX802") (pin "2") (pinfunction "S_2") (pintype "passive"))
      (node (ref "U801") (pin "34") (pinfunction "PA13_34") (pintype "bidirectional"))
    )
    (net (code "60") (name "IO-SWO") (class "Default")
      (node (ref "JX802") (pin "6") (pinfunction "S_6") (pintype "passive"))
      (node (ref "U801") (pin "39") (pinfunction "PB3_39") (pintype "bidirectional"))
    )
    (net (code "61") (name "IO-USART1_RX") (class "Default")
      (node (ref "J801") (pin "P$3") (pinfunction "P$3_P$3") (pintype "bidirectional"))
      (node (ref "JX801") (pin "2") (pinfunction "+5V_2") (pintype "bidirectional"))
      (node (ref "U801") (pin "31") (pinfunction "PA10_31") (pintype "bidirectional"))
    )
    (net (code "62") (name "IO-USART1_TX") (class "Default")
      (node (ref "JX801") (pin "1") (pinfunction "PPM_1") (pintype "bidirectional"))
      (node (ref "R101") (pin "P$2") (pinfunction "2_P$2") (pintype "passive"))
      (node (ref "U801") (pin "30") (pinfunction "PA9_30") (pintype "bidirectional"))
    )
    (net (code "63") (name "IO-VDD_3V3") (class "Default")
      (node (ref "C1004") (pin "P$1") (pinfunction "1_P$1") (pintype "passive"))
      (node (ref "C802") (pin "P$1") (pinfunction "1_P$1") (pintype "passive"))
      (node (ref "C803") (pin "P$1") (pinfunction "1_P$1") (pintype "passive"))
      (node (ref "C804") (pin "P$1") (pinfunction "1_P$1") (pintype "passive"))
      (node (ref "C901") (pin "P$1") (pinfunction "1_P$1") (pintype "passive"))
      (node (ref "C903") (pin "P$1") (pinfunction "1_P$1") (pintype "passive"))
      (node (ref "J702") (pin "P$1") (pinfunction "1_P$1") (pintype "passive"))
      (node (ref "JX802") (pin "1") (pinfunction "S_1") (pintype "passive"))
      (node (ref "U$1002") (pin "7") (pinfunction "VOUT2_7") (pintype "bidirectional"))
      (node (ref "U$701") (pin "C") (pinfunction "C_C") (pintype "passive"))
      (node (ref "U801") (pin "24") (pinfunction "VDD_1_24") (pintype "power_in"))
      (node (ref "U801") (pin "36") (pinfunction "VDD_2_36") (pintype "power_in"))
      (node (ref "U801") (pin "48") (pinfunction "VDD_3_48") (pintype "power_in"))
      (node (ref "U801") (pin "9") (pinfunction "VDDA_9") (pintype "power_in"))
      (node (ref "U902") (pin "10") (pinfunction "OE_10") (pintype "input"))
      (node (ref "U902") (pin "19") (pinfunction "VCCB_19") (pintype "input"))
      (node (ref "U902") (pin "2") (pinfunction "VCCA_2") (pintype "input"))
      (node (ref "U903") (pin "8") (pinfunction "VCC_8") (pintype "power_in"))
    )
    (net (code "64") (name "IO-VDD_5V5") (class "Default")
      (node (ref "C1001") (pin "P$1") (pinfunction "1_P$1") (pintype "passive"))
      (node (ref "D1001") (pin "3") (pinfunction "CC_3") (pintype "passive"))
      (node (ref "J901") (pin "2") (pinfunction "S_2") (pintype "passive"))
      (node (ref "LED702") (pin "A") (pinfunction "A_A") (pintype "passive"))
      (node (ref "LED703") (pin "A") (pinfunction "A_A") (pintype "passive"))
      (node (ref "LED705") (pin "A") (pinfunction "A_A") (pintype "passive"))
      (node (ref "U$1002") (pin "1") (pinfunction "VIN_1") (pintype "bidirectional"))
      (node (ref "U$1002") (pin "4") (pinfunction "EN2_4") (pintype "bidirectional"))
    )
    (net (code "65") (name "IO-~{RESET}") (class "Default")
      (node (ref "C801") (pin "P$2") (pinfunction "2_P$2") (pintype "passive"))
      (node (ref "S801") (pin "A1") (pinfunction "1_A1") (pintype "passive"))
      (node (ref "U$1002") (pin "3") (pinfunction "POR2_3") (pintype "bidirectional"))
      (node (ref "U801") (pin "7") (pinfunction "NRST_7") (pintype "input"))
    )
    (net (code "66") (name "IO-~{VDD_SERVO_IN_FAULT}") (class "Default")
      (node (ref "U$1001") (pin "4") (pinfunction "~{FAULT}_4") (pintype "bidirectional"))
      (node (ref "U801") (pin "38") (pinfunction "PA15_38") (pintype "bidirectional"))
    )
    (net (code "67") (name "MAG_DRDY") (class "Default")
      (node (ref "U$1") (pin "4") (pinfunction "S_4") (pintype "passive"))
      (node (ref "U$501") (pin "9") (pinfunction "INT2_9") (pintype "bidirectional"))
      (node (ref "U101") (pin "36") (pinfunction "PB1_36") (pintype "bidirectional"))
    )
    (net (code "68") (name "Net-(C102-1)") (class "Default")
      (node (ref "C102") (pin "P$1") (pinfunction "1_P$1") (pintype "passive"))
      (node (ref "U101") (pin "12") (pinfunction "OSC_IN_12") (pintype "input"))
      (node (ref "X101") (pin "3") (pinfunction "3_3") (pintype "bidirectional"))
    )
    (net (code "69") (name "Net-(C103-2)") (class "Default")
      (node (ref "C103") (pin "P$2") (pinfunction "2_P$2") (pintype "passive"))
      (node (ref "U101") (pin "13") (pinfunction "OSC_OUT_13") (pintype "output"))
      (node (ref "X101") (pin "1") (pinfunction "1_1") (pintype "bidirectional"))
    )
    (net (code "70") (name "Net-(C504-1)") (class "Default")
      (node (ref "C504") (pin "P$1") (pinfunction "1_P$1") (pintype "passive"))
      (node (ref "U501") (pin "14") (pinfunction "PLLFILT_14") (pintype "bidirectional"))
    )
    (net (code "71") (name "Net-(C505-1)") (class "Default")
      (node (ref "C505") (pin "P$1") (pinfunction "1_P$1") (pintype "passive"))
      (node (ref "U502") (pin "14") (pinfunction "CAP_14") (pintype "bidirectional"))
    )
    (net (code "72") (name "Net-(C509-1)") (class "Default")
      (node (ref "C509") (pin "P$1") (pinfunction "1_P$1") (pintype "passive"))
      (node (ref "U$501") (pin "15") (pinfunction "C1_15") (pintype "bidirectional"))
    )
    (net (code "73") (name "Net-(C510-1)") (class "Default")
      (node (ref "C510") (pin "P$1") (pinfunction "1_P$1") (pintype "passive"))
      (node (ref "U$501") (pin "2") (pinfunction "SETC_2") (pintype "bidirectional"))
    )
    (net (code "74") (name "Net-(C510-2)") (class "Default")
      (node (ref "C510") (pin "P$2") (pinfunction "2_P$2") (pintype "passive"))
      (node (ref "U$501") (pin "3") (pinfunction "SETP_3") (pintype "bidirectional"))
    )
    (net (code "75") (name "Net-(C601-1)") (class "Default")
      (node (ref "C601") (pin "P$1") (pinfunction "1_P$1") (pintype "passive"))
      (node (ref "L603") (pin "P$2") (pinfunction "P$2_P$2") (pintype "bidirectional"))
      (node (ref "R603") (pin "P$2") (pinfunction "2_P$2") (pintype "passive"))
      (node (ref "U$605") (pin "1") (pinfunction "VIN_1") (pintype "bidirectional"))
      (node (ref "U$605") (pin "4") (pinfunction "EN2_4") (pintype "bidirectional"))
    )
    (net (code "76") (name "Net-(C602-2)") (class "Default")
      (node (ref "C602") (pin "P$2") (pinfunction "2_P$2") (pintype "passive"))
      (node (ref "U$605") (pin "6") (pinfunction "CSET_6") (pintype "bidirectional"))
    )
    (net (code "77") (name "Net-(C611-1)") (class "Default")
      (node (ref "C611") (pin "P$1") (pinfunction "1_P$1") (pintype "passive"))
      (node (ref "U101") (pin "49") (pinfunction "VCAP_1_49") (pintype "power_in"))
    )
    (net (code "78") (name "Net-(C613-1)") (class "Default")
      (node (ref "C613") (pin "P$1") (pinfunction "1_P$1") (pintype "passive"))
      (node (ref "U101") (pin "73") (pinfunction "VCAP_2_73") (pintype "power_in"))
    )
    (net (code "79") (name "Net-(C703-1)") (class "Default")
      (node (ref "C703") (pin "P$1") (pinfunction "1_P$1") (pintype "passive"))
      (node (ref "J701") (pin "P$1") (pinfunction "1_P$1") (pintype "passive"))
      (node (ref "R703") (pin "P$1") (pinfunction "1_P$1") (pintype "passive"))
      (node (ref "U702") (pin "1") (pinfunction "OUT_1") (pintype "output"))
    )
    (net (code "80") (name "Net-(C704-1)") (class "Default")
      (node (ref "C704") (pin "P$1") (pinfunction "1_P$1") (pintype "passive"))
      (node (ref "R705") (pin "P$1") (pinfunction "1_P$1") (pintype "passive"))
      (node (ref "U702") (pin "6") (pinfunction "VCC_6") (pintype "bidirectional"))
    )
    (net (code "81") (name "Net-(C805-1)") (class "Default")
      (node (ref "C805") (pin "P$1") (pinfunction "1_P$1") (pintype "passive"))
      (node (ref "U801") (pin "5") (pinfunction "PD0/OSC<=_5") (pintype "bidirectional"))
      (node (ref "X801") (pin "3") (pinfunction "3_3") (pintype "bidirectional"))
    )
    (net (code "82") (name "Net-(C806-2)") (class "Default")
      (node (ref "C806") (pin "P$2") (pinfunction "2_P$2") (pintype "passive"))
      (node (ref "U801") (pin "6") (pinfunction "PD1/OSC=>_6") (pintype "bidirectional"))
      (node (ref "X801") (pin "1") (pinfunction "1_1") (pintype "bidirectional"))
    )
    (net (code "83") (name "Net-(C1002-1)") (class "Default")
      (node (ref "C1002") (pin "P$1") (pinfunction "1_P$1") (pintype "passive"))
      (node (ref "U$1002") (pin "6") (pinfunction "CSET_6") (pintype "bidirectional"))
    )
    (net (code "84") (name "Net-(D1-C)") (class "Default")
      (node (ref "D1") (pin "CATHODE") (pinfunction "C_CATHODE") (pintype "passive"))
      (node (ref "L901") (pin "P$1") (pinfunction "P$1_P$1") (pintype "bidirectional"))
      (node (ref "U$6") (pin "C") (pinfunction "C_C") (pintype "passive"))
    )
    (net (code "85") (name "Net-(D1001-A1)") (class "Default")
      (node (ref "D1001") (pin "1") (pinfunction "A1_1") (pintype "passive"))
      (node (ref "F2") (pin "2") (pinfunction "2_2") (pintype "bidirectional"))
    )
    (net (code "86") (name "Net-(D1001-A2)") (class "Default")
      (node (ref "D1001") (pin "2") (pinfunction "A2_2") (pintype "passive"))
      (node (ref "U$1001") (pin "8") (pinfunction "OUT_8") (pintype "bidirectional"))
    )
    (net (code "87") (name "Net-(J201-1)") (class "Default")
      (node (ref "J201") (pin "P$1") (pinfunction "1_P$1") (pintype "passive"))
      (node (ref "L201") (pin "P$2") (pinfunction "P$2_P$2") (pintype "bidirectional"))
      (node (ref "U$201") (pin "C") (pinfunction "C_C") (pintype "passive"))
    )
    (net (code "88") (name "Net-(J202-1)") (class "Default")
      (node (ref "J202") (pin "P$1") (pinfunction "1_P$1") (pintype "passive"))
      (node (ref "L202") (pin "P$2") (pinfunction "P$2_P$2") (pintype "bidirectional"))
      (node (ref "U$202") (pin "C") (pinfunction "C_C") (pintype "passive"))
    )
    (net (code "89") (name "Net-(J203-1)") (class "Default")
      (node (ref "J203") (pin "P$1") (pinfunction "1_P$1") (pintype "passive"))
      (node (ref "J204") (pin "P$1") (pinfunction "1_P$1") (pintype "passive"))
      (node (ref "L203") (pin "P$2") (pinfunction "P$2_P$2") (pintype "bidirectional"))
      (node (ref "U$203") (pin "C") (pinfunction "C_C") (pintype "passive"))
    )
    (net (code "90") (name "Net-(J203-4)") (class "Default")
      (node (ref "J203") (pin "P$4") (pinfunction "4_P$4") (pintype "passive"))
      (node (ref "R12") (pin "P$2") (pinfunction "2_P$2") (pintype "passive"))
    )
    (net (code "91") (name "Net-(J203-5)") (class "Default")
      (node (ref "J203") (pin "P$5") (pinfunction "5_P$5") (pintype "passive"))
      (node (ref "R13") (pin "P$2") (pinfunction "2_P$2") (pintype "passive"))
    )
    (net (code "92") (name "Net-(J301-2)") (class "Default")
      (node (ref "J301") (pin "D-") (pinfunction "2_D-") (pintype "bidirectional"))
      (node (ref "J302") (pin "P$3") (pinfunction "3_P$3") (pintype "passive"))
      (node (ref "U$301") (pin "1") (pinfunction "D1I_1") (pintype "bidirectional"))
    )
    (net (code "93") (name "Net-(J301-3)") (class "Default")
      (node (ref "J301") (pin "D+") (pinfunction "3_D+") (pintype "bidirectional"))
      (node (ref "J302") (pin "P$2") (pinfunction "2_P$2") (pintype "passive"))
      (node (ref "U$301") (pin "3") (pinfunction "D2I_3") (pintype "bidirectional"))
    )
    (net (code "94") (name "Net-(J401-1)") (class "Default")
      (node (ref "J401") (pin "P$1") (pinfunction "1_P$1") (pintype "passive"))
      (node (ref "J402") (pin "P$1") (pinfunction "1_P$1") (pintype "passive"))
      (node (ref "L401") (pin "P$2") (pinfunction "P$2_P$2") (pintype "bidirectional"))
      (node (ref "U$401") (pin "C") (pinfunction "C_C") (pintype "passive"))
    )
    (net (code "95") (name "Net-(J401-2)") (class "Default")
      (node (ref "J401") (pin "P$2") (pinfunction "2_P$2") (pintype "passive"))
      (node (ref "R404") (pin "P$2") (pinfunction "2_P$2") (pintype "passive"))
    )
    (net (code "96") (name "Net-(J401-3)") (class "Default")
      (node (ref "J401") (pin "P$3") (pinfunction "3_P$3") (pintype "passive"))
      (node (ref "R405") (pin "P$2") (pinfunction "2_P$2") (pintype "passive"))
    )
    (net (code "97") (name "Net-(J403-1)") (class "Default")
      (node (ref "J403") (pin "P$1") (pinfunction "1_P$1") (pintype "passive"))
      (node (ref "L402") (pin "P$2") (pinfunction "P$2_P$2") (pintype "bidirectional"))
      (node (ref "U$402") (pin "C") (pinfunction "C_C") (pintype "passive"))
    )
    (net (code "98") (name "Net-(J404-1)") (class "Default")
      (node (ref "J404") (pin "P$1") (pinfunction "1_P$1") (pintype "passive"))
      (node (ref "L404") (pin "P$2") (pinfunction "P$2_P$2") (pintype "bidirectional"))
      (node (ref "U$403") (pin "C") (pinfunction "C_C") (pintype "passive"))
    )
    (net (code "99") (name "Net-(J404-2)") (class "Default")
      (node (ref "J404") (pin "P$2") (pinfunction "2_P$2") (pintype "passive"))
      (node (ref "R407") (pin "P$2") (pinfunction "2_P$2") (pintype "passive"))
    )
    (net (code "100") (name "Net-(J404-4)") (class "Default")
      (node (ref "J404") (pin "P$4") (pinfunction "4_P$4") (pintype "passive"))
      (node (ref "R408") (pin "P$2") (pinfunction "2_P$2") (pintype "passive"))
    )
    (net (code "101") (name "Net-(J405-1)") (class "Default")
      (node (ref "J405") (pin "P$1") (pinfunction "1_P$1") (pintype "passive"))
      (node (ref "L403") (pin "P$2") (pinfunction "P$2_P$2") (pintype "bidirectional"))
      (node (ref "U$404") (pin "C") (pinfunction "C_C") (pintype "passive"))
    )
    (net (code "102") (name "Net-(J601-3)") (class "Default")
      (node (ref "J601") (pin "P$3") (pinfunction "3_P$3") (pintype "passive"))
      (node (ref "L601") (pin "P$1") (pinfunction "P$1_P$1") (pintype "bidirectional"))
    )
    (net (code "103") (name "Net-(J601-4)") (class "Default")
      (node (ref "J601") (pin "P$4") (pinfunction "4_P$4") (pintype "passive"))
      (node (ref "L602") (pin "P$1") (pinfunction "P$1_P$1") (pintype "bidirectional"))
    )
    (net (code "104") (name "Net-(J702-2)") (class "Default")
      (node (ref "J702") (pin "P$2") (pinfunction "2_P$2") (pintype "passive"))
      (node (ref "R710") (pin "P$1") (pinfunction "1_P$1") (pintype "passive"))
    )
    (net (code "105") (name "Net-(J901A-S)") (class "Default")
      (node (ref "J901") (pin "1") (pinfunction "S_1") (pintype "passive"))
      (node (ref "R909") (pin "P$2") (pinfunction "2_P$2") (pintype "passive"))
    )
    (net (code "106") (name "Net-(J901B-S)") (class "Default")
      (node (ref "J901") (pin "10") (pinfunction "S_10") (pintype "passive"))
      (node (ref "R914") (pin "P$2") (pinfunction "2_P$2") (pintype "passive"))
    )
    (net (code "107") (name "Net-(J901C-S)") (class "Default")
      (node (ref "J901") (pin "13") (pinfunction "S_13") (pintype "passive"))
      (node (ref "R906") (pin "P$2") (pinfunction "2_P$2") (pintype "passive"))
    )
    (net (code "108") (name "Net-(J901D-S)") (class "Default")
      (node (ref "J901") (pin "16") (pinfunction "S_16") (pintype "passive"))
      (node (ref "R915") (pin "P$2") (pinfunction "2_P$2") (pintype "passive"))
    )
    (net (code "109") (name "Net-(J901E-S)") (class "Default")
      (node (ref "J901") (pin "19") (pinfunction "S_19") (pintype "passive"))
      (node (ref "R907") (pin "P$2") (pinfunction "2_P$2") (pintype "passive"))
    )
    (net (code "110") (name "Net-(J901G-S)") (class "Default")
      (node (ref "J901") (pin "22") (pinfunction "S_22") (pintype "passive"))
      (node (ref "R916") (pin "P$2") (pinfunction "2_P$2") (pintype "passive"))
    )
    (net (code "111") (name "Net-(J901H-S)") (class "Default")
      (node (ref "J901") (pin "25") (pinfunction "S_25") (pintype "passive"))
      (node (ref "R908") (pin "P$2") (pinfunction "2_P$2") (pintype "passive"))
    )
    (net (code "112") (name "Net-(J901I-S)") (class "Default")
      (node (ref "J901") (pin "28") (pinfunction "S_28") (pintype "passive"))
      (node (ref "R917") (pin "P$2") (pinfunction "2_P$2") (pintype "passive"))
    )
    (net (code "113") (name "Net-(J901J-S)") (class "Default")
      (node (ref "J901") (pin "31") (pinfunction "S_31") (pintype "passive"))
      (node (ref "R902") (pin "P$2") (pinfunction "2_P$2") (pintype "passive"))
    )
    (net (code "114") (name "Net-(J901K-S)") (class "Default")
      (node (ref "J901") (pin "34") (pinfunction "S_34") (pintype "passive"))
      (node (ref "R911") (pin "P$2") (pinfunction "2_P$2") (pintype "passive"))
    )
    (net (code "115") (name "Net-(J901L-S)") (class "Default")
      (node (ref "J901") (pin "37") (pinfunction "S_37") (pintype "passive"))
      (node (ref "R903") (pin "P$2") (pinfunction "2_P$2") (pintype "passive"))
    )
    (net (code "116") (name "Net-(J901M-S)") (class "Default")
      (node (ref "J901") (pin "4") (pinfunction "S_4") (pintype "passive"))
      (node (ref "R910") (pin "P$2") (pinfunction "2_P$2") (pintype "passive"))
    )
    (net (code "117") (name "Net-(J901N-S)") (class "Default")
      (node (ref "J901") (pin "40") (pinfunction "S_40") (pintype "passive"))
      (node (ref "R912") (pin "P$2") (pinfunction "2_P$2") (pintype "passive"))
    )
    (net (code "118") (name "Net-(J901O-S)") (class "Default")
      (node (ref "J901") (pin "43") (pinfunction "S_43") (pintype "passive"))
      (node (ref "R904") (pin "P$2") (pinfunction "2_P$2") (pintype "passive"))
    )
    (net (code "119") (name "Net-(J901P-S)") (class "Default")
      (node (ref "J901") (pin "46") (pinfunction "S_46") (pintype "passive"))
      (node (ref "R913") (pin "P$2") (pinfunction "2_P$2") (pintype "passive"))
    )
    (net (code "120") (name "Net-(J901Q-S)") (class "Default")
      (node (ref "J901") (pin "7") (pinfunction "S_7") (pintype "passive"))
      (node (ref "R905") (pin "P$2") (pinfunction "2_P$2") (pintype "passive"))
    )
    (net (code "121") (name "Net-(L701-2)") (class "Default")
      (node (ref "L701") (pin "P$2") (pinfunction "2_P$2") (pintype "passive"))
      (node (ref "U702") (pin "5") (pinfunction "SW_5") (pintype "passive"))
    )
    (net (code "122") (name "Net-(R1-2)") (class "Default")
      (node (ref "R1") (pin "P$2") (pinfunction "2_P$2") (pintype "passive"))
      (node (ref "R2") (pin "P$1") (pinfunction "1_P$1") (pintype "passive"))
      (node (ref "U$2") (pin "P$1") (pinfunction "UV1_P$1") (pintype "bidirectional"))
    )
    (net (code "123") (name "Net-(R2-2)") (class "Default")
      (node (ref "R2") (pin "P$2") (pinfunction "2_P$2") (pintype "passive"))
      (node (ref "R5") (pin "P$1") (pinfunction "1_P$1") (pintype "passive"))
      (node (ref "U$2") (pin "P$2") (pinfunction "OV1_P$2") (pintype "bidirectional"))
    )
    (net (code "124") (name "Net-(R3-1)") (class "Default")
      (node (ref "R3") (pin "P$1") (pinfunction "1_P$1") (pintype "passive"))
      (node (ref "R707") (pin "P$2") (pinfunction "2_P$2") (pintype "passive"))
    )
    (net (code "125") (name "Net-(R3-2)") (class "Default")
      (node (ref "LED701") (pin "C") (pinfunction "C_C") (pintype "passive"))
      (node (ref "R3") (pin "P$2") (pinfunction "2_P$2") (pintype "passive"))
    )
    (net (code "126") (name "Net-(R4-1)") (class "Default")
      (node (ref "R4") (pin "P$1") (pinfunction "1_P$1") (pintype "passive"))
      (node (ref "R709") (pin "P$2") (pinfunction "2_P$2") (pintype "passive"))
    )
    (net (code "127") (name "Net-(R4-2)") (class "Default")
      (node (ref "LED703") (pin "C") (pinfunction "C_C") (pintype "passive"))
      (node (ref "R4") (pin "P$2") (pinfunction "2_P$2") (pintype "passive"))
    )
    (net (code "128") (name "Net-(R6-2)") (class "Default")
      (node (ref "R6") (pin "P$2") (pinfunction "2_P$2") (pintype "passive"))
      (node (ref "R7") (pin "P$1") (pinfunction "1_P$1") (pintype "passive"))
      (node (ref "U$2") (pin "P$5") (pinfunction "UV3_P$5") (pintype "bidirectional"))
    )
    (net (code "129") (name "Net-(R7-2)") (class "Default")
      (node (ref "R7") (pin "P$2") (pinfunction "2_P$2") (pintype "passive"))
      (node (ref "R8") (pin "P$1") (pinfunction "1_P$1") (pintype "passive"))
      (node (ref "U$2") (pin "P$6") (pinfunction "OV3_P$6") (pintype "bidirectional"))
    )
    (net (code "130") (name "Net-(R10-1)") (class "Default")
      (node (ref "R10") (pin "P$1") (pinfunction "1_P$1") (pintype "passive"))
      (node (ref "R9") (pin "P$2") (pinfunction "2_P$2") (pintype "passive"))
      (node (ref "U$2") (pin "P$3") (pinfunction "UV2_P$3") (pintype "bidirectional"))
    )
    (net (code "131") (name "Net-(R10-2)") (class "Default")
      (node (ref "R10") (pin "P$2") (pinfunction "2_P$2") (pintype "passive"))
      (node (ref "R11") (pin "P$1") (pinfunction "1_P$1") (pintype "passive"))
      (node (ref "U$2") (pin "P$4") (pinfunction "OV2_P$4") (pintype "bidirectional"))
    )
    (net (code "132") (name "Net-(R101-1)") (class "Default")
      (node (ref "R101") (pin "P$1") (pinfunction "1_P$1") (pintype "passive"))
      (node (ref "U101") (pin "69") (pinfunction "PA10_69") (pintype "bidirectional"))
    )
    (net (code "133") (name "Net-(R102-1)") (class "Default")
      (node (ref "R102") (pin "P$1") (pinfunction "1_P$1") (pintype "passive"))
      (node (ref "U101") (pin "37") (pinfunction "PB2_37") (pintype "bidirectional"))
    )
    (net (code "134") (name "Net-(R201-1)") (class "Default")
      (node (ref "R201") (pin "P$1") (pinfunction "1_P$1") (pintype "passive"))
      (node (ref "U201") (pin "20") (pinfunction "B1_20") (pintype "bidirectional"))
    )
    (net (code "135") (name "Net-(R202-1)") (class "Default")
      (node (ref "R202") (pin "P$1") (pinfunction "1_P$1") (pintype "passive"))
      (node (ref "U201") (pin "17") (pinfunction "B3_17") (pintype "bidirectional"))
    )
    (net (code "136") (name "Net-(R203-1)") (class "Default")
      (node (ref "R203") (pin "P$1") (pinfunction "1_P$1") (pintype "passive"))
      (node (ref "U201") (pin "15") (pinfunction "B5_15") (pintype "bidirectional"))
    )
    (net (code "137") (name "Net-(R204-1)") (class "Default")
      (node (ref "R204") (pin "P$1") (pinfunction "1_P$1") (pintype "passive"))
      (node (ref "U201") (pin "13") (pinfunction "B7_13") (pintype "bidirectional"))
    )
    (net (code "138") (name "Net-(R205-1)") (class "Default")
      (node (ref "R205") (pin "P$1") (pinfunction "1_P$1") (pintype "passive"))
      (node (ref "U202") (pin "17") (pinfunction "B3_17") (pintype "bidirectional"))
    )
    (net (code "139") (name "Net-(R206-1)") (class "Default")
      (node (ref "R206") (pin "P$1") (pinfunction "1_P$1") (pintype "passive"))
      (node (ref "U202") (pin "15") (pinfunction "B5_15") (pintype "bidirectional"))
    )
    (net (code "140") (name "Net-(R207-1)") (class "Default")
      (node (ref "R207") (pin "P$1") (pinfunction "1_P$1") (pintype "passive"))
      (node (ref "U202") (pin "13") (pinfunction "B7_13") (pintype "bidirectional"))
    )
    (net (code "141") (name "Net-(R208-1)") (class "Default")
      (node (ref "R208") (pin "P$1") (pinfunction "1_P$1") (pintype "passive"))
      (node (ref "U201") (pin "18") (pinfunction "B2_18") (pintype "bidirectional"))
    )
    (net (code "142") (name "Net-(R209-1)") (class "Default")
      (node (ref "R209") (pin "P$1") (pinfunction "1_P$1") (pintype "passive"))
      (node (ref "U201") (pin "16") (pinfunction "B4_16") (pintype "bidirectional"))
    )
    (net (code "143") (name "Net-(R210-1)") (class "Default")
      (node (ref "R210") (pin "P$1") (pinfunction "1_P$1") (pintype "passive"))
      (node (ref "U201") (pin "14") (pinfunction "B6_14") (pintype "bidirectional"))
    )
    (net (code "144") (name "Net-(R211-1)") (class "Default")
      (node (ref "R211") (pin "P$1") (pinfunction "1_P$1") (pintype "passive"))
      (node (ref "U201") (pin "12") (pinfunction "B8_12") (pintype "bidirectional"))
    )
    (net (code "145") (name "Net-(R212-1)") (class "Default")
      (node (ref "R212") (pin "P$1") (pinfunction "1_P$1") (pintype "passive"))
      (node (ref "U202") (pin "16") (pinfunction "B4_16") (pintype "bidirectional"))
    )
    (net (code "146") (name "Net-(R213-1)") (class "Default")
      (node (ref "R213") (pin "P$1") (pinfunction "1_P$1") (pintype "passive"))
      (node (ref "U202") (pin "14") (pinfunction "B6_14") (pintype "bidirectional"))
    )
    (net (code "147") (name "Net-(R214-1)") (class "Default")
      (node (ref "R214") (pin "P$1") (pinfunction "1_P$1") (pintype "passive"))
      (node (ref "U202") (pin "12") (pinfunction "B8_12") (pintype "bidirectional"))
    )
    (net (code "148") (name "Net-(R602-1)") (class "Default")
      (node (ref "R602") (pin "P$1") (pinfunction "1_P$1") (pintype "passive"))
      (node (ref "U$602") (pin "7") (pinfunction "ILIM_7") (pintype "bidirectional"))
    )
    (net (code "149") (name "Net-(R604-2)") (class "Default")
      (node (ref "L601") (pin "P$2") (pinfunction "P$2_P$2") (pintype "bidirectional"))
      (node (ref "R604") (pin "P$2") (pinfunction "2_P$2") (pintype "passive"))
    )
    (net (code "150") (name "Net-(R605-2)") (class "Default")
      (node (ref "L602") (pin "P$2") (pinfunction "P$2_P$2") (pintype "bidirectional"))
      (node (ref "R605") (pin "P$2") (pinfunction "2_P$2") (pintype "passive"))
    )
    (net (code "151") (name "Net-(R606-1)") (class "Default")
      (node (ref "R606") (pin "P$1") (pinfunction "1_P$1") (pintype "passive"))
      (node (ref "U$604") (pin "7") (pinfunction "ILIM_7") (pintype "bidirectional"))
    )
    (net (code "152") (name "Net-(R701-1)") (class "Default")
      (node (ref "R701") (pin "P$1") (pinfunction "1_P$1") (pintype "passive"))
      (node (ref "U702") (pin "7") (pinfunction "+IN_7") (pintype "input"))
    )
    (net (code "153") (name "Net-(R702-1)") (class "Default")
      (node (ref "R702") (pin "P$1") (pinfunction "1_P$1") (pintype "passive"))
      (node (ref "R703") (pin "P$2") (pinfunction "2_P$2") (pintype "passive"))
      (node (ref "U702") (pin "8") (pinfunction "-IN_8") (pintype "input"))
    )
    (net (code "154") (name "Net-(R704-2)") (class "Default")
      (node (ref "R704") (pin "P$2") (pinfunction "2_P$2") (pintype "passive"))
      (node (ref "U701") (pin "6") (pinfunction "REXT_6") (pintype "bidirectional"))
    )
    (net (code "155") (name "Net-(R705-2)") (class "Default")
      (node (ref "R705") (pin "P$2") (pinfunction "2_P$2") (pintype "passive"))
      (node (ref "R706") (pin "P$1") (pinfunction "1_P$1") (pintype "passive"))
      (node (ref "U702") (pin "2") (pinfunction "FB_2") (pintype "bidirectional"))
    )
    (net (code "156") (name "Net-(R708-2)") (class "Default")
      (node (ref "LED702") (pin "C") (pinfunction "C_C") (pintype "passive"))
      (node (ref "R708") (pin "P$2") (pinfunction "2_P$2") (pintype "passive"))
    )
    (net (code "157") (name "Net-(R711-2)") (class "Default")
      (node (ref "LED704") (pin "C") (pinfunction "C_C") (pintype "passive"))
      (node (ref "R711") (pin "P$2") (pinfunction "2_P$2") (pintype "passive"))
    )
    (net (code "158") (name "Net-(R712-2)") (class "Default")
      (node (ref "LED705") (pin "C") (pinfunction "C_C") (pintype "passive"))
      (node (ref "R712") (pin "P$2") (pinfunction "2_P$2") (pintype "passive"))
    )
    (net (code "159") (name "Net-(R802-1)") (class "Default")
      (node (ref "R802") (pin "P$1") (pinfunction "1_P$1") (pintype "passive"))
      (node (ref "U801") (pin "20") (pinfunction "PB2_20") (pintype "bidirectional"))
    )
    (net (code "160") (name "Net-(R803-1)") (class "Default")
      (node (ref "R803") (pin "P$1") (pinfunction "1_P$1") (pintype "passive"))
      (node (ref "U801") (pin "12") (pinfunction "PA2_12") (pintype "bidirectional"))
    )
    (net (code "161") (name "Net-(R804-1)") (class "Default")
      (node (ref "R804") (pin "P$1") (pinfunction "1_P$1") (pintype "passive"))
      (node (ref "U801") (pin "13") (pinfunction "PA3_13") (pintype "bidirectional"))
    )
    (net (code "162") (name "Net-(R901-2)") (class "Default")
      (node (ref "R901") (pin "P$2") (pinfunction "2_P$2") (pintype "passive"))
      (node (ref "R910") (pin "P$1") (pinfunction "1_P$1") (pintype "passive"))
      (node (ref "U$902") (pin "C") (pinfunction "C_C") (pintype "passive"))
      (node (ref "U903") (pin "3") (pinfunction "2Y_3") (pintype "bidirectional"))
    )
    (net (code "163") (name "Net-(R902-1)") (class "Default")
      (node (ref "R902") (pin "P$1") (pinfunction "1_P$1") (pintype "passive"))
      (node (ref "U901") (pin "20") (pinfunction "B1_20") (pintype "bidirectional"))
    )
    (net (code "164") (name "Net-(R903-1)") (class "Default")
      (node (ref "R903") (pin "P$1") (pinfunction "1_P$1") (pintype "passive"))
      (node (ref "U901") (pin "17") (pinfunction "B3_17") (pintype "bidirectional"))
    )
    (net (code "165") (name "Net-(R904-1)") (class "Default")
      (node (ref "R904") (pin "P$1") (pinfunction "1_P$1") (pintype "passive"))
      (node (ref "U901") (pin "15") (pinfunction "B5_15") (pintype "bidirectional"))
    )
    (net (code "166") (name "Net-(R905-1)") (class "Default")
      (node (ref "R905") (pin "P$1") (pinfunction "1_P$1") (pintype "passive"))
      (node (ref "U902") (pin "20") (pinfunction "B1_20") (pintype "bidirectional"))
    )
    (net (code "167") (name "Net-(R906-1)") (class "Default")
      (node (ref "R906") (pin "P$1") (pinfunction "1_P$1") (pintype "passive"))
      (node (ref "U902") (pin "17") (pinfunction "B3_17") (pintype "bidirectional"))
    )
    (net (code "168") (name "Net-(R907-1)") (class "Default")
      (node (ref "R907") (pin "P$1") (pinfunction "1_P$1") (pintype "passive"))
      (node (ref "U902") (pin "15") (pinfunction "B5_15") (pintype "bidirectional"))
    )
    (net (code "169") (name "Net-(R908-1)") (class "Default")
      (node (ref "R908") (pin "P$1") (pinfunction "1_P$1") (pintype "passive"))
      (node (ref "U902") (pin "13") (pinfunction "B7_13") (pintype "bidirectional"))
    )
    (net (code "170") (name "Net-(R911-1)") (class "Default")
      (node (ref "R911") (pin "P$1") (pinfunction "1_P$1") (pintype "passive"))
      (node (ref "U901") (pin "18") (pinfunction "B2_18") (pintype "bidirectional"))
    )
    (net (code "171") (name "Net-(R912-1)") (class "Default")
      (node (ref "R912") (pin "P$1") (pinfunction "1_P$1") (pintype "passive"))
      (node (ref "U901") (pin "16") (pinfunction "B4_16") (pintype "bidirectional"))
    )
    (net (code "172") (name "Net-(R913-1)") (class "Default")
      (node (ref "R913") (pin "P$1") (pinfunction "1_P$1") (pintype "passive"))
      (node (ref "U901") (pin "14") (pinfunction "B6_14") (pintype "bidirectional"))
    )
    (net (code "173") (name "Net-(R914-1)") (class "Default")
      (node (ref "R914") (pin "P$1") (pinfunction "1_P$1") (pintype "passive"))
      (node (ref "U902") (pin "18") (pinfunction "B2_18") (pintype "bidirectional"))
    )
    (net (code "174") (name "Net-(R915-1)") (class "Default")
      (node (ref "R915") (pin "P$1") (pinfunction "1_P$1") (pintype "passive"))
      (node (ref "U902") (pin "16") (pinfunction "B4_16") (pintype "bidirectional"))
    )
    (net (code "175") (name "Net-(R916-1)") (class "Default")
      (node (ref "R916") (pin "P$1") (pinfunction "1_P$1") (pintype "passive"))
      (node (ref "U902") (pin "14") (pinfunction "B6_14") (pintype "bidirectional"))
    )
    (net (code "176") (name "Net-(R917-1)") (class "Default")
      (node (ref "R917") (pin "P$1") (pinfunction "1_P$1") (pintype "passive"))
      (node (ref "U902") (pin "12") (pinfunction "B8_12") (pintype "bidirectional"))
    )
    (net (code "177") (name "Net-(R918-2)") (class "Default")
      (node (ref "R918") (pin "P$2") (pinfunction "2_P$2") (pintype "passive"))
      (node (ref "R922") (pin "P$1") (pinfunction "1_P$1") (pintype "passive"))
    )
    (net (code "178") (name "Net-(R1001-2)") (class "Default")
      (node (ref "R1001") (pin "P$2") (pinfunction "2_P$2") (pintype "passive"))
      (node (ref "U$1001") (pin "7") (pinfunction "ILIM_7") (pintype "bidirectional"))
    )
    (net (code "179") (name "Net-(U$2-G1)") (class "Default")
      (node (ref "U$2") (pin "P$17") (pinfunction "G1_P$17") (pintype "bidirectional"))
      (node (ref "U$3") (pin "P$2") (pinfunction "G_P$2") (pintype "passive"))
      (node (ref "U$3") (pin "P$4") (pinfunction "G_P$4") (pintype "passive"))
    )
    (net (code "180") (name "Net-(U$2-G2)") (class "Default")
      (node (ref "U$2") (pin "P$15") (pinfunction "G2_P$15") (pintype "bidirectional"))
      (node (ref "U$4") (pin "P$2") (pinfunction "G_P$2") (pintype "passive"))
      (node (ref "U$4") (pin "P$4") (pinfunction "G_P$4") (pintype "passive"))
    )
    (net (code "181") (name "Net-(U$2-G3)") (class "Default")
      (node (ref "U$2") (pin "P$13") (pinfunction "G3_P$13") (pintype "bidirectional"))
      (node (ref "U$5") (pin "P$2") (pinfunction "G_P$2") (pintype "passive"))
      (node (ref "U$5") (pin "P$4") (pinfunction "G_P$4") (pintype "passive"))
    )
    (net (code "182") (name "Net-(U$2-VS1)") (class "Default")
      (node (ref "U$2") (pin "P$18") (pinfunction "VS1_P$18") (pintype "bidirectional"))
      (node (ref "U$3") (pin "P$1") (pinfunction "S_P$1") (pintype "passive"))
      (node (ref "U$3") (pin "P$3") (pinfunction "S_P$3") (pintype "passive"))
    )
    (net (code "183") (name "Net-(U$2-VS2)") (class "Default")
      (node (ref "U$2") (pin "P$16") (pinfunction "VS2_P$16") (pintype "bidirectional"))
      (node (ref "U$4") (pin "P$1") (pinfunction "S_P$1") (pintype "passive"))
      (node (ref "U$4") (pin "P$3") (pinfunction "S_P$3") (pintype "passive"))
    )
    (net (code "184") (name "Net-(U$2-VS3)") (class "Default")
      (node (ref "U$2") (pin "P$14") (pinfunction "VS3_P$14") (pintype "bidirectional"))
      (node (ref "U$5") (pin "P$1") (pinfunction "S_P$1") (pintype "passive"))
      (node (ref "U$5") (pin "P$3") (pinfunction "S_P$3") (pintype "passive"))
    )
    (net (code "185") (name "Net-(U701-OUT0)") (class "Default")
      (node (ref "U701") (pin "9") (pinfunction "OUT0_9") (pintype "open_collector"))
      (node (ref "U703") (pin "C1") (pinfunction "C_C1") (pintype "passive"))
    )
    (net (code "186") (name "Net-(U701-OUT1)") (class "Default")
      (node (ref "U701") (pin "8") (pinfunction "OUT1_8") (pintype "open_collector"))
      (node (ref "U703") (pin "C2") (pinfunction "C_C2") (pintype "passive"))
    )
    (net (code "187") (name "Net-(U701-OUT2)") (class "Default")
      (node (ref "U701") (pin "7") (pinfunction "OUT2_7") (pintype "open_collector"))
      (node (ref "U703") (pin "C3") (pinfunction "C_C3") (pintype "passive"))
    )
    (net (code "188") (name "OTG_FS_DM") (class "Default")
      (node (ref "U$301") (pin "6") (pinfunction "D1O_6") (pintype "bidirectional"))
      (node (ref "U101") (pin "70") (pinfunction "PA11_70") (pintype "bidirectional"))
    )
    (net (code "189") (name "OTG_FS_DP") (class "Default")
      (node (ref "U$301") (pin "4") (pinfunction "D2O_4") (pintype "bidirectional"))
      (node (ref "U101") (pin "71") (pinfunction "PA12_71") (pintype "bidirectional"))
    )
    (net (code "190") (name "PPM_INPUT") (class "Default")
      (node (ref "R909") (pin "P$1") (pinfunction "1_P$1") (pintype "passive"))
      (node (ref "U$901") (pin "C") (pinfunction "C_C") (pintype "passive"))
      (node (ref "U801") (pin "29") (pinfunction "PA8_29") (pintype "bidirectional"))
      (node (ref "U903") (pin "2") (pinfunction "1A_2") (pintype "bidirectional"))
    )
    (net (code "191") (name "PRESSURE_SENS") (class "Default")
      (node (ref "C401") (pin "P$1") (pinfunction "1_P$1") (pintype "passive"))
      (node (ref "R403") (pin "P$2") (pinfunction "2_P$2") (pintype "passive"))
      (node (ref "R406") (pin "P$1") (pinfunction "1_P$1") (pintype "passive"))
      (node (ref "U101") (pin "34") (pinfunction "PC5_34") (pintype "bidirectional"))
    )
    (net (code "192") (name "PRESSURE_SENS_IN") (class "Default")
      (node (ref "ADC_PR") (pin "P$1") (pinfunction "P$1_P$1") (pintype "passive"))
      (node (ref "J402") (pin "P$2") (pinfunction "2_P$2") (pintype "passive"))
      (node (ref "R406") (pin "P$2") (pinfunction "2_P$2") (pintype "passive"))
    )
    (net (code "193") (name "RSSI_IN") (class "Default")
      (node (ref "R901") (pin "P$1") (pinfunction "1_P$1") (pintype "passive"))
      (node (ref "U801") (pin "15") (pinfunction "PA5_15") (pintype "bidirectional"))
      (node (ref "U801") (pin "33") (pinfunction "PA12_33") (pintype "bidirectional"))
    )
    (net (code "194") (name "SAFETY") (class "Default")
      (node (ref "J702") (pin "P$3") (pinfunction "3_P$3") (pintype "passive"))
      (node (ref "R713") (pin "P$1") (pinfunction "1_P$1") (pintype "passive"))
      (node (ref "U801") (pin "41") (pinfunction "PB5_41") (pintype "bidirectional"))
    )
    (net (code "195") (name "SBUS_INPUT") (class "Default")
      (node (ref "U801") (pin "22") (pinfunction "PB11_22") (pintype "bidirectional"))
      (node (ref "U903") (pin "6") (pinfunction "1Y_6") (pintype "bidirectional"))
    )
    (net (code "196") (name "SBUS_OUTPUT") (class "Default")
      (node (ref "U801") (pin "21") (pinfunction "PB10_21") (pintype "bidirectional"))
      (node (ref "U903") (pin "5") (pinfunction "2A_5") (pintype "bidirectional"))
    )
    (net (code "197") (name "SDIO_CK") (class "Default")
      (node (ref "U101") (pin "80") (pinfunction "PC12_80") (pintype "bidirectional"))
      (node (ref "U301") (pin "5") (pinfunction "CLK_5") (pintype "bidirectional"))
    )
    (net (code "198") (name "SDIO_CMD") (class "Default")
      (node (ref "R303") (pin "P$1") (pinfunction "1_P$1") (pintype "passive"))
      (node (ref "U101") (pin "83") (pinfunction "PD2_83") (pintype "bidirectional"))
      (node (ref "U301") (pin "3") (pinfunction "CMD_3") (pintype "bidirectional"))
    )
    (net (code "199") (name "SDIO_D0") (class "Default")
      (node (ref "R304") (pin "P$1") (pinfunction "1_P$1") (pintype "passive"))
      (node (ref "U101") (pin "65") (pinfunction "PC8_65") (pintype "bidirectional"))
      (node (ref "U301") (pin "7") (pinfunction "D0_7") (pintype "bidirectional"))
    )
    (net (code "200") (name "SDIO_D1") (class "Default")
      (node (ref "R305") (pin "P$1") (pinfunction "1_P$1") (pintype "passive"))
      (node (ref "U101") (pin "66") (pinfunction "PC9_66") (pintype "bidirectional"))
      (node (ref "U301") (pin "8") (pinfunction "D1_8") (pintype "bidirectional"))
    )
    (net (code "201") (name "SDIO_D2") (class "Default")
      (node (ref "R301") (pin "P$1") (pinfunction "1_P$1") (pintype "passive"))
      (node (ref "U101") (pin "78") (pinfunction "PC10_78") (pintype "bidirectional"))
      (node (ref "U301") (pin "1") (pinfunction "D2_1") (pintype "bidirectional"))
    )
    (net (code "202") (name "SDIO_D3") (class "Default")
      (node (ref "R302") (pin "P$1") (pinfunction "1_P$1") (pintype "passive"))
      (node (ref "U101") (pin "79") (pinfunction "PC11_79") (pintype "bidirectional"))
      (node (ref "U301") (pin "2") (pinfunction "D3_2") (pintype "bidirectional"))
    )
    (net (code "203") (name "SERIAL1_CTS") (class "Default")
      (node (ref "J201") (pin "P$4") (pinfunction "4_P$4") (pintype "passive"))
      (node (ref "R211") (pin "P$2") (pinfunction "2_P$2") (pintype "passive"))
    )
    (net (code "204") (name "SERIAL1_RTS") (class "Default")
      (node (ref "J201") (pin "P$5") (pinfunction "5_P$5") (pintype "passive"))
      (node (ref "R204") (pin "P$2") (pinfunction "2_P$2") (pintype "passive"))
    )
    (net (code "205") (name "SERIAL1_RX") (class "Default")
      (node (ref "J201") (pin "P$3") (pinfunction "3_P$3") (pintype "passive"))
      (node (ref "R203") (pin "P$2") (pinfunction "2_P$2") (pintype "passive"))
      (node (ref "S1RX") (pin "P$1") (pinfunction "P$1_P$1") (pintype "passive"))
    )
    (net (code "206") (name "SERIAL1_TX") (class "Default")
      (node (ref "J201") (pin "P$2") (pinfunction "2_P$2") (pintype "passive"))
      (node (ref "R210") (pin "P$2") (pinfunction "2_P$2") (pintype "passive"))
      (node (ref "S1TX") (pin "P$1") (pinfunction "P$1_P$1") (pintype "passive"))
    )
    (net (code "207") (name "SERIAL2_CTS") (class "Default")
      (node (ref "J202") (pin "P$4") (pinfunction "4_P$4") (pintype "passive"))
      (node (ref "R208") (pin "P$2") (pinfunction "2_P$2") (pintype "passive"))
    )
    (net (code "208") (name "SERIAL2_RTS") (class "Default")
      (node (ref "J202") (pin "P$5") (pinfunction "5_P$5") (pintype "passive"))
      (node (ref "R201") (pin "P$2") (pinfunction "2_P$2") (pintype "passive"))
    )
    (net (code "209") (name "SERIAL2_RX") (class "Default")
      (node (ref "J202") (pin "P$3") (pinfunction "3_P$3") (pintype "passive"))
      (node (ref "R202") (pin "P$2") (pinfunction "2_P$2") (pintype "passive"))
      (node (ref "S2RX") (pin "P$1") (pinfunction "P$1_P$1") (pintype "passive"))
    )
    (net (code "210") (name "SERIAL2_TX") (class "Default")
      (node (ref "J202") (pin "P$2") (pinfunction "2_P$2") (pintype "passive"))
      (node (ref "R209") (pin "P$2") (pinfunction "2_P$2") (pintype "passive"))
      (node (ref "S2TX") (pin "P$1") (pinfunction "P$1_P$1") (pintype "passive"))
    )
    (net (code "211") (name "SERIAL3_RX") (class "Default")
      (node (ref "J203") (pin "P$3") (pinfunction "3_P$3") (pintype "passive"))
      (node (ref "R207") (pin "P$2") (pinfunction "2_P$2") (pintype "passive"))
      (node (ref "S3RX") (pin "P$1") (pinfunction "P$1_P$1") (pintype "passive"))
    )
    (net (code "212") (name "SERIAL3_TX") (class "Default")
      (node (ref "J203") (pin "P$2") (pinfunction "2_P$2") (pintype "passive"))
      (node (ref "R214") (pin "P$2") (pinfunction "2_P$2") (pintype "passive"))
      (node (ref "S3TX") (pin "P$1") (pinfunction "P$1_P$1") (pintype "passive"))
    )
    (net (code "213") (name "SERIAL4_RX") (class "Default")
      (node (ref "J204") (pin "P$3") (pinfunction "3_P$3") (pintype "passive"))
      (node (ref "R206") (pin "P$2") (pinfunction "2_P$2") (pintype "passive"))
      (node (ref "S4RX") (pin "P$1") (pinfunction "P$1_P$1") (pintype "passive"))
    )
    (net (code "214") (name "SERIAL4_TX") (class "Default")
      (node (ref "J204") (pin "P$2") (pinfunction "2_P$2") (pintype "passive"))
      (node (ref "R213") (pin "P$2") (pinfunction "2_P$2") (pintype "passive"))
      (node (ref "S4TX") (pin "P$1") (pinfunction "P$1_P$1") (pintype "passive"))
    )
    (net (code "215") (name "SERIAL5_RX") (class "Default")
      (node (ref "J204") (pin "P$5") (pinfunction "5_P$5") (pintype "passive"))
      (node (ref "R205") (pin "P$2") (pinfunction "2_P$2") (pintype "passive"))
      (node (ref "S5_RX") (pin "P$1") (pinfunction "P$1_P$1") (pintype "passive"))
    )
    (net (code "216") (name "SERIAL5_TX") (class "Default")
      (node (ref "J204") (pin "P$4") (pinfunction "4_P$4") (pintype "passive"))
      (node (ref "R212") (pin "P$2") (pinfunction "2_P$2") (pintype "passive"))
      (node (ref "S5_TX") (pin "P$1") (pinfunction "P$1_P$1") (pintype "passive"))
    )
    (net (code "217") (name "SERIAL_FMU_TO_IO") (class "Default")
      (node (ref "R804") (pin "P$2") (pinfunction "2_P$2") (pintype "passive"))
      (node (ref "U101") (pin "63") (pinfunction "PC6_63") (pintype "bidirectional"))
    )
    (net (code "218") (name "SERIAL_IO_TO_FMU") (class "Default")
      (node (ref "R803") (pin "P$2") (pinfunction "2_P$2") (pintype "passive"))
      (node (ref "U101") (pin "64") (pinfunction "PC7_64") (pintype "bidirectional"))
    )
    (net (code "219") (name "SPI_EXT_MISO") (class "Default")
      (node (ref "J403") (pin "P$3") (pinfunction "3_P$3") (pintype "passive"))
      (node (ref "U101") (pin "4") (pinfunction "PE5_4") (pintype "bidirectional"))
    )
    (net (code "220") (name "SPI_EXT_MOSI") (class "Default")
      (node (ref "J403") (pin "P$4") (pinfunction "4_P$4") (pintype "passive"))
      (node (ref "U101") (pin "5") (pinfunction "PE6_5") (pintype "bidirectional"))
    )
    (net (code "221") (name "SPI_EXT_SCK") (class "Default")
      (node (ref "J403") (pin "P$2") (pinfunction "2_P$2") (pintype "passive"))
      (node (ref "U101") (pin "1") (pinfunction "PE2_1") (pintype "bidirectional"))
    )
    (net (code "222") (name "SPI_INT_MISO") (class "Default")
      (node (ref "U$1") (pin "9") (pinfunction "S_9") (pintype "passive"))
      (node (ref "U$501") (pin "7") (pinfunction "SDO/SA0_7") (pintype "bidirectional"))
      (node (ref "U101") (pin "31") (pinfunction "PA6_31") (pintype "bidirectional"))
      (node (ref "U501") (pin "4") (pinfunction "SDO/SA0_4") (pintype "bidirectional"))
      (node (ref "U502") (pin "4") (pinfunction "SDO/SA0_4") (pintype "bidirectional"))
      (node (ref "U503") (pin "6") (pinfunction "SDO_6") (pintype "bidirectional"))
    )
    (net (code "223") (name "SPI_INT_MOSI") (class "Default")
      (node (ref "U$1") (pin "8") (pinfunction "S_8") (pintype "passive"))
      (node (ref "U$501") (pin "6") (pinfunction "SDA/SDI/SDO_6") (pintype "bidirectional"))
      (node (ref "U101") (pin "32") (pinfunction "PA7_32") (pintype "bidirectional"))
      (node (ref "U501") (pin "3") (pinfunction "SDA/SDI/SDO_3") (pintype "bidirectional"))
      (node (ref "U502") (pin "3") (pinfunction "SDA/SDI/SDO_3") (pintype "bidirectional"))
      (node (ref "U503") (pin "7") (pinfunction "SDI/SDA_7") (pintype "bidirectional"))
    )
    (net (code "224") (name "SPI_INT_SCK") (class "Default")
      (node (ref "U$1") (pin "10") (pinfunction "S_10") (pintype "passive"))
      (node (ref "U$501") (pin "4") (pinfunction "SCL/SPC_4") (pintype "bidirectional"))
      (node (ref "U101") (pin "30") (pinfunction "PA5_30") (pintype "bidirectional"))
      (node (ref "U501") (pin "2") (pinfunction "SCL/SPC_2") (pintype "input"))
      (node (ref "U502") (pin "2") (pinfunction "SCL/SPC_2") (pintype "bidirectional"))
      (node (ref "U503") (pin "8") (pinfunction "SCLK_8") (pintype "bidirectional"))
    )
    (net (code "225") (name "VBAT") (class "Default")
      (node (ref "B601") (pin "1") (pinfunction "POS_1") (pintype "bidirectional"))
      (node (ref "R608") (pin "P$1") (pinfunction "1_P$1") (pintype "passive"))
      (node (ref "U101") (pin "6") (pinfunction "VBAT_6") (pintype "power_in"))
      (node (ref "U801") (pin "1") (pinfunction "VBAT_1") (pintype "power_in"))
    )
    (net (code "226") (name "VBUS") (class "Default")
      (node (ref "J301") (pin "VBUS") (pinfunction "1_VBUS") (pintype "power_in"))
      (node (ref "J302") (pin "P$1") (pinfunction "1_P$1") (pintype "passive"))
      (node (ref "R6") (pin "P$1") (pinfunction "1_P$1") (pintype "passive"))
      (node (ref "U$2") (pin "P$19") (pinfunction "V3_P$19") (pintype "bidirectional"))
      (node (ref "U$301") (pin "5") (pinfunction "VBUS_5") (pintype "bidirectional"))
      (node (ref "U$5") (pin "P$7") (pinfunction "D_P$7") (pintype "passive"))
      (node (ref "U$5") (pin "P$8") (pinfunction "D_P$8") (pintype "passive"))
      (node (ref "U101") (pin "68") (pinfunction "PA9_68") (pintype "bidirectional"))
    )
    (net (code "227") (name "VDD_3V3_SENSORS") (class "Default")
      (node (ref "C501") (pin "P$1") (pinfunction "1_P$1") (pintype "passive"))
      (node (ref "C502") (pin "P$1") (pinfunction "1_P$1") (pintype "passive"))
      (node (ref "C503") (pin "P$1") (pinfunction "1_P$1") (pintype "passive"))
      (node (ref "C506") (pin "P$1") (pinfunction "1_P$1") (pintype "passive"))
      (node (ref "C507") (pin "P$1") (pinfunction "1_P$1") (pintype "passive"))
      (node (ref "C508") (pin "P$1") (pinfunction "1_P$1") (pintype "passive"))
      (node (ref "C605") (pin "P$1") (pinfunction "1_P$1") (pintype "passive"))
      (node (ref "U$1") (pin "1") (pinfunction "S_1") (pintype "passive"))
      (node (ref "U$501") (pin "1") (pinfunction "VDD_IO_1") (pintype "bidirectional"))
      (node (ref "U$501") (pin "14") (pinfunction "VDD_14") (pintype "bidirectional"))
      (node (ref "U$605") (pin "8") (pinfunction "VOUT1_8") (pintype "bidirectional"))
      (node (ref "U501") (pin "1") (pinfunction "VDD_IO_1") (pintype "bidirectional"))
      (node (ref "U501") (pin "15") (pinfunction "RES_P15_VDD_15") (pintype "bidirectional"))
      (node (ref "U501") (pin "16") (pinfunction "VDD_16") (pintype "bidirectional"))
      (node (ref "U502") (pin "1") (pinfunction "VDD_IO_1") (pintype "bidirectional"))
      (node (ref "U502") (pin "15") (pinfunction "VDD_15") (pintype "bidirectional"))
      (node (ref "U502") (pin "16") (pinfunction "VDD_16") (pintype "bidirectional"))
      (node (ref "U503") (pin "1") (pinfunction "VDD_1") (pintype "bidirectional"))
      (node (ref "VDDA_3V1101") (pin "P$1") (pinfunction "P$1_P$1") (pintype "passive"))
    )
    (net (code "228") (name "VDD_3V3_SENSORS_EN") (class "Default")
      (node (ref "R603") (pin "P$1") (pinfunction "1_P$1") (pintype "passive"))
      (node (ref "U$605") (pin "5") (pinfunction "EN1_5") (pintype "bidirectional"))
      (node (ref "U101") (pin "2") (pinfunction "PE3_2") (pintype "bidirectional"))
    )
    (net (code "229") (name "VDD_3V3_SPEKTRUM") (class "Default")
      (node (ref "C1003") (pin "P$1") (pinfunction "1_P$1") (pintype "passive"))
      (node (ref "J801") (pin "P$1") (pinfunction "P$1_P$1") (pintype "bidirectional"))
      (node (ref "U$1002") (pin "8") (pinfunction "VOUT1_8") (pintype "bidirectional"))
      (node (ref "U$801") (pin "C") (pinfunction "C_C") (pintype "passive"))
    )
    (net (code "230") (name "VDD_3V3_SPEKTRUM_EN") (class "Default")
      (node (ref "R1002") (pin "P$2") (pinfunction "2_P$2") (pintype "passive"))
      (node (ref "U$1002") (pin "5") (pinfunction "EN1_5") (pintype "bidirectional"))
      (node (ref "U801") (pin "2") (pinfunction "PC13_2") (pintype "bidirectional"))
    )
    (net (code "231") (name "VDD_5V_BRICK") (class "Default")
      (node (ref "J601") (pin "P$1") (pinfunction "1_P$1") (pintype "passive"))
      (node (ref "J601") (pin "P$2") (pinfunction "2_P$2") (pintype "passive"))
      (node (ref "R1") (pin "P$1") (pinfunction "1_P$1") (pintype "passive"))
      (node (ref "U$2") (pin "P$21") (pinfunction "V1_P$21") (pintype "bidirectional"))
      (node (ref "U$3") (pin "P$7") (pinfunction "D_P$7") (pintype "passive"))
      (node (ref "U$3") (pin "P$8") (pinfunction "D_P$8") (pintype "passive"))
      (node (ref "VDD_5V_BRICK") (pin "P$1") (pinfunction "P$1_P$1") (pintype "passive"))
    )
    (net (code "232") (name "VDD_5V_HIPOWER") (class "Default")
      (node (ref "L201") (pin "P$1") (pinfunction "P$1_P$1") (pintype "bidirectional"))
      (node (ref "U$602") (pin "8") (pinfunction "OUT_8") (pintype "bidirectional"))
    )
    (net (code "233") (name "VDD_5V_IN") (class "Default")
      (node (ref "C702") (pin "P$1") (pinfunction "1_P$1") (pintype "passive"))
      (node (ref "F2") (pin "1") (pinfunction "1_1") (pintype "bidirectional"))
      (node (ref "L603") (pin "P$1") (pinfunction "P$1_P$1") (pintype "bidirectional"))
      (node (ref "L701") (pin "P$1") (pinfunction "1_P$1") (pintype "passive"))
      (node (ref "LED701") (pin "A") (pinfunction "A_A") (pintype "passive"))
      (node (ref "LED704") (pin "A") (pinfunction "A_A") (pintype "passive"))
      (node (ref "R609") (pin "P$2") (pinfunction "2_P$2") (pintype "passive"))
      (node (ref "U$2") (pin "P$12") (pinfunction "VOUT_P$12") (pintype "bidirectional"))
      (node (ref "U$3") (pin "P$5") (pinfunction "D_P$5") (pintype "passive"))
      (node (ref "U$3") (pin "P$6") (pinfunction "D_P$6") (pintype "passive"))
      (node (ref "U$4") (pin "P$5") (pinfunction "D_P$5") (pintype "passive"))
      (node (ref "U$4") (pin "P$6") (pinfunction "D_P$6") (pintype "passive"))
      (node (ref "U$5") (pin "P$5") (pinfunction "D_P$5") (pintype "passive"))
      (node (ref "U$5") (pin "P$6") (pinfunction "D_P$6") (pintype "passive"))
      (node (ref "U$602") (pin "1") (pinfunction "IN_1") (pintype "bidirectional"))
      (node (ref "U$604") (pin "1") (pinfunction "IN_1") (pintype "bidirectional"))
      (node (ref "U702") (pin "3") (pinfunction "VIN_3") (pintype "power_in"))
      (node (ref "U703") (pin "A1") (pinfunction "A_A1") (pintype "passive"))
      (node (ref "U703") (pin "A2") (pinfunction "A_A2") (pintype "passive"))
      (node (ref "U703") (pin "A3") (pinfunction "A_A3") (pintype "passive"))
    )
    (net (code "234") (name "VDD_5V_PERIPH") (class "Default")
      (node (ref "L202") (pin "P$1") (pinfunction "P$1_P$1") (pintype "bidirectional"))
      (node (ref "L203") (pin "P$1") (pinfunction "P$1_P$1") (pintype "bidirectional"))
      (node (ref "L401") (pin "P$1") (pinfunction "P$1_P$1") (pintype "bidirectional"))
      (node (ref "L402") (pin "P$1") (pinfunction "P$1_P$1") (pintype "bidirectional"))
      (node (ref "L403") (pin "P$1") (pinfunction "P$1_P$1") (pintype "bidirectional"))
      (node (ref "L404") (pin "P$1") (pinfunction "P$1_P$1") (pintype "bidirectional"))
      (node (ref "U$604") (pin "8") (pinfunction "OUT_8") (pintype "bidirectional"))
    )
    (net (code "235") (name "VDD_5V_SENS") (class "Default")
      (node (ref "R609") (pin "P$1") (pinfunction "1_P$1") (pintype "passive"))
      (node (ref "R610") (pin "P$1") (pinfunction "1_P$1") (pintype "passive"))
      (node (ref "U101") (pin "29") (pinfunction "PA4_29") (pintype "bidirectional"))
    )
    (net (code "236") (name "VDD_SERVO") (class "Default")
      (node (ref "D1") (pin "ANODE") (pinfunction "A_ANODE") (pintype "passive"))
      (node (ref "J901") (pin "11") (pinfunction "S_11") (pintype "passive"))
      (node (ref "J901") (pin "14") (pinfunction "S_14") (pintype "passive"))
      (node (ref "J901") (pin "17") (pinfunction "S_17") (pintype "passive"))
      (node (ref "J901") (pin "20") (pinfunction "S_20") (pintype "passive"))
      (node (ref "J901") (pin "23") (pinfunction "S_23") (pintype "passive"))
      (node (ref "J901") (pin "26") (pinfunction "S_26") (pintype "passive"))
      (node (ref "J901") (pin "29") (pinfunction "S_29") (pintype "passive"))
      (node (ref "J901") (pin "32") (pinfunction "S_32") (pintype "passive"))
      (node (ref "J901") (pin "35") (pinfunction "S_35") (pintype "passive"))
      (node (ref "J901") (pin "38") (pinfunction "S_38") (pintype "passive"))
      (node (ref "J901") (pin "41") (pinfunction "S_41") (pintype "passive"))
      (node (ref "J901") (pin "44") (pinfunction "S_44") (pintype "passive"))
      (node (ref "J901") (pin "47") (pinfunction "S_47") (pintype "passive"))
      (node (ref "J901") (pin "5") (pinfunction "S_5") (pintype "passive"))
      (node (ref "J901") (pin "8") (pinfunction "S_8") (pintype "passive"))
      (node (ref "R9") (pin "P$1") (pinfunction "1_P$1") (pintype "passive"))
      (node (ref "R922") (pin "P$2") (pinfunction "2_P$2") (pintype "passive"))
      (node (ref "U$2") (pin "P$20") (pinfunction "V2_P$20") (pintype "bidirectional"))
      (node (ref "U$4") (pin "P$7") (pinfunction "D_P$7") (pintype "passive"))
      (node (ref "U$4") (pin "P$8") (pinfunction "D_P$8") (pintype "passive"))
    )
    (net (code "237") (name "VDD_SERVO_IN") (class "Default")
      (node (ref "L901") (pin "P$2") (pinfunction "P$2_P$2") (pintype "bidirectional"))
      (node (ref "U$1001") (pin "1") (pinfunction "IN_1") (pintype "bidirectional"))
    )
    (net (code "238") (name "VDD_SERVO_SENS") (class "Default")
      (node (ref "R918") (pin "P$1") (pinfunction "1_P$1") (pintype "passive"))
      (node (ref "R919") (pin "P$2") (pinfunction "2_P$2") (pintype "passive"))
      (node (ref "U801") (pin "14") (pinfunction "PA4_14") (pintype "bidirectional"))
    )
    (net (code "239") (name "unconnected-(J301-4-PadID)") (class "Default")
      (node (ref "J301") (pin "ID") (pinfunction "4_ID") (pintype "passive"))
    )
    (net (code "240") (name "unconnected-(JX301A-S-Pad10)") (class "Default")
      (node (ref "JX301") (pin "10") (pinfunction "S_10") (pintype "passive"))
    )
    (net (code "241") (name "unconnected-(JX301F-S-Pad8)") (class "Default")
      (node (ref "JX301") (pin "8") (pinfunction "S_8") (pintype "passive"))
    )
    (net (code "242") (name "unconnected-(JX802A-S-Pad10)") (class "Default")
      (node (ref "JX802") (pin "10") (pinfunction "S_10") (pintype "passive"))
    )
    (net (code "243") (name "unconnected-(JX802F-S-Pad8)") (class "Default")
      (node (ref "JX802") (pin "8") (pinfunction "S_8") (pintype "passive"))
    )
    (net (code "244") (name "unconnected-(U$2-CAS-PadP$11)") (class "Default")
      (node (ref "U$2") (pin "P$11") (pinfunction "CAS_P$11") (pintype "bidirectional"))
    )
    (net (code "245") (name "unconnected-(U$2-EN-PadP$22)") (class "Default")
      (node (ref "U$2") (pin "P$22") (pinfunction "EN_P$22") (pintype "bidirectional"))
    )
    (net (code "246") (name "unconnected-(U$2-~{SHDN}-PadP$23)") (class "Default")
      (node (ref "U$2") (pin "P$23") (pinfunction "~{SHDN}_P$23") (pintype "bidirectional"))
    )
    (net (code "247") (name "unconnected-(U101I-PC0-Pad15)") (class "Default")
      (node (ref "U101") (pin "15") (pinfunction "PC0_15") (pintype "bidirectional"))
    )
    (net (code "248") (name "unconnected-(U101I-PC1-Pad16)") (class "Default")
      (node (ref "U101") (pin "16") (pinfunction "PC1_16") (pintype "bidirectional"))
    )
    (net (code "249") (name "unconnected-(U101I-PC2-Pad17)") (class "Default")
      (node (ref "U101") (pin "17") (pinfunction "PC2_17") (pintype "bidirectional"))
    )
    (net (code "250") (name "unconnected-(U101J-PD15-Pad62)") (class "Default")
      (node (ref "U101") (pin "62") (pinfunction "PD15_62") (pintype "bidirectional"))
    )
    (net (code "251") (name "unconnected-(U202-A1-Pad1)") (class "Default")
      (node (ref "U202") (pin "1") (pinfunction "A1_1") (pintype "bidirectional"))
    )
    (net (code "252") (name "unconnected-(U202-A2-Pad3)") (class "Default")
      (node (ref "U202") (pin "3") (pinfunction "A2_3") (pintype "bidirectional"))
    )
    (net (code "253") (name "unconnected-(U202-B1-Pad20)") (class "Default")
      (node (ref "U202") (pin "20") (pinfunction "B1_20") (pintype "bidirectional"))
    )
    (net (code "254") (name "unconnected-(U202-B2-Pad18)") (class "Default")
      (node (ref "U202") (pin "18") (pinfunction "B2_18") (pintype "bidirectional"))
    )
    (net (code "255") (name "unconnected-(U501-INT1-Pad7)") (class "Default")
      (node (ref "U501") (pin "7") (pinfunction "INT1_7") (pintype "output"))
    )
    (net (code "256") (name "unconnected-(U502-DEN-Pad8)") (class "Default")
      (node (ref "U502") (pin "8") (pinfunction "DEN_8") (pintype "bidirectional"))
    )
    (net (code "257") (name "unconnected-(U502-INT1-Pad7)") (class "Default")
      (node (ref "U502") (pin "7") (pinfunction "INT1_7") (pintype "bidirectional"))
    )
    (net (code "258") (name "unconnected-(U503-CSB1-Pad4)") (class "Default")
      (node (ref "U503") (pin "4") (pinfunction "CSB1_4") (pintype "bidirectional"))
    )
    (net (code "259") (name "unconnected-(U801B-PA11-Pad32)") (class "Default")
      (node (ref "U801") (pin "32") (pinfunction "PA11_32") (pintype "bidirectional"))
    )
    (net (code "260") (name "unconnected-(U801D-PB12-Pad25)") (class "Default")
      (node (ref "U801") (pin "25") (pinfunction "PB12_25") (pintype "bidirectional"))
    )
    (net (code "261") (name "unconnected-(U801E-PB6-Pad42)") (class "Default")
      (node (ref "U801") (pin "42") (pinfunction "PB6_42") (pintype "bidirectional"))
    )
    (net (code "262") (name "unconnected-(U801E-PB7-Pad43)") (class "Default")
      (node (ref "U801") (pin "43") (pinfunction "PB7_43") (pintype "bidirectional"))
    )
    (net (code "263") (name "unconnected-(U801F-PC14-Pad3)") (class "Default")
      (node (ref "U801") (pin "3") (pinfunction "PC14_3") (pintype "bidirectional"))
    )
    (net (code "264") (name "unconnected-(U801F-PC15-Pad4)") (class "Default")
      (node (ref "U801") (pin "4") (pinfunction "PC15_4") (pintype "bidirectional"))
    )
    (net (code "265") (name "unconnected-(U901-A7-Pad8)") (class "Default")
      (node (ref "U901") (pin "8") (pinfunction "A7_8") (pintype "bidirectional"))
    )
    (net (code "266") (name "unconnected-(U901-A8-Pad9)") (class "Default")
      (node (ref "U901") (pin "9") (pinfunction "A8_9") (pintype "bidirectional"))
    )
    (net (code "267") (name "unconnected-(U901-B7-Pad13)") (class "Default")
      (node (ref "U901") (pin "13") (pinfunction "B7_13") (pintype "bidirectional"))
    )
    (net (code "268") (name "unconnected-(U901-B8-Pad12)") (class "Default")
      (node (ref "U901") (pin "12") (pinfunction "B8_12") (pintype "bidirectional"))
    )
    (net (code "269") (name "~{ACCEL_MAG_CS}") (class "Default")
      (node (ref "U$1") (pin "6") (pinfunction "S_6") (pintype "passive"))
      (node (ref "U$501") (pin "8") (pinfunction "CS_8") (pintype "bidirectional"))
      (node (ref "U101") (pin "9") (pinfunction "PC15_9") (pintype "bidirectional"))
    )
    (net (code "270") (name "~{BARO_CS}") (class "Default")
      (node (ref "U101") (pin "88") (pinfunction "PD7_88") (pintype "bidirectional"))
      (node (ref "U503") (pin "5") (pinfunction "CSB2_5") (pintype "bidirectional"))
    )
    (net (code "271") (name "~{FMU-LED_AMBER}") (class "Default")
      (node (ref "R707") (pin "P$1") (pinfunction "1_P$1") (pintype "passive"))
      (node (ref "U101") (pin "43") (pinfunction "PE12_43") (pintype "bidirectional"))
    )
    (net (code "272") (name "~{FRAM_CS}") (class "Default")
      (node (ref "U101") (pin "57") (pinfunction "PD10_57") (pintype "bidirectional"))
      (node (ref "U102") (pin "1") (pinfunction "~{S}_1") (pintype "bidirectional"))
    )
    (net (code "273") (name "~{GYRO_CS}") (class "Default")
      (node (ref "U$1") (pin "7") (pinfunction "S_7") (pintype "passive"))
      (node (ref "U101") (pin "7") (pinfunction "PC13_7") (pintype "bidirectional"))
      (node (ref "U501") (pin "5") (pinfunction "CS_5") (pintype "input"))
      (node (ref "U502") (pin "5") (pinfunction "CS_5") (pintype "bidirectional"))
    )
    (net (code "274") (name "~{IO-LED_AMBER}") (class "Default")
      (node (ref "R709") (pin "P$1") (pinfunction "1_P$1") (pintype "passive"))
      (node (ref "U801") (pin "28") (pinfunction "PB15_28") (pintype "bidirectional"))
    )
    (net (code "275") (name "~{IO-LED_BLUE}") (class "Default")
      (node (ref "R712") (pin "P$1") (pinfunction "1_P$1") (pintype "passive"))
      (node (ref "U801") (pin "27") (pinfunction "PB14_27") (pintype "bidirectional"))
    )
    (net (code "276") (name "~{IO-LED_SAFETY}") (class "Default")
      (node (ref "R710") (pin "P$2") (pinfunction "2_P$2") (pintype "passive"))
      (node (ref "U801") (pin "26") (pinfunction "PB13_26") (pintype "bidirectional"))
    )
    (net (code "277") (name "~{SBUS_OUTPUT_EN}") (class "Default")
      (node (ref "U801") (pin "40") (pinfunction "PB4_40") (pintype "bidirectional"))
      (node (ref "U903") (pin "7") (pinfunction "~{2OE}_7") (pintype "input"))
    )
    (net (code "278") (name "~{SPI_EXT_NSS}") (class "Default")
      (node (ref "J403") (pin "P$5") (pinfunction "5_P$5") (pintype "passive"))
      (node (ref "U101") (pin "3") (pinfunction "PE4_3") (pintype "bidirectional"))
    )
    (net (code "279") (name "~{VBUS_VALID}") (class "Default")
      (node (ref "U$2") (pin "P$9") (pinfunction "~{VALID3}_P$9") (pintype "bidirectional"))
    )
    (net (code "280") (name "~{VDD_5V_HIPOWER_OC}") (class "Default")
      (node (ref "U$602") (pin "4") (pinfunction "~{FAULT}_4") (pintype "bidirectional"))
      (node (ref "U101") (pin "41") (pinfunction "PE10_41") (pintype "bidirectional"))
    )
    (net (code "281") (name "~{VDD_5V_PERIPH_EN}") (class "Default")
      (node (ref "R607") (pin "P$1") (pinfunction "1_P$1") (pintype "passive"))
      (node (ref "U$602") (pin "5") (pinfunction "~{CE}_5") (pintype "bidirectional"))
      (node (ref "U$604") (pin "5") (pinfunction "~{CE}_5") (pintype "bidirectional"))
      (node (ref "U101") (pin "67") (pinfunction "PA8_67") (pintype "bidirectional"))
    )
    (net (code "282") (name "~{VDD_5V_PERIPH_OC}") (class "Default")
      (node (ref "U$604") (pin "4") (pinfunction "~{FAULT}_4") (pintype "bidirectional"))
      (node (ref "U101") (pin "46") (pinfunction "PE15_46") (pintype "bidirectional"))
    )
    (net (code "283") (name "~{VDD_BRICK_VALID}") (class "Default")
      (node (ref "U$2") (pin "P$7") (pinfunction "~{VALID1}_P$7") (pintype "bidirectional"))
      (node (ref "U101") (pin "91") (pinfunction "PB5_91") (pintype "bidirectional"))
    )
    (net (code "284") (name "~{VDD_SERVO_VALID}") (class "Default")
      (node (ref "U$2") (pin "P$8") (pinfunction "~{VALID2}_P$8") (pintype "bidirectional"))
      (node (ref "U101") (pin "93") (pinfunction "PB7_93") (pintype "bidirectional"))
    )
  )
)
